# Led_Driver_180_LEDs.net
KiCad netlist of a schematic drawn in EAGLE
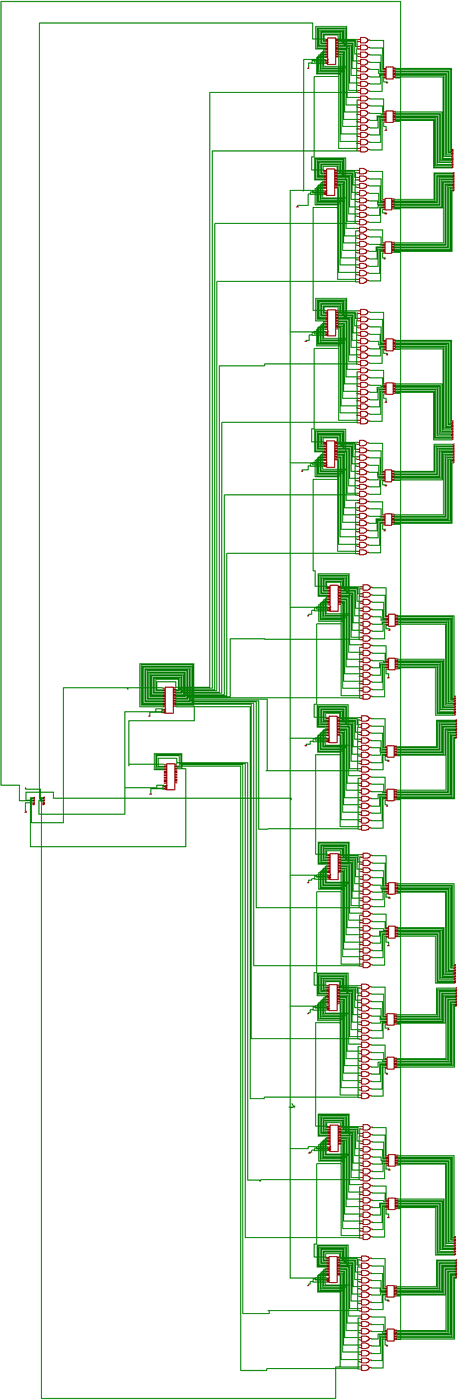
[diagram p0: schematic, sheet 1, overview]
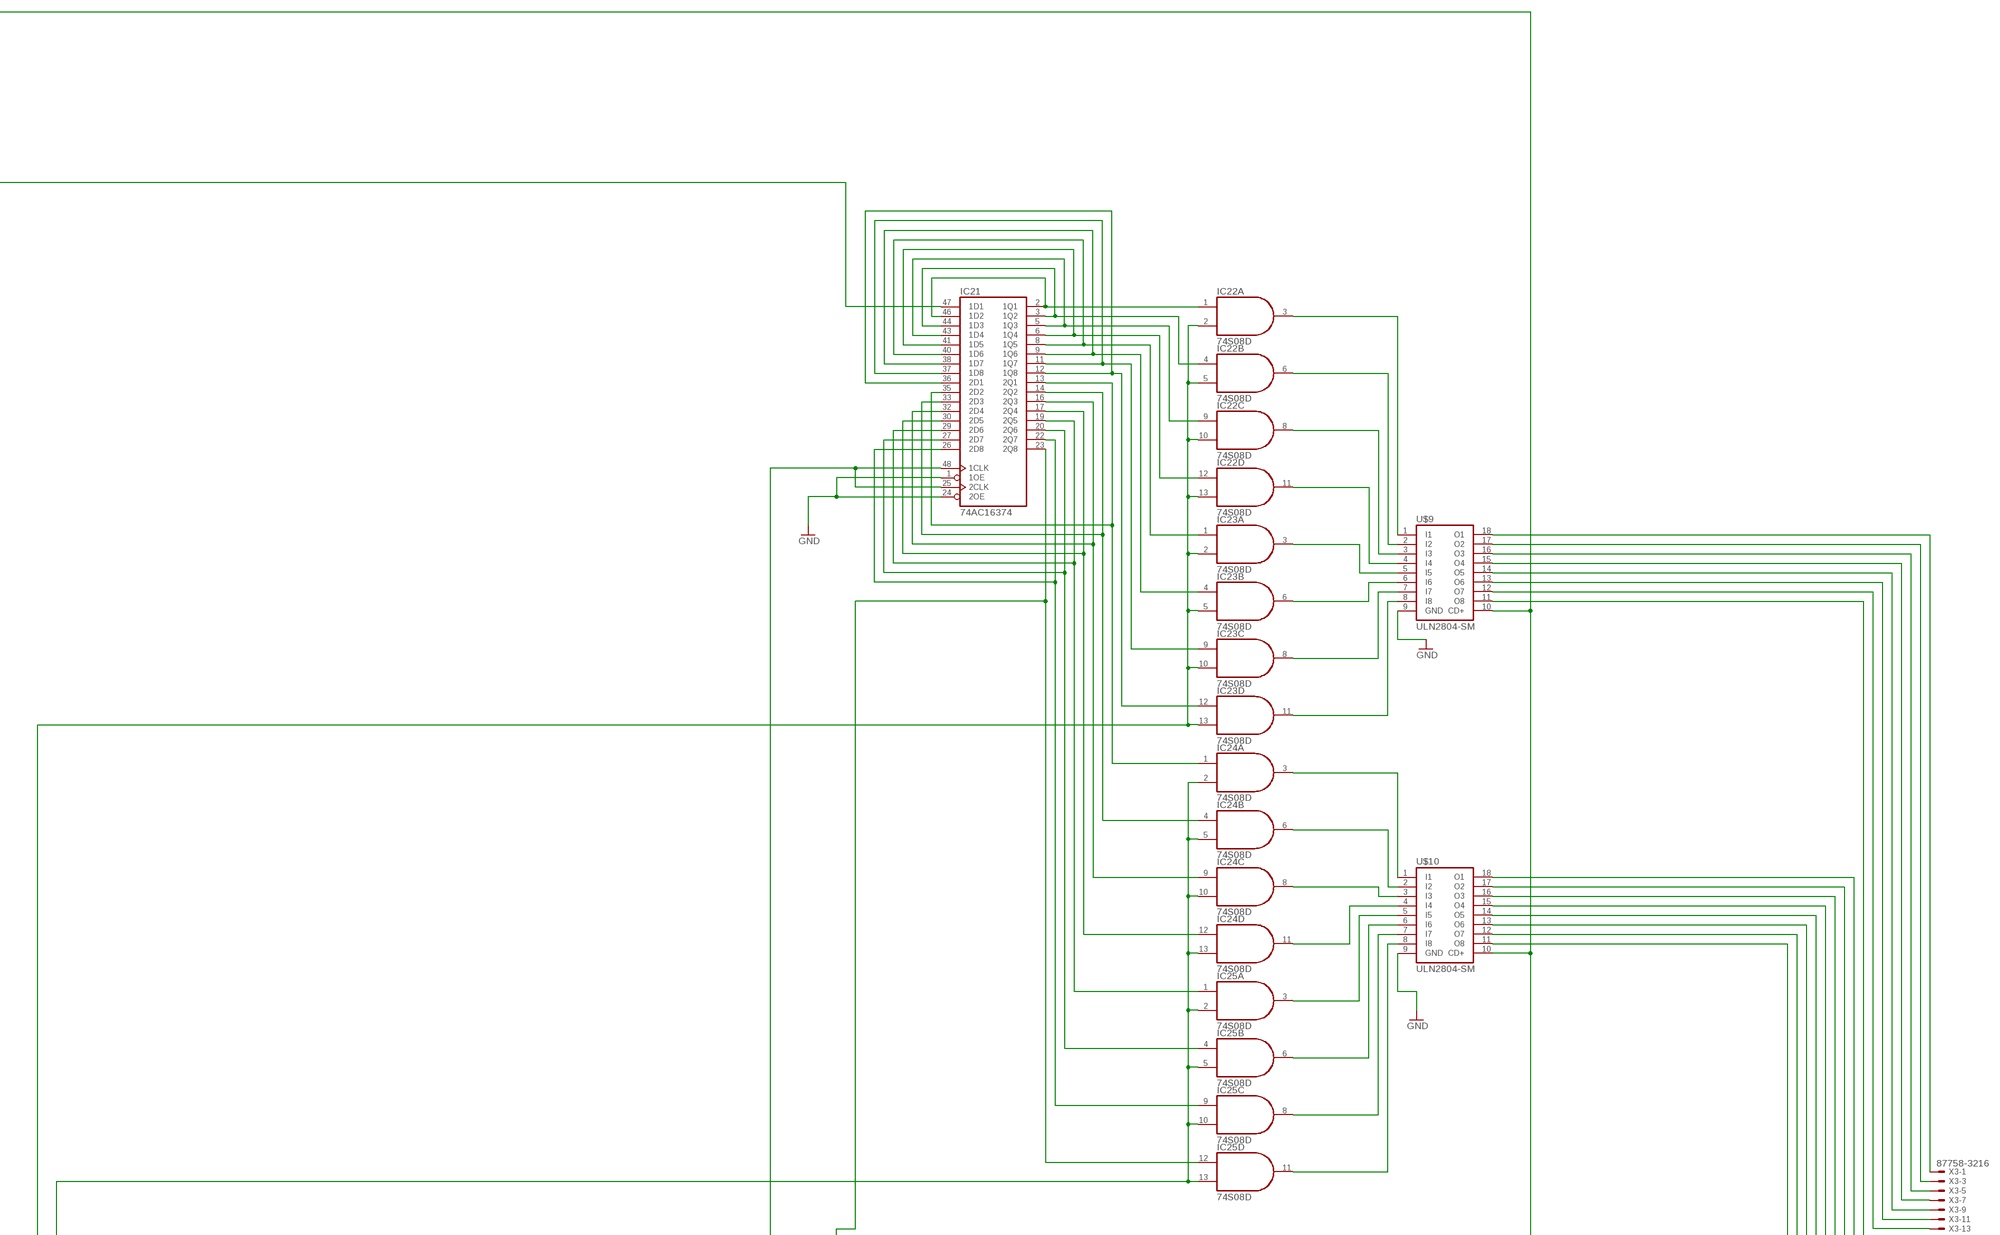
[diagram p1: schematic, sheet 1, part 1 of 9]
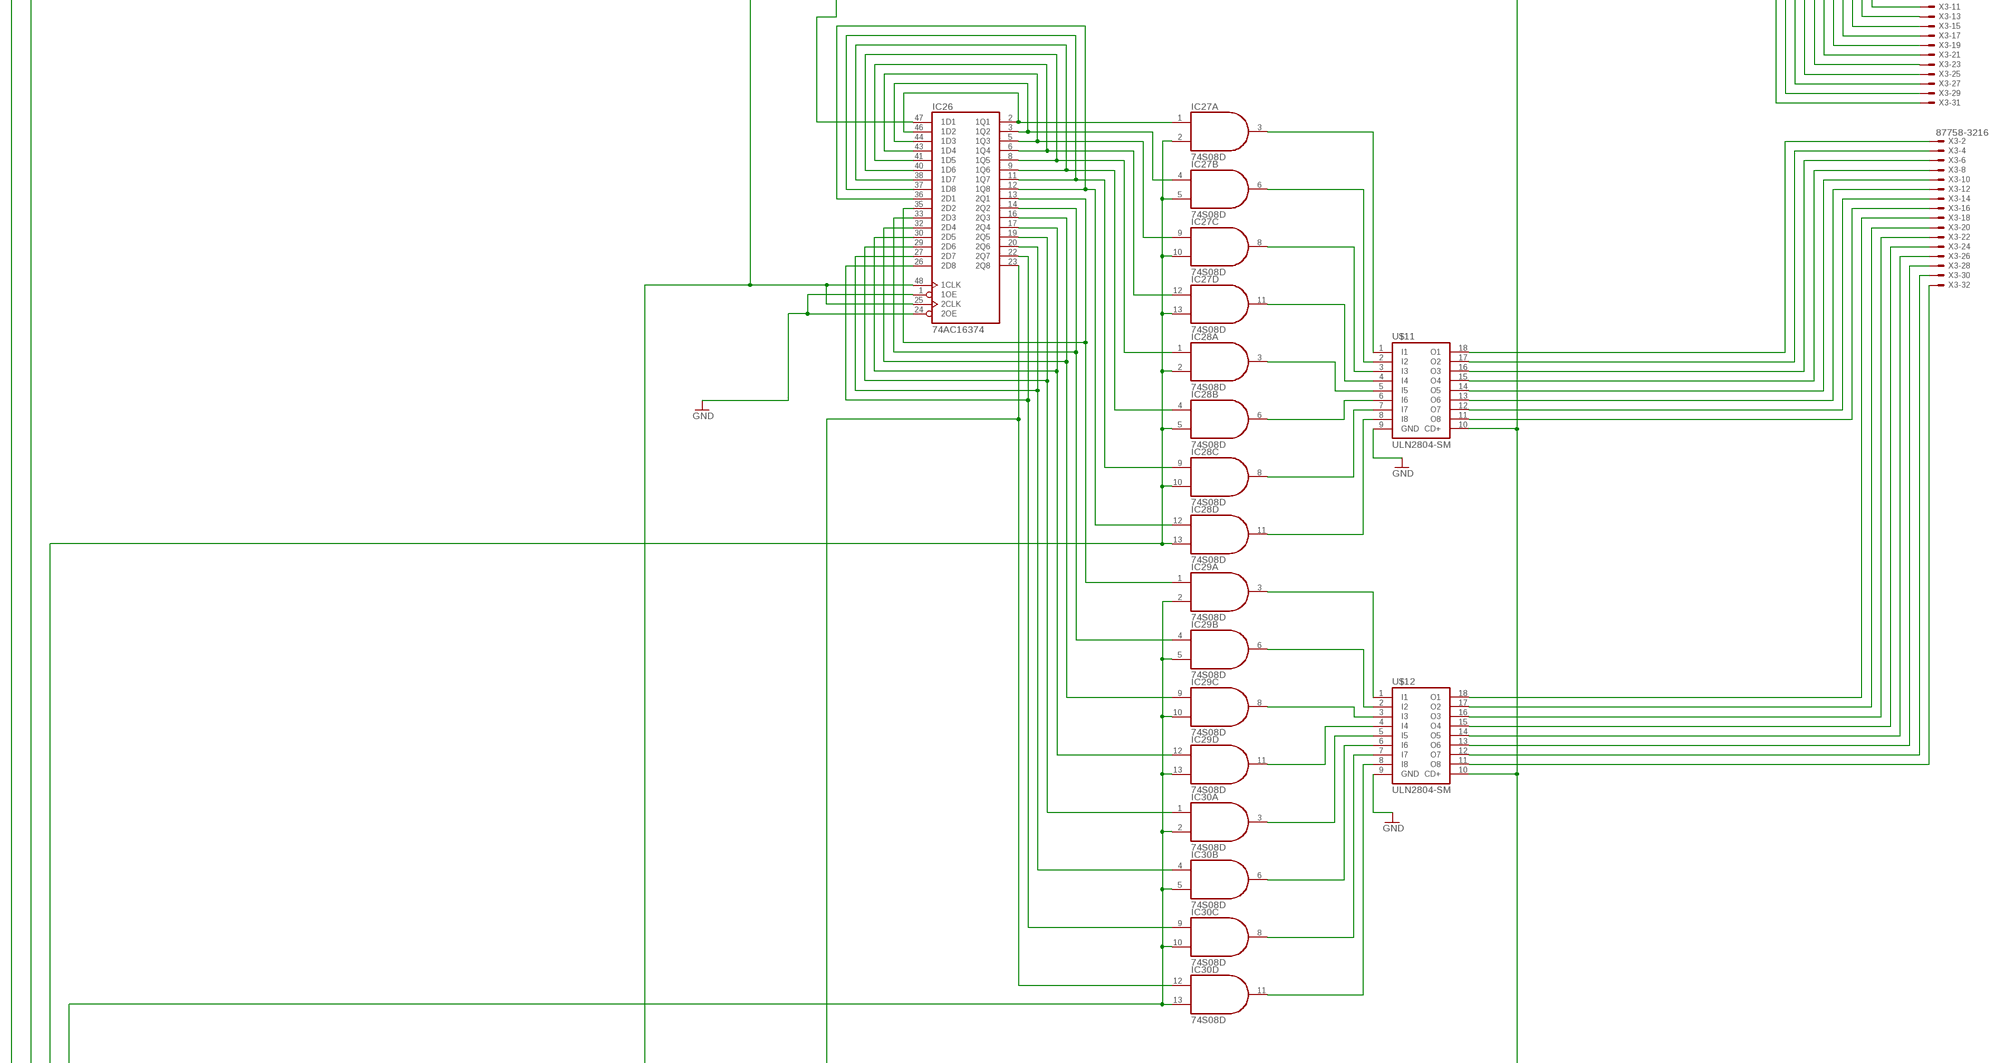
[diagram p2: schematic, sheet 1, part 2 of 9]
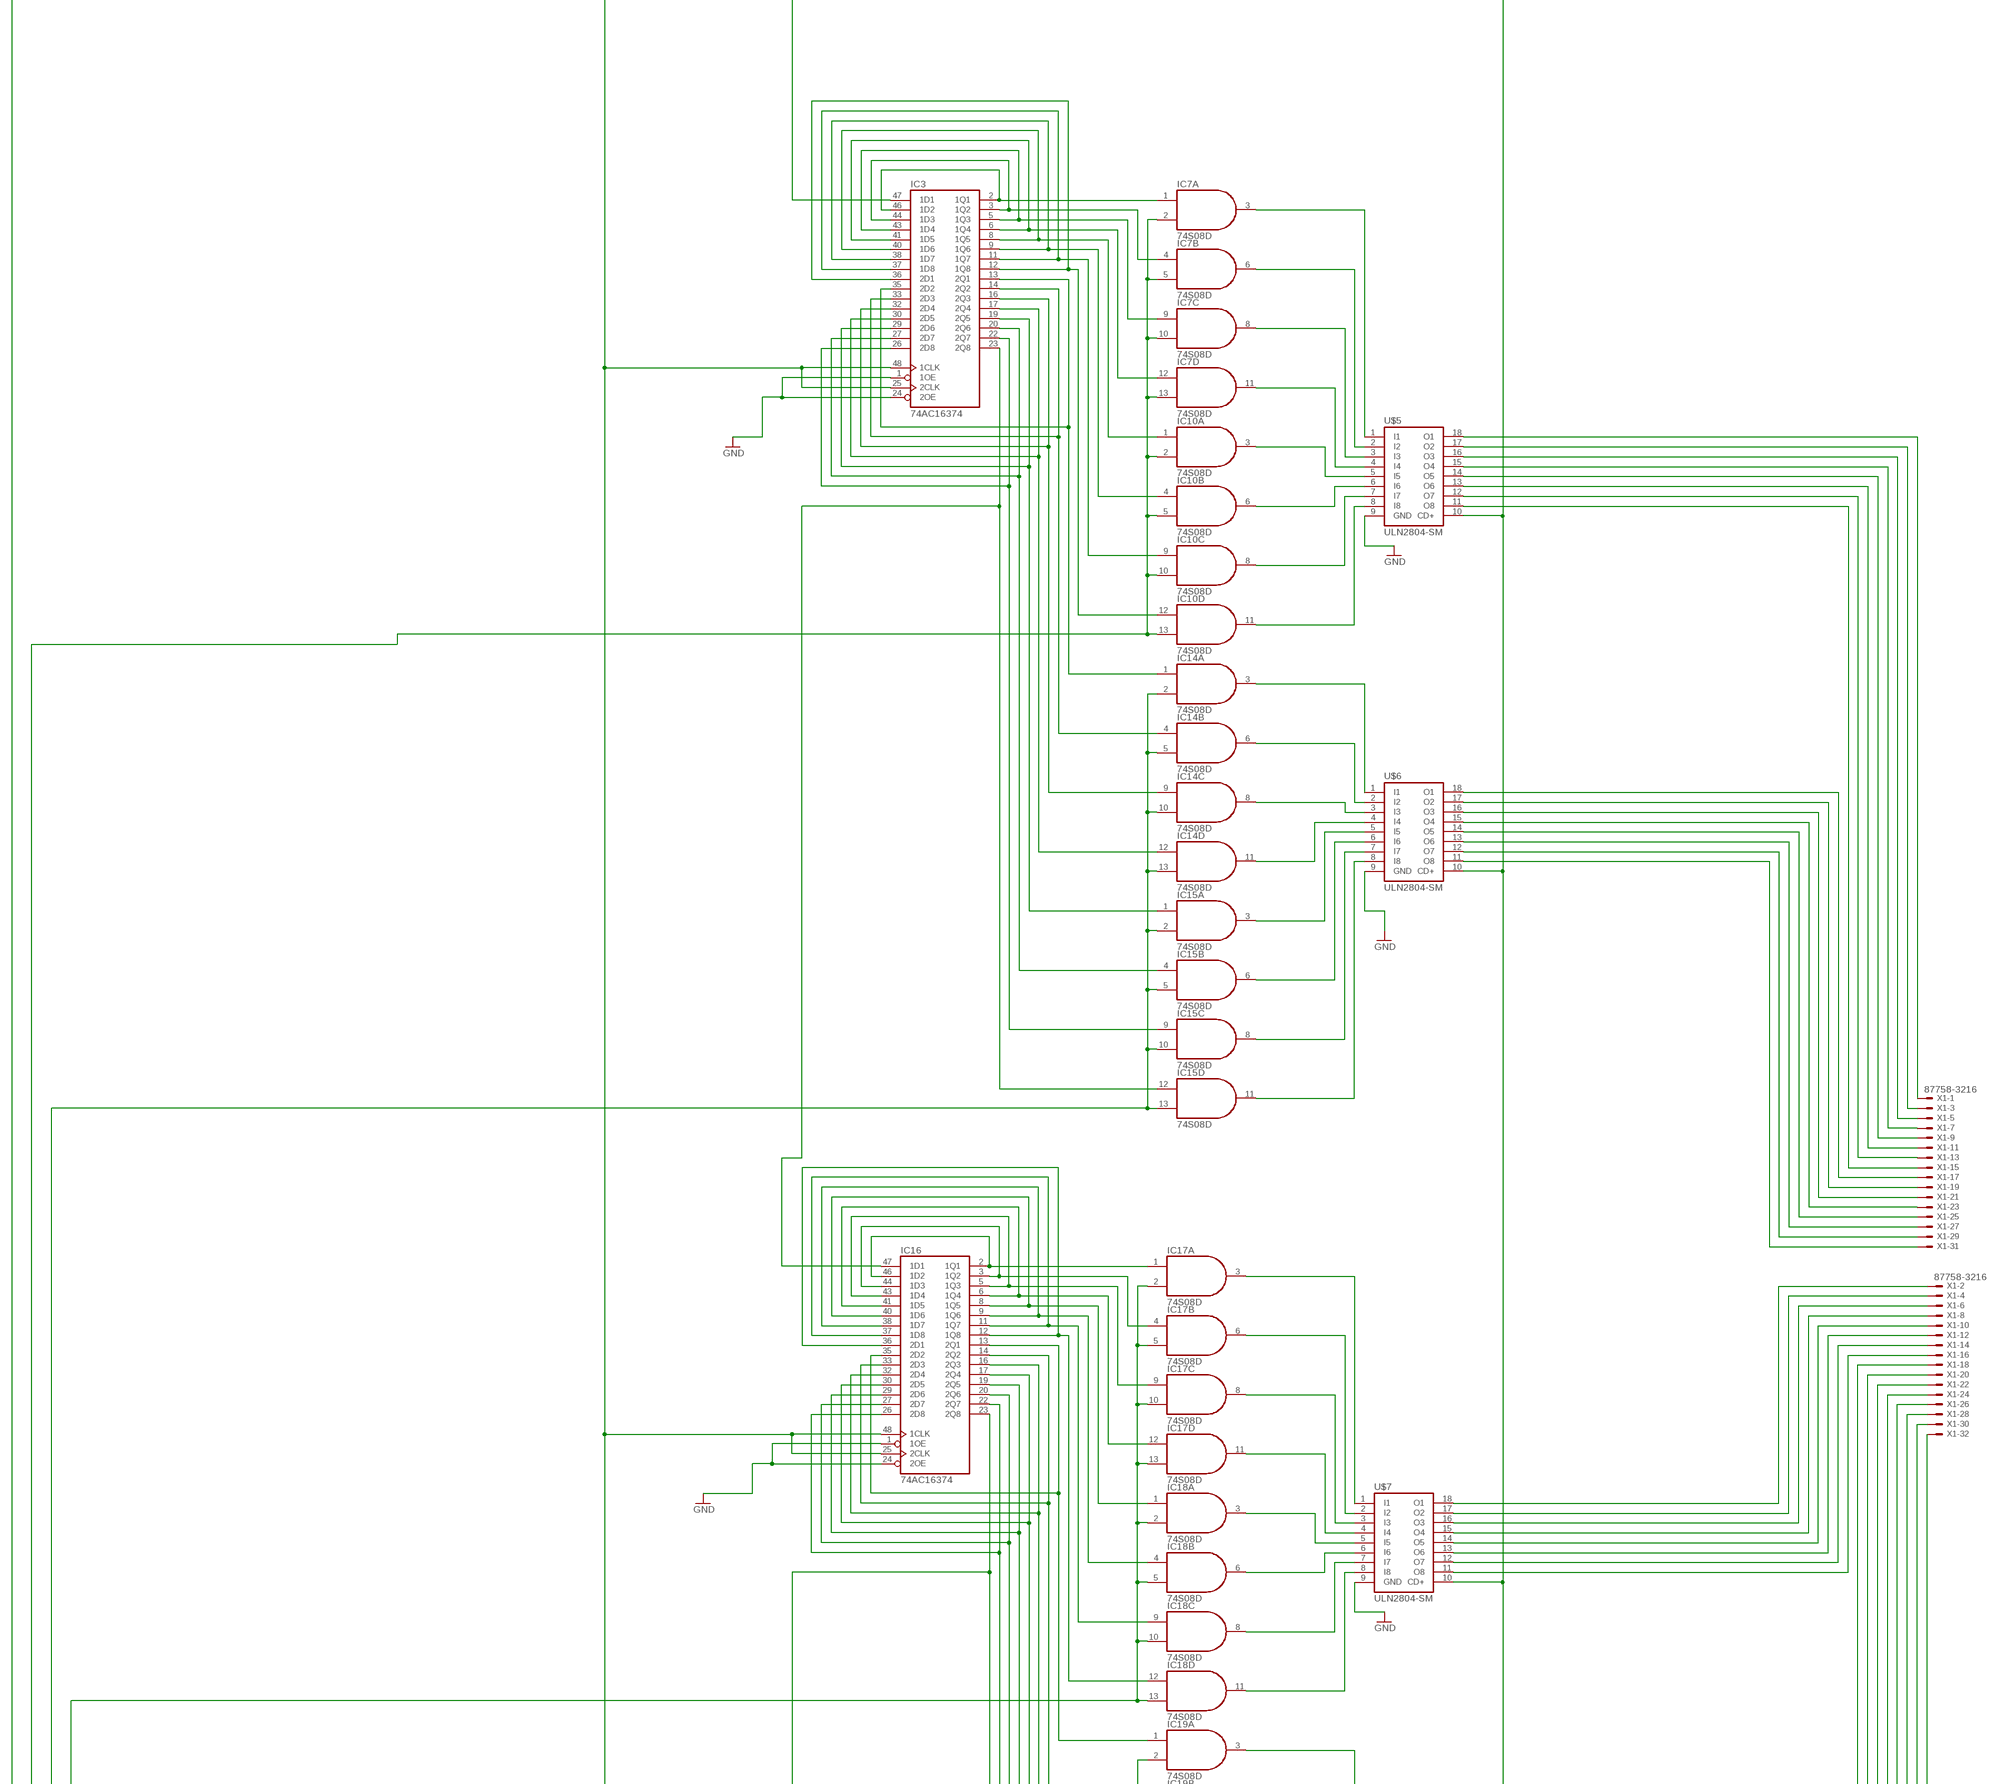
[diagram p3: schematic, sheet 1, part 3 of 9]
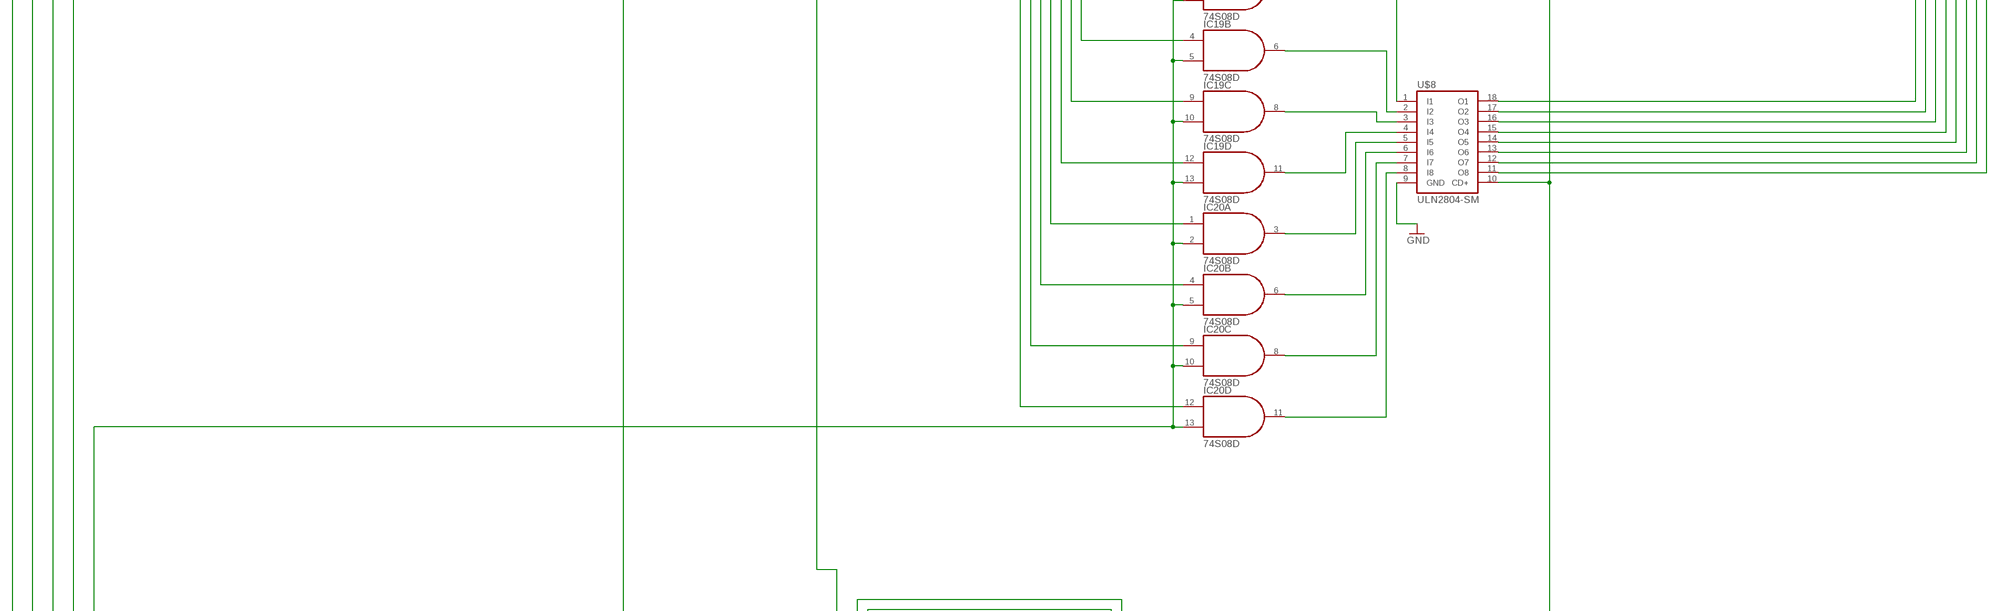
[diagram p4: schematic, sheet 1, part 4 of 9]
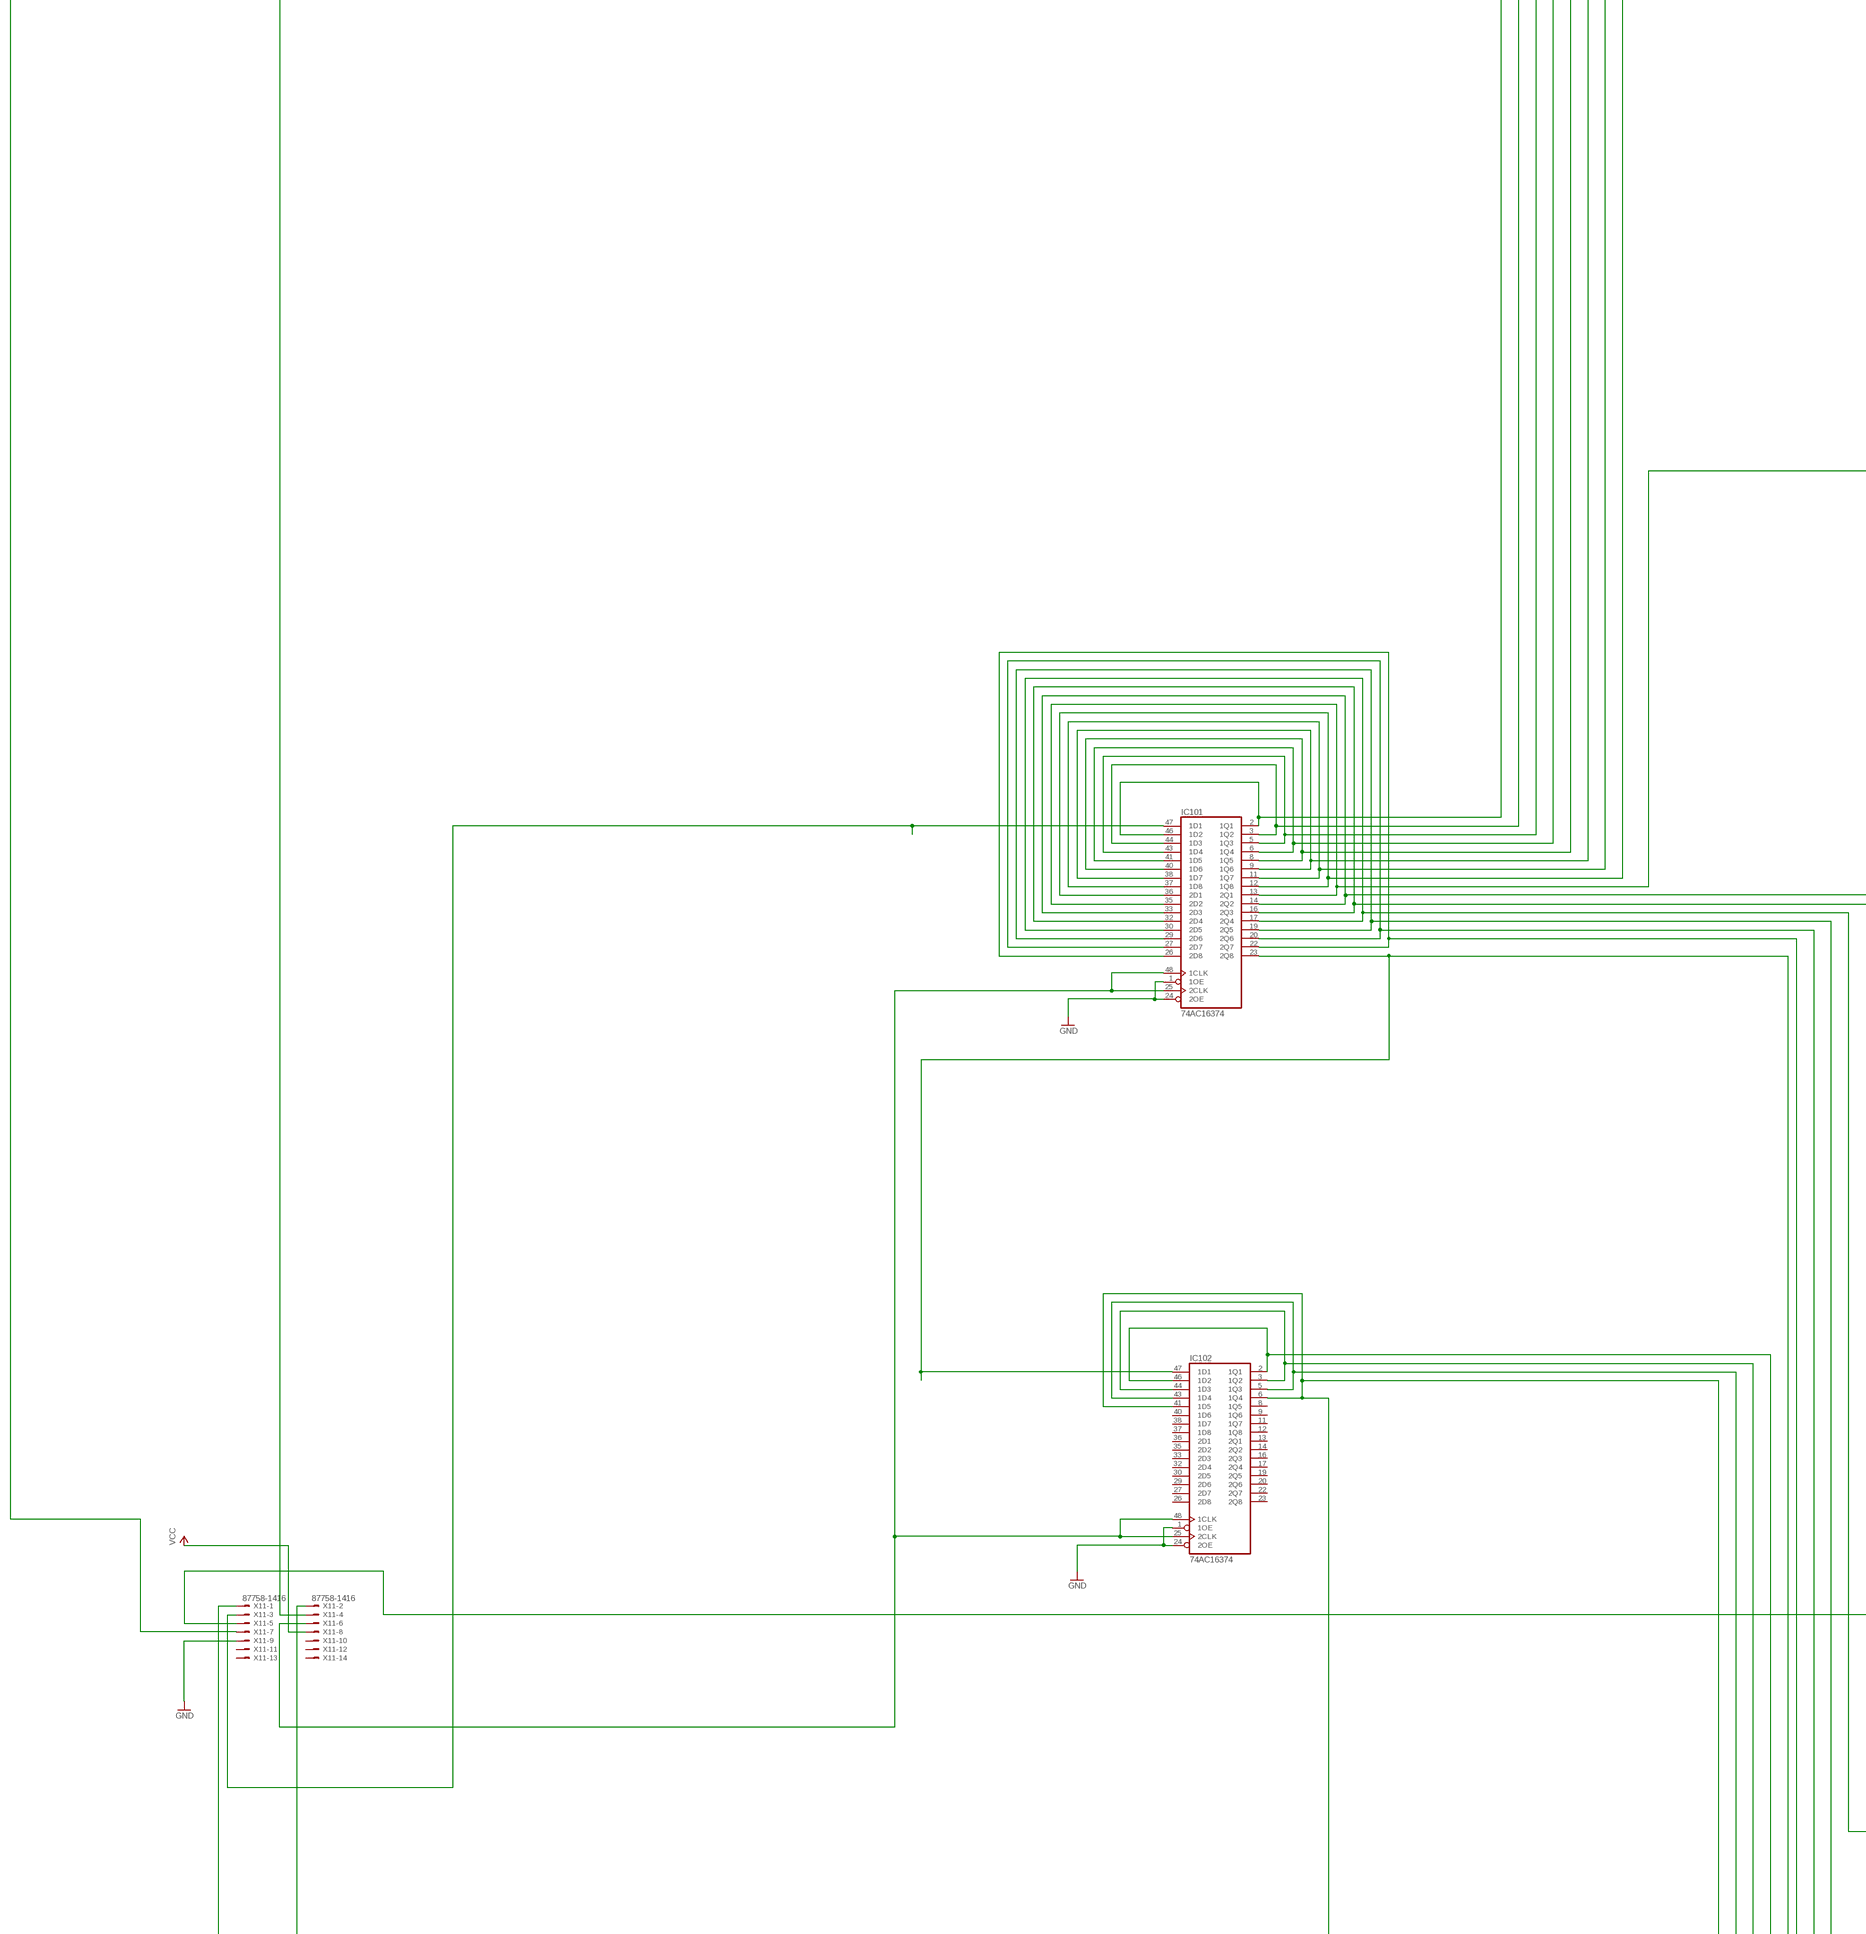
[diagram p5: schematic, sheet 1, part 5 of 9]
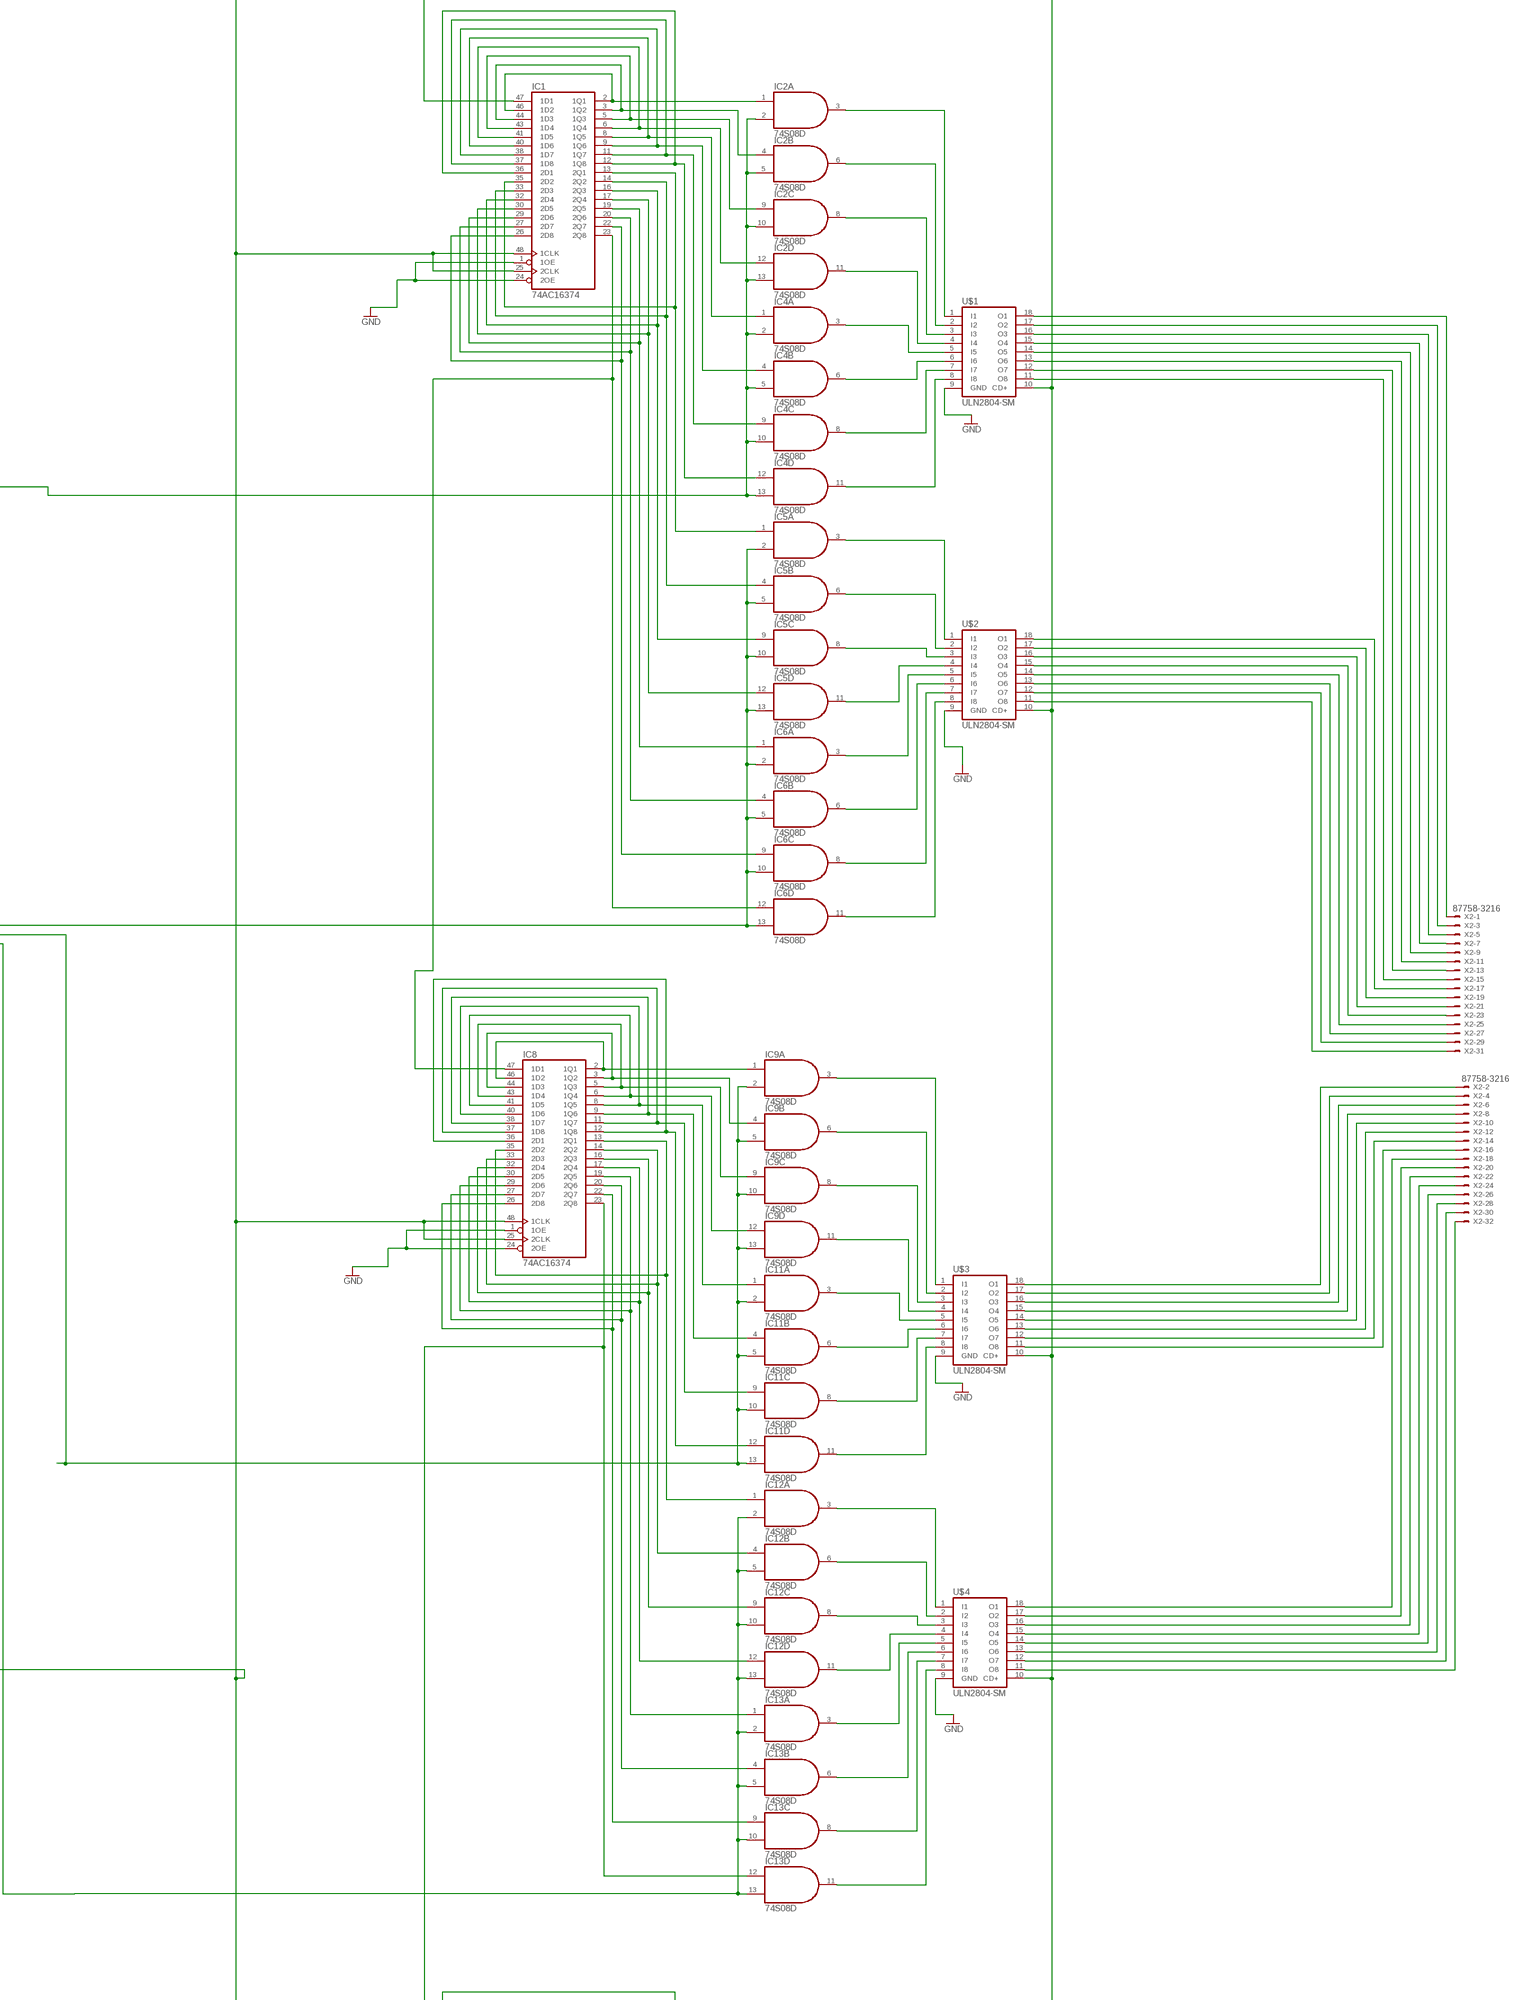
[diagram p6: schematic, sheet 1, part 6 of 9]
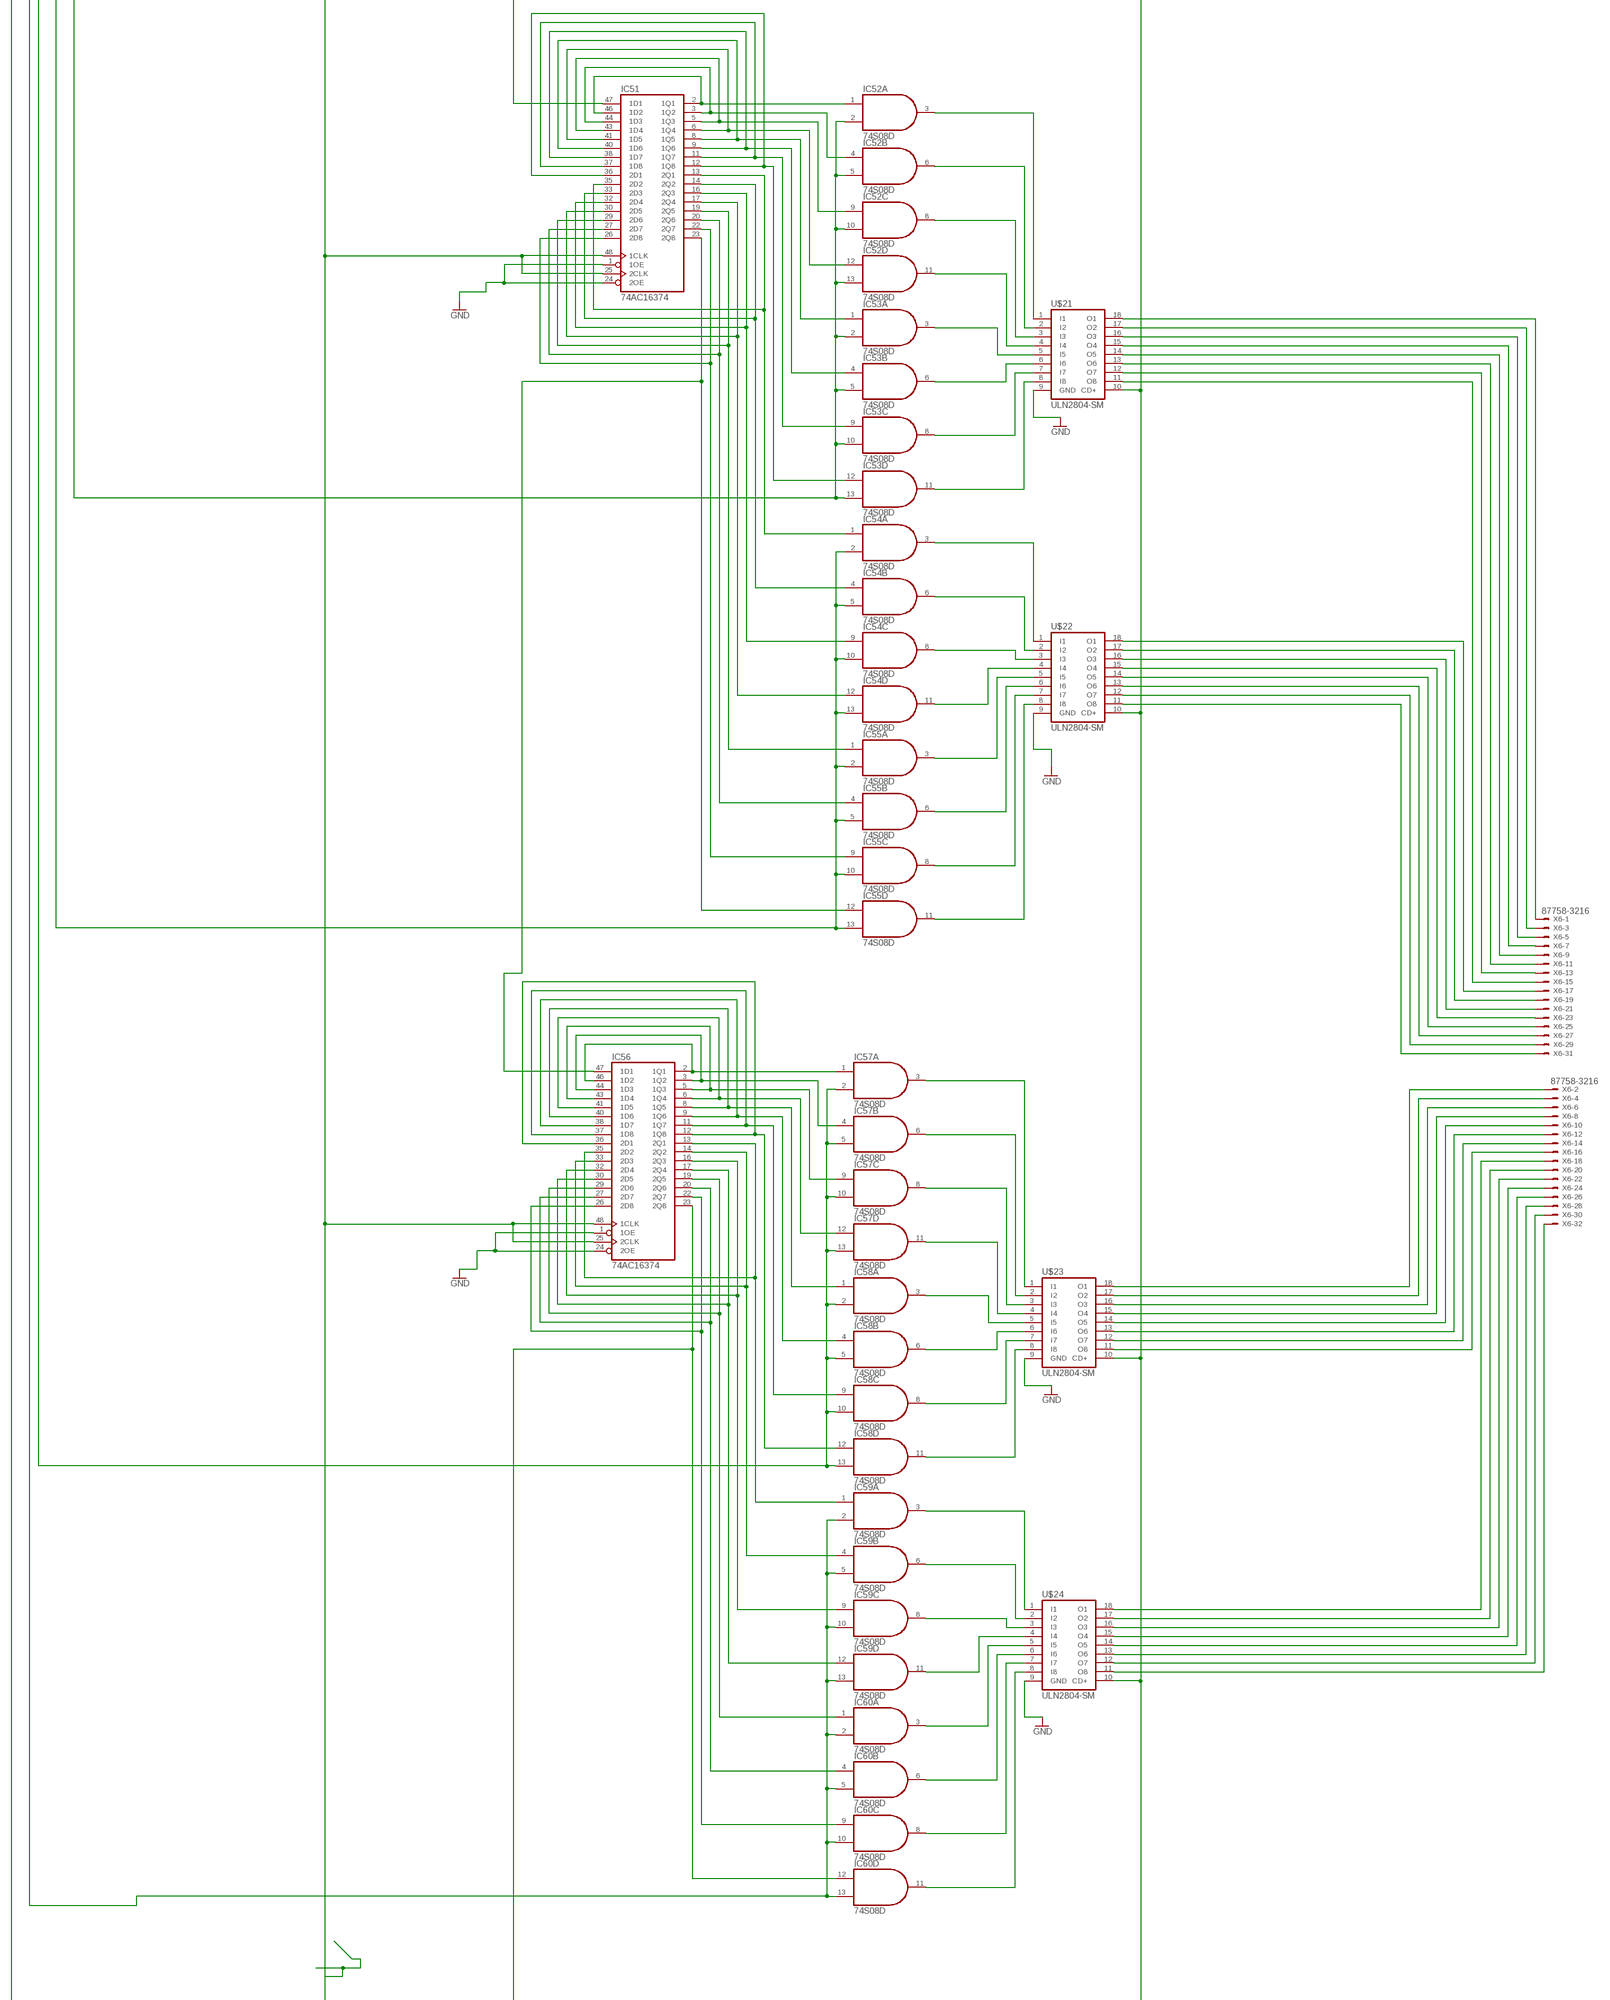
[diagram p7: schematic, sheet 1, part 7 of 9]
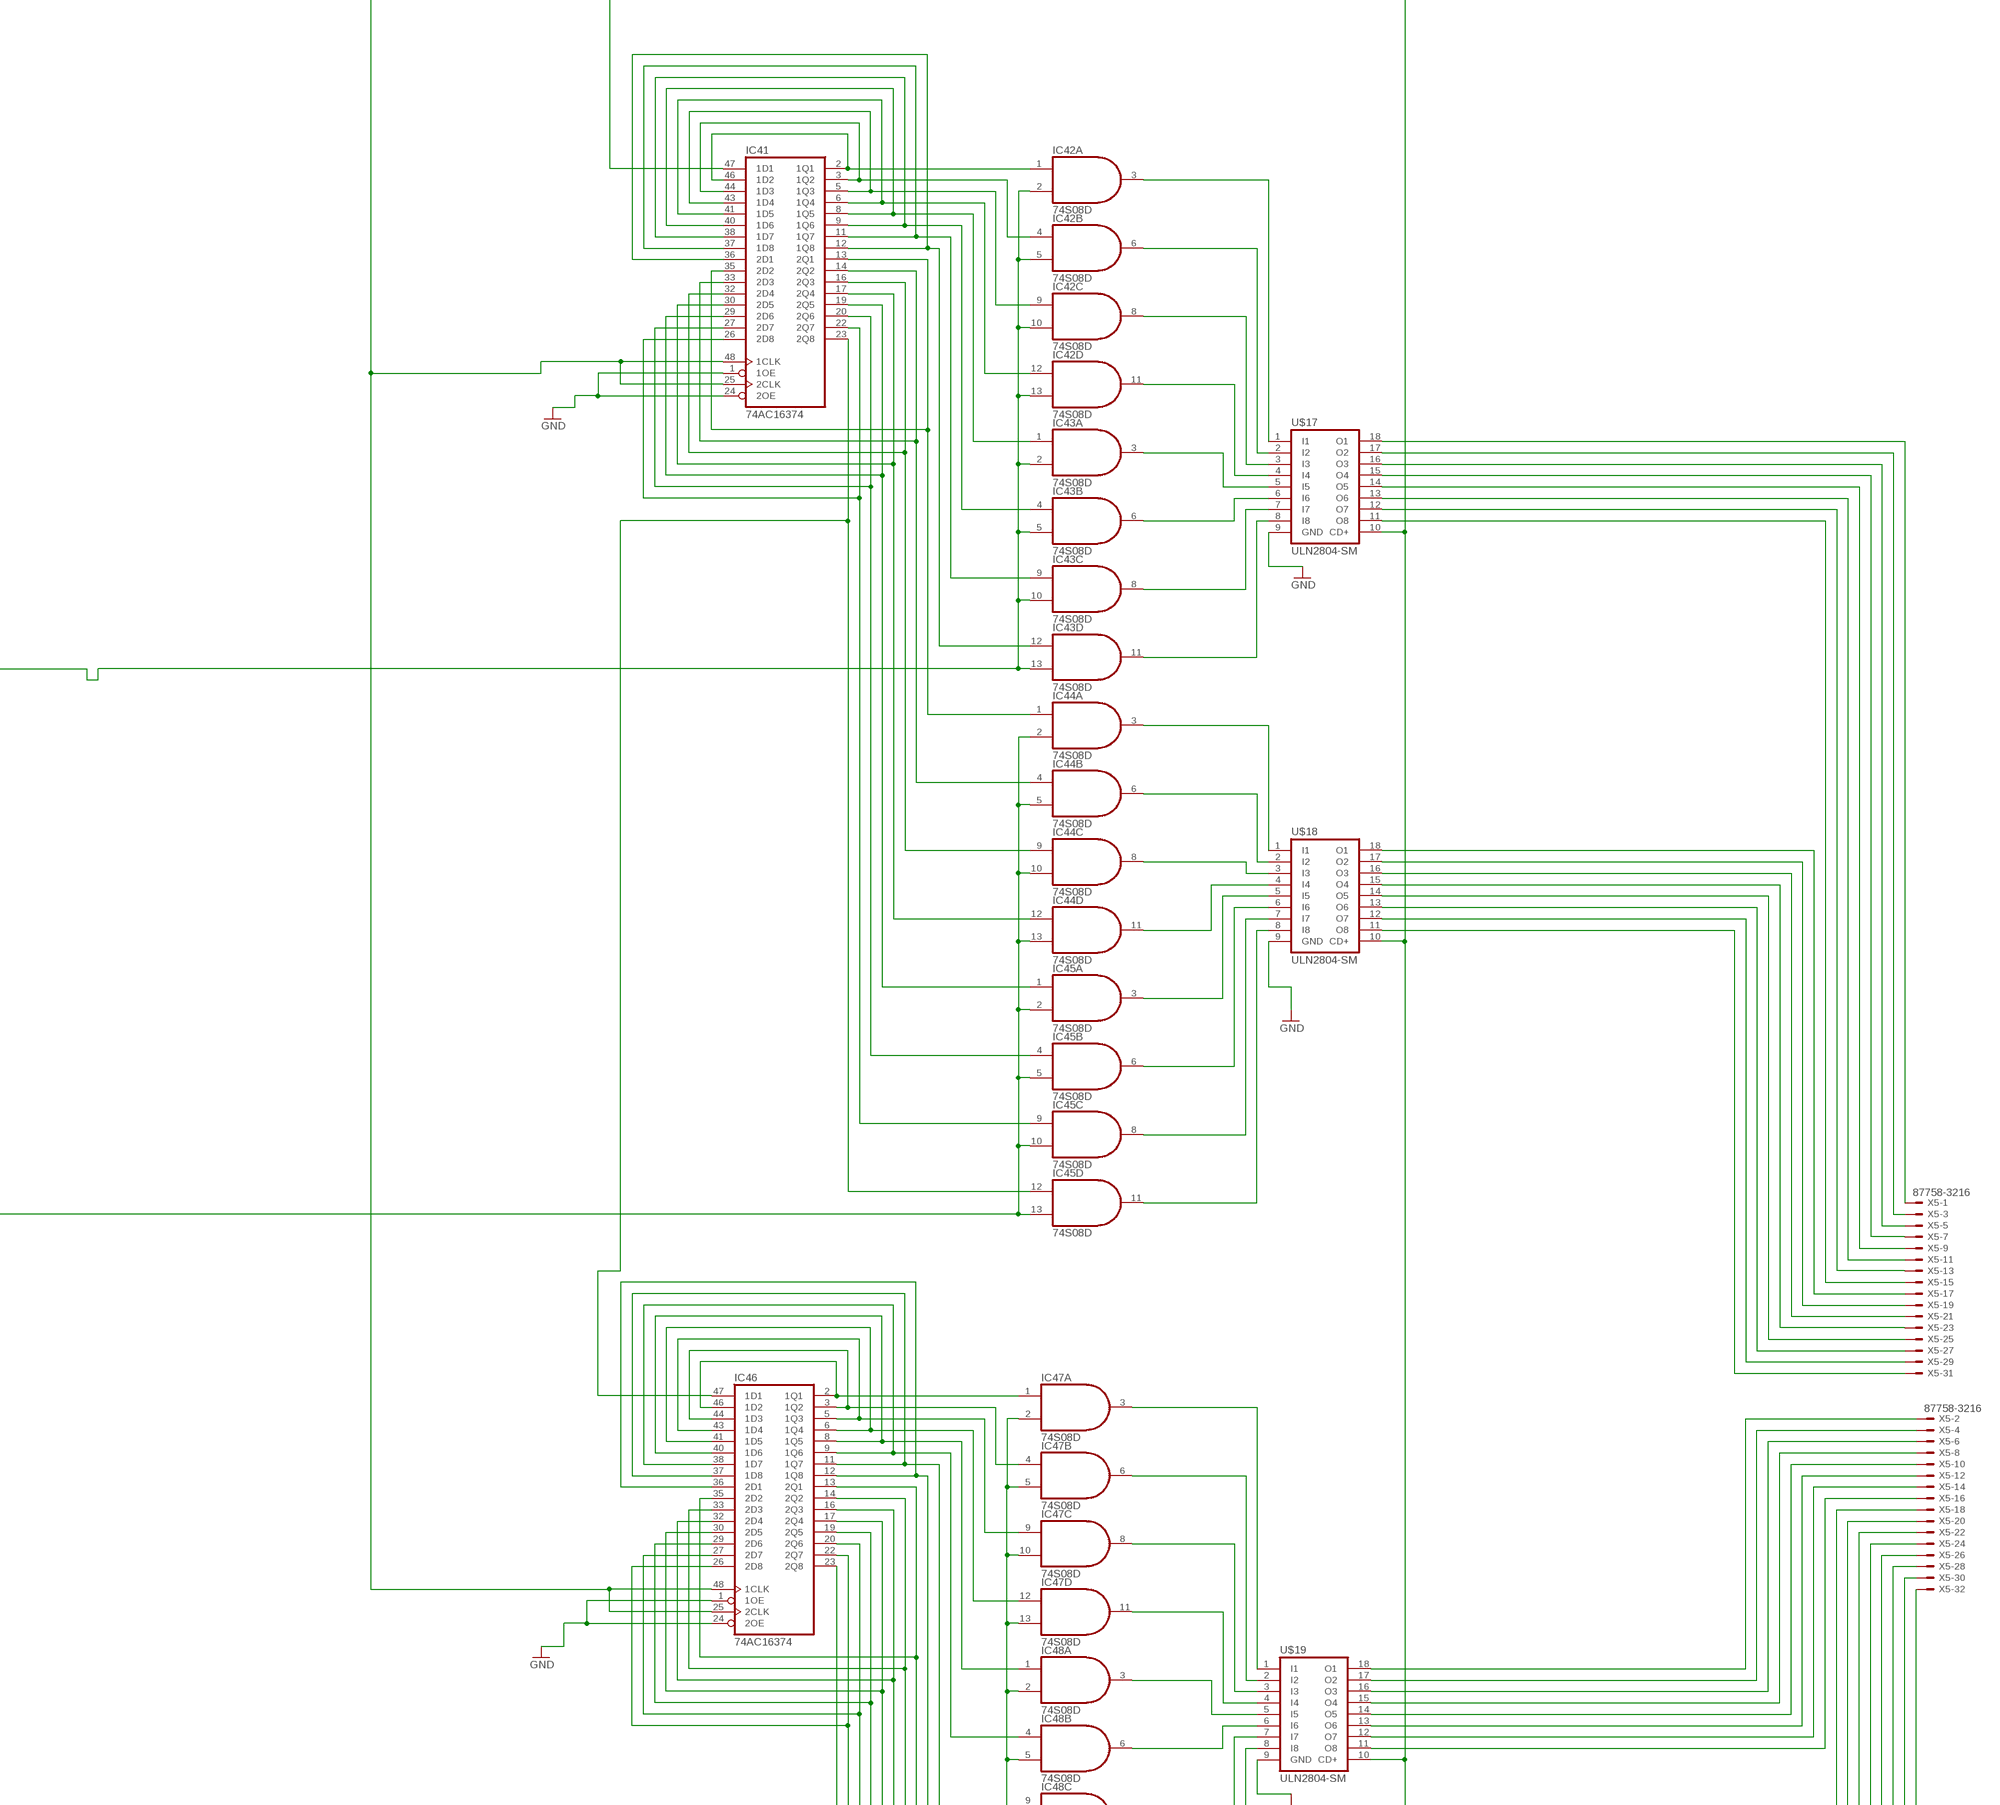
[diagram p8: schematic, sheet 1, part 8 of 9]
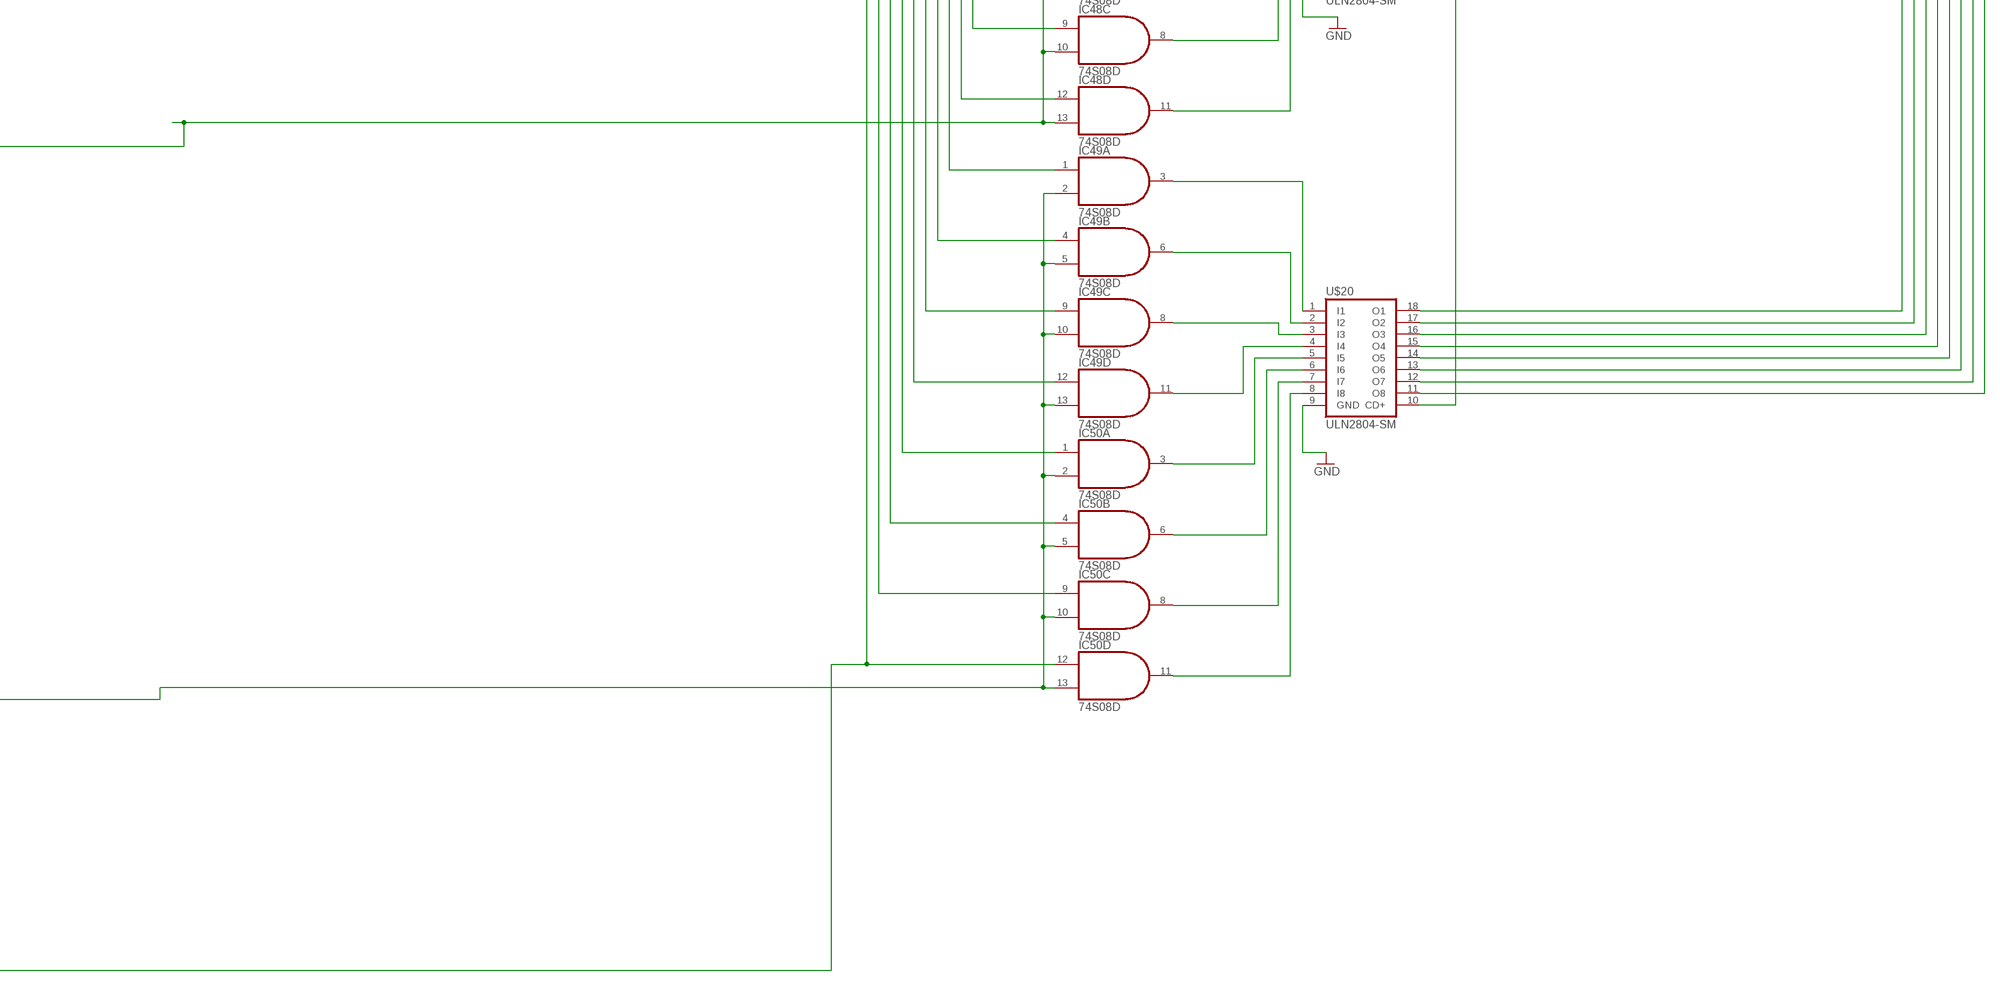
[diagram p9: schematic, sheet 1, part 9 of 9]

(export (version "E")
  (design (tool "Eeschema 10.0.6"))
  (components
    (comp (ref "IC1")
      (value "74AC16374")
      (footprint "eagle-import:SSOP48DL")
      (libsource (lib "eagle-import") (part "74AC16374"))
    )
    (comp (ref "IC2")
      (value "74S08D")
      (footprint "eagle-import:SO14")
      (libsource (lib "eagle-import") (part "7408DS"))
    )
    (comp (ref "IC3")
      (value "74AC16374")
      (footprint "eagle-import:SSOP48DL")
      (libsource (lib "eagle-import") (part "74AC16374"))
    )
    (comp (ref "IC4")
      (value "74S08D")
      (footprint "eagle-import:SO14")
      (libsource (lib "eagle-import") (part "7408DS"))
    )
    (comp (ref "IC5")
      (value "74S08D")
      (footprint "eagle-import:SO14")
      (libsource (lib "eagle-import") (part "7408DS"))
    )
    (comp (ref "IC6")
      (value "74S08D")
      (footprint "eagle-import:SO14")
      (libsource (lib "eagle-import") (part "7408DS"))
    )
    (comp (ref "IC7")
      (value "74S08D")
      (footprint "eagle-import:SO14")
      (libsource (lib "eagle-import") (part "7408DS"))
    )
    (comp (ref "IC8")
      (value "74AC16374")
      (footprint "eagle-import:SSOP48DL")
      (libsource (lib "eagle-import") (part "74AC16374"))
    )
    (comp (ref "IC9")
      (value "74S08D")
      (footprint "eagle-import:SO14")
      (libsource (lib "eagle-import") (part "7408DS"))
    )
    (comp (ref "IC10")
      (value "74S08D")
      (footprint "eagle-import:SO14")
      (libsource (lib "eagle-import") (part "7408DS"))
    )
    (comp (ref "IC11")
      (value "74S08D")
      (footprint "eagle-import:SO14")
      (libsource (lib "eagle-import") (part "7408DS"))
    )
    (comp (ref "IC12")
      (value "74S08D")
      (footprint "eagle-import:SO14")
      (libsource (lib "eagle-import") (part "7408DS"))
    )
    (comp (ref "IC13")
      (value "74S08D")
      (footprint "eagle-import:SO14")
      (libsource (lib "eagle-import") (part "7408DS"))
    )
    (comp (ref "IC14")
      (value "74S08D")
      (footprint "eagle-import:SO14")
      (libsource (lib "eagle-import") (part "7408DS"))
    )
    (comp (ref "IC15")
      (value "74S08D")
      (footprint "eagle-import:SO14")
      (libsource (lib "eagle-import") (part "7408DS"))
    )
    (comp (ref "IC16")
      (value "74AC16374")
      (footprint "eagle-import:SSOP48DL")
      (libsource (lib "eagle-import") (part "74AC16374"))
    )
    (comp (ref "IC17")
      (value "74S08D")
      (footprint "eagle-import:SO14")
      (libsource (lib "eagle-import") (part "7408DS"))
    )
    (comp (ref "IC18")
      (value "74S08D")
      (footprint "eagle-import:SO14")
      (libsource (lib "eagle-import") (part "7408DS"))
    )
    (comp (ref "IC19")
      (value "74S08D")
      (footprint "eagle-import:SO14")
      (libsource (lib "eagle-import") (part "7408DS"))
    )
    (comp (ref "IC20")
      (value "74S08D")
      (footprint "eagle-import:SO14")
      (libsource (lib "eagle-import") (part "7408DS"))
    )
    (comp (ref "IC21")
      (value "74AC16374")
      (footprint "eagle-import:SSOP48DL")
      (libsource (lib "eagle-import") (part "74AC16374"))
    )
    (comp (ref "IC22")
      (value "74S08D")
      (footprint "eagle-import:SO14")
      (libsource (lib "eagle-import") (part "7408DS"))
    )
    (comp (ref "IC23")
      (value "74S08D")
      (footprint "eagle-import:SO14")
      (libsource (lib "eagle-import") (part "7408DS"))
    )
    (comp (ref "IC24")
      (value "74S08D")
      (footprint "eagle-import:SO14")
      (libsource (lib "eagle-import") (part "7408DS"))
    )
    (comp (ref "IC25")
      (value "74S08D")
      (footprint "eagle-import:SO14")
      (libsource (lib "eagle-import") (part "7408DS"))
    )
    (comp (ref "IC26")
      (value "74AC16374")
      (footprint "eagle-import:SSOP48DL")
      (libsource (lib "eagle-import") (part "74AC16374"))
    )
    (comp (ref "IC27")
      (value "74S08D")
      (footprint "eagle-import:SO14")
      (libsource (lib "eagle-import") (part "7408DS"))
    )
    (comp (ref "IC28")
      (value "74S08D")
      (footprint "eagle-import:SO14")
      (libsource (lib "eagle-import") (part "7408DS"))
    )
    (comp (ref "IC29")
      (value "74S08D")
      (footprint "eagle-import:SO14")
      (libsource (lib "eagle-import") (part "7408DS"))
    )
    (comp (ref "IC30")
      (value "74S08D")
      (footprint "eagle-import:SO14")
      (libsource (lib "eagle-import") (part "7408DS"))
    )
    (comp (ref "IC41")
      (value "74AC16374")
      (footprint "eagle-import:SSOP48DL")
      (libsource (lib "eagle-import") (part "74AC16374"))
    )
    (comp (ref "IC42")
      (value "74S08D")
      (footprint "eagle-import:SO14")
      (libsource (lib "eagle-import") (part "7408DS"))
    )
    (comp (ref "IC43")
      (value "74S08D")
      (footprint "eagle-import:SO14")
      (libsource (lib "eagle-import") (part "7408DS"))
    )
    (comp (ref "IC44")
      (value "74S08D")
      (footprint "eagle-import:SO14")
      (libsource (lib "eagle-import") (part "7408DS"))
    )
    (comp (ref "IC45")
      (value "74S08D")
      (footprint "eagle-import:SO14")
      (libsource (lib "eagle-import") (part "7408DS"))
    )
    (comp (ref "IC46")
      (value "74AC16374")
      (footprint "eagle-import:SSOP48DL")
      (libsource (lib "eagle-import") (part "74AC16374"))
    )
    (comp (ref "IC47")
      (value "74S08D")
      (footprint "eagle-import:SO14")
      (libsource (lib "eagle-import") (part "7408DS"))
    )
    (comp (ref "IC48")
      (value "74S08D")
      (footprint "eagle-import:SO14")
      (libsource (lib "eagle-import") (part "7408DS"))
    )
    (comp (ref "IC49")
      (value "74S08D")
      (footprint "eagle-import:SO14")
      (libsource (lib "eagle-import") (part "7408DS"))
    )
    (comp (ref "IC50")
      (value "74S08D")
      (footprint "eagle-import:SO14")
      (libsource (lib "eagle-import") (part "7408DS"))
    )
    (comp (ref "IC51")
      (value "74AC16374")
      (footprint "eagle-import:SSOP48DL")
      (libsource (lib "eagle-import") (part "74AC16374"))
    )
    (comp (ref "IC52")
      (value "74S08D")
      (footprint "eagle-import:SO14")
      (libsource (lib "eagle-import") (part "7408DS"))
    )
    (comp (ref "IC53")
      (value "74S08D")
      (footprint "eagle-import:SO14")
      (libsource (lib "eagle-import") (part "7408DS"))
    )
    (comp (ref "IC54")
      (value "74S08D")
      (footprint "eagle-import:SO14")
      (libsource (lib "eagle-import") (part "7408DS"))
    )
    (comp (ref "IC55")
      (value "74S08D")
      (footprint "eagle-import:SO14")
      (libsource (lib "eagle-import") (part "7408DS"))
    )
    (comp (ref "IC56")
      (value "74AC16374")
      (footprint "eagle-import:SSOP48DL")
      (libsource (lib "eagle-import") (part "74AC16374"))
    )
    (comp (ref "IC57")
      (value "74S08D")
      (footprint "eagle-import:SO14")
      (libsource (lib "eagle-import") (part "7408DS"))
    )
    (comp (ref "IC58")
      (value "74S08D")
      (footprint "eagle-import:SO14")
      (libsource (lib "eagle-import") (part "7408DS"))
    )
    (comp (ref "IC59")
      (value "74S08D")
      (footprint "eagle-import:SO14")
      (libsource (lib "eagle-import") (part "7408DS"))
    )
    (comp (ref "IC60")
      (value "74S08D")
      (footprint "eagle-import:SO14")
      (libsource (lib "eagle-import") (part "7408DS"))
    )
    (comp (ref "IC101")
      (value "74AC16374")
      (footprint "eagle-import:SSOP48DL")
      (libsource (lib "eagle-import") (part "74AC16374"))
    )
    (comp (ref "IC102")
      (value "74AC16374")
      (footprint "eagle-import:SSOP48DL")
      (libsource (lib "eagle-import") (part "74AC16374"))
    )
    (comp (ref "U$1")
      (value "ULN2804-SM")
      (footprint "eagle-import:SOP-18")
      (libsource (lib "eagle-import") (part "ULN2804-SM"))
    )
    (comp (ref "U$2")
      (value "ULN2804-SM")
      (footprint "eagle-import:SOP-18")
      (libsource (lib "eagle-import") (part "ULN2804-SM"))
    )
    (comp (ref "U$3")
      (value "ULN2804-SM")
      (footprint "eagle-import:SOP-18")
      (libsource (lib "eagle-import") (part "ULN2804-SM"))
    )
    (comp (ref "U$4")
      (value "ULN2804-SM")
      (footprint "eagle-import:SOP-18")
      (libsource (lib "eagle-import") (part "ULN2804-SM"))
    )
    (comp (ref "U$5")
      (value "ULN2804-SM")
      (footprint "eagle-import:SOP-18")
      (libsource (lib "eagle-import") (part "ULN2804-SM"))
    )
    (comp (ref "U$6")
      (value "ULN2804-SM")
      (footprint "eagle-import:SOP-18")
      (libsource (lib "eagle-import") (part "ULN2804-SM"))
    )
    (comp (ref "U$7")
      (value "ULN2804-SM")
      (footprint "eagle-import:SOP-18")
      (libsource (lib "eagle-import") (part "ULN2804-SM"))
    )
    (comp (ref "U$8")
      (value "ULN2804-SM")
      (footprint "eagle-import:SOP-18")
      (libsource (lib "eagle-import") (part "ULN2804-SM"))
    )
    (comp (ref "U$9")
      (value "ULN2804-SM")
      (footprint "eagle-import:SOP-18")
      (libsource (lib "eagle-import") (part "ULN2804-SM"))
    )
    (comp (ref "U$10")
      (value "ULN2804-SM")
      (footprint "eagle-import:SOP-18")
      (libsource (lib "eagle-import") (part "ULN2804-SM"))
    )
    (comp (ref "U$11")
      (value "ULN2804-SM")
      (footprint "eagle-import:SOP-18")
      (libsource (lib "eagle-import") (part "ULN2804-SM"))
    )
    (comp (ref "U$12")
      (value "ULN2804-SM")
      (footprint "eagle-import:SOP-18")
      (libsource (lib "eagle-import") (part "ULN2804-SM"))
    )
    (comp (ref "U$17")
      (value "ULN2804-SM")
      (footprint "eagle-import:SOP-18")
      (libsource (lib "eagle-import") (part "ULN2804-SM"))
    )
    (comp (ref "U$18")
      (value "ULN2804-SM")
      (footprint "eagle-import:SOP-18")
      (libsource (lib "eagle-import") (part "ULN2804-SM"))
    )
    (comp (ref "U$19")
      (value "ULN2804-SM")
      (footprint "eagle-import:SOP-18")
      (libsource (lib "eagle-import") (part "ULN2804-SM"))
    )
    (comp (ref "U$20")
      (value "ULN2804-SM")
      (footprint "eagle-import:SOP-18")
      (libsource (lib "eagle-import") (part "ULN2804-SM"))
    )
    (comp (ref "U$21")
      (value "ULN2804-SM")
      (footprint "eagle-import:SOP-18")
      (libsource (lib "eagle-import") (part "ULN2804-SM"))
    )
    (comp (ref "U$22")
      (value "ULN2804-SM")
      (footprint "eagle-import:SOP-18")
      (libsource (lib "eagle-import") (part "ULN2804-SM"))
    )
    (comp (ref "U$23")
      (value "ULN2804-SM")
      (footprint "eagle-import:SOP-18")
      (libsource (lib "eagle-import") (part "ULN2804-SM"))
    )
    (comp (ref "U$24")
      (value "ULN2804-SM")
      (footprint "eagle-import:SOP-18")
      (libsource (lib "eagle-import") (part "ULN2804-SM"))
    )
    (comp (ref "X1")
      (value "87758-3216")
      (footprint "eagle-import:87758-3216")
      (libsource (lib "eagle-import") (part "87758-3216"))
    )
    (comp (ref "X2")
      (value "87758-3216")
      (footprint "eagle-import:87758-3216")
      (libsource (lib "eagle-import") (part "87758-3216"))
    )
    (comp (ref "X3")
      (value "87758-3216")
      (footprint "eagle-import:87758-3216")
      (libsource (lib "eagle-import") (part "87758-3216"))
    )
    (comp (ref "X5")
      (value "87758-3216")
      (footprint "eagle-import:87758-3216")
      (libsource (lib "eagle-import") (part "87758-3216"))
    )
    (comp (ref "X6")
      (value "87758-3216")
      (footprint "eagle-import:87758-3216")
      (libsource (lib "eagle-import") (part "87758-3216"))
    )
    (comp (ref "X11")
      (value "87758-1416")
      (footprint "eagle-import:87758-1416")
      (fields (field (name "MF") "MOLEX"))
      (libsource (lib "eagle-import") (part "87758-1416"))
    )
  )
  (nets
    (net (code "1") (name "GND") (class "Default")
      (node (ref "IC1") (pin "1") (pinfunction "1OE_1") (pintype "input"))
      (node (ref "IC1") (pin "24") (pinfunction "2OE_24") (pintype "input"))
      (node (ref "IC101") (pin "1") (pinfunction "1OE_1") (pintype "input"))
      (node (ref "IC101") (pin "24") (pinfunction "2OE_24") (pintype "input"))
      (node (ref "IC102") (pin "1") (pinfunction "1OE_1") (pintype "input"))
      (node (ref "IC102") (pin "24") (pinfunction "2OE_24") (pintype "input"))
      (node (ref "IC16") (pin "1") (pinfunction "1OE_1") (pintype "input"))
      (node (ref "IC16") (pin "24") (pinfunction "2OE_24") (pintype "input"))
      (node (ref "IC21") (pin "1") (pinfunction "1OE_1") (pintype "input"))
      (node (ref "IC21") (pin "24") (pinfunction "2OE_24") (pintype "input"))
      (node (ref "IC26") (pin "1") (pinfunction "1OE_1") (pintype "input"))
      (node (ref "IC26") (pin "24") (pinfunction "2OE_24") (pintype "input"))
      (node (ref "IC3") (pin "1") (pinfunction "1OE_1") (pintype "input"))
      (node (ref "IC3") (pin "24") (pinfunction "2OE_24") (pintype "input"))
      (node (ref "IC41") (pin "1") (pinfunction "1OE_1") (pintype "input"))
      (node (ref "IC41") (pin "24") (pinfunction "2OE_24") (pintype "input"))
      (node (ref "IC46") (pin "1") (pinfunction "1OE_1") (pintype "input"))
      (node (ref "IC46") (pin "24") (pinfunction "2OE_24") (pintype "input"))
      (node (ref "IC51") (pin "1") (pinfunction "1OE_1") (pintype "input"))
      (node (ref "IC51") (pin "24") (pinfunction "2OE_24") (pintype "input"))
      (node (ref "IC56") (pin "1") (pinfunction "1OE_1") (pintype "input"))
      (node (ref "IC56") (pin "24") (pinfunction "2OE_24") (pintype "input"))
      (node (ref "IC8") (pin "1") (pinfunction "1OE_1") (pintype "input"))
      (node (ref "IC8") (pin "24") (pinfunction "2OE_24") (pintype "input"))
      (node (ref "U$1") (pin "9") (pinfunction "GND_9") (pintype "power_in"))
      (node (ref "U$10") (pin "9") (pinfunction "GND_9") (pintype "power_in"))
      (node (ref "U$11") (pin "9") (pinfunction "GND_9") (pintype "power_in"))
      (node (ref "U$12") (pin "9") (pinfunction "GND_9") (pintype "power_in"))
      (node (ref "U$17") (pin "9") (pinfunction "GND_9") (pintype "power_in"))
      (node (ref "U$18") (pin "9") (pinfunction "GND_9") (pintype "power_in"))
      (node (ref "U$19") (pin "9") (pinfunction "GND_9") (pintype "power_in"))
      (node (ref "U$2") (pin "9") (pinfunction "GND_9") (pintype "power_in"))
      (node (ref "U$20") (pin "9") (pinfunction "GND_9") (pintype "power_in"))
      (node (ref "U$21") (pin "9") (pinfunction "GND_9") (pintype "power_in"))
      (node (ref "U$22") (pin "9") (pinfunction "GND_9") (pintype "power_in"))
      (node (ref "U$23") (pin "9") (pinfunction "GND_9") (pintype "power_in"))
      (node (ref "U$24") (pin "9") (pinfunction "GND_9") (pintype "power_in"))
      (node (ref "U$3") (pin "9") (pinfunction "GND_9") (pintype "power_in"))
      (node (ref "U$4") (pin "9") (pinfunction "GND_9") (pintype "power_in"))
      (node (ref "U$5") (pin "9") (pinfunction "GND_9") (pintype "power_in"))
      (node (ref "U$6") (pin "9") (pinfunction "GND_9") (pintype "power_in"))
      (node (ref "U$7") (pin "9") (pinfunction "GND_9") (pintype "power_in"))
      (node (ref "U$8") (pin "9") (pinfunction "GND_9") (pintype "power_in"))
      (node (ref "U$9") (pin "9") (pinfunction "GND_9") (pintype "power_in"))
      (node (ref "X11") (pin "9") (pinfunction "S_9") (pintype "passive"))
    )
    (net (code "2") (name "Net-(IC1A-1D2)") (class "Default")
      (node (ref "IC1") (pin "2") (pinfunction "1Q1_2") (pintype "tri_state"))
      (node (ref "IC1") (pin "46") (pinfunction "1D2_46") (pintype "input"))
      (node (ref "IC2") (pin "1") (pinfunction "I0_1") (pintype "input"))
    )
    (net (code "3") (name "Net-(IC1A-1D3)") (class "Default")
      (node (ref "IC1") (pin "3") (pinfunction "1Q2_3") (pintype "tri_state"))
      (node (ref "IC1") (pin "44") (pinfunction "1D3_44") (pintype "input"))
      (node (ref "IC2") (pin "4") (pinfunction "I0_4") (pintype "input"))
    )
    (net (code "4") (name "Net-(IC1A-1D4)") (class "Default")
      (node (ref "IC1") (pin "43") (pinfunction "1D4_43") (pintype "input"))
      (node (ref "IC1") (pin "5") (pinfunction "1Q3_5") (pintype "tri_state"))
      (node (ref "IC2") (pin "9") (pinfunction "I0_9") (pintype "input"))
    )
    (net (code "5") (name "Net-(IC1A-1D5)") (class "Default")
      (node (ref "IC1") (pin "41") (pinfunction "1D5_41") (pintype "input"))
      (node (ref "IC1") (pin "6") (pinfunction "1Q4_6") (pintype "tri_state"))
      (node (ref "IC2") (pin "12") (pinfunction "I0_12") (pintype "input"))
    )
    (net (code "6") (name "Net-(IC1A-1D6)") (class "Default")
      (node (ref "IC1") (pin "40") (pinfunction "1D6_40") (pintype "input"))
      (node (ref "IC1") (pin "8") (pinfunction "1Q5_8") (pintype "tri_state"))
      (node (ref "IC4") (pin "1") (pinfunction "I0_1") (pintype "input"))
    )
    (net (code "7") (name "Net-(IC1A-1D7)") (class "Default")
      (node (ref "IC1") (pin "38") (pinfunction "1D7_38") (pintype "input"))
      (node (ref "IC1") (pin "9") (pinfunction "1Q6_9") (pintype "tri_state"))
      (node (ref "IC4") (pin "4") (pinfunction "I0_4") (pintype "input"))
    )
    (net (code "8") (name "Net-(IC1A-1D8)") (class "Default")
      (node (ref "IC1") (pin "11") (pinfunction "1Q7_11") (pintype "tri_state"))
      (node (ref "IC1") (pin "37") (pinfunction "1D8_37") (pintype "input"))
      (node (ref "IC4") (pin "9") (pinfunction "I0_9") (pintype "input"))
    )
    (net (code "9") (name "Net-(IC1A-1Q8)") (class "Default")
      (node (ref "IC1") (pin "12") (pinfunction "1Q8_12") (pintype "tri_state"))
      (node (ref "IC1") (pin "36") (pinfunction "2D1_36") (pintype "input"))
      (node (ref "IC4") (pin "12") (pinfunction "I0_12") (pintype "input"))
    )
    (net (code "10") (name "Net-(IC1A-2D2)") (class "Default")
      (node (ref "IC1") (pin "13") (pinfunction "2Q1_13") (pintype "tri_state"))
      (node (ref "IC1") (pin "35") (pinfunction "2D2_35") (pintype "input"))
      (node (ref "IC5") (pin "1") (pinfunction "I0_1") (pintype "input"))
    )
    (net (code "11") (name "Net-(IC1A-2D3)") (class "Default")
      (node (ref "IC1") (pin "14") (pinfunction "2Q2_14") (pintype "tri_state"))
      (node (ref "IC1") (pin "33") (pinfunction "2D3_33") (pintype "input"))
      (node (ref "IC5") (pin "4") (pinfunction "I0_4") (pintype "input"))
    )
    (net (code "12") (name "Net-(IC1A-2D4)") (class "Default")
      (node (ref "IC1") (pin "16") (pinfunction "2Q3_16") (pintype "tri_state"))
      (node (ref "IC1") (pin "32") (pinfunction "2D4_32") (pintype "input"))
      (node (ref "IC5") (pin "9") (pinfunction "I0_9") (pintype "input"))
    )
    (net (code "13") (name "Net-(IC1A-2D5)") (class "Default")
      (node (ref "IC1") (pin "17") (pinfunction "2Q4_17") (pintype "tri_state"))
      (node (ref "IC1") (pin "30") (pinfunction "2D5_30") (pintype "input"))
      (node (ref "IC5") (pin "12") (pinfunction "I0_12") (pintype "input"))
    )
    (net (code "14") (name "Net-(IC1A-2D6)") (class "Default")
      (node (ref "IC1") (pin "19") (pinfunction "2Q5_19") (pintype "tri_state"))
      (node (ref "IC1") (pin "29") (pinfunction "2D6_29") (pintype "input"))
      (node (ref "IC6") (pin "1") (pinfunction "I0_1") (pintype "input"))
    )
    (net (code "15") (name "Net-(IC1A-2D7)") (class "Default")
      (node (ref "IC1") (pin "20") (pinfunction "2Q6_20") (pintype "tri_state"))
      (node (ref "IC1") (pin "27") (pinfunction "2D7_27") (pintype "input"))
      (node (ref "IC6") (pin "4") (pinfunction "I0_4") (pintype "input"))
    )
    (net (code "16") (name "Net-(IC1A-2D8)") (class "Default")
      (node (ref "IC1") (pin "22") (pinfunction "2Q7_22") (pintype "tri_state"))
      (node (ref "IC1") (pin "26") (pinfunction "2D8_26") (pintype "input"))
      (node (ref "IC6") (pin "9") (pinfunction "I0_9") (pintype "input"))
    )
    (net (code "17") (name "Net-(IC1A-2Q8)") (class "Default")
      (node (ref "IC1") (pin "23") (pinfunction "2Q8_23") (pintype "tri_state"))
      (node (ref "IC6") (pin "12") (pinfunction "I0_12") (pintype "input"))
      (node (ref "IC8") (pin "47") (pinfunction "1D1_47") (pintype "input"))
    )
    (net (code "18") (name "Net-(IC2A-O)") (class "Default")
      (node (ref "IC2") (pin "3") (pinfunction "O_3") (pintype "output"))
      (node (ref "U$1") (pin "1") (pinfunction "I1_1") (pintype "input"))
    )
    (net (code "19") (name "Net-(IC2B-O)") (class "Default")
      (node (ref "IC2") (pin "6") (pinfunction "O_6") (pintype "output"))
      (node (ref "U$1") (pin "2") (pinfunction "I2_2") (pintype "input"))
    )
    (net (code "20") (name "Net-(IC2C-O)") (class "Default")
      (node (ref "IC2") (pin "8") (pinfunction "O_8") (pintype "output"))
      (node (ref "U$1") (pin "3") (pinfunction "I3_3") (pintype "input"))
    )
    (net (code "21") (name "Net-(IC2D-O)") (class "Default")
      (node (ref "IC2") (pin "11") (pinfunction "O_11") (pintype "output"))
      (node (ref "U$1") (pin "4") (pinfunction "I4_4") (pintype "input"))
    )
    (net (code "22") (name "Net-(IC3A-1D2)") (class "Default")
      (node (ref "IC3") (pin "2") (pinfunction "1Q1_2") (pintype "tri_state"))
      (node (ref "IC3") (pin "46") (pinfunction "1D2_46") (pintype "input"))
      (node (ref "IC7") (pin "1") (pinfunction "I0_1") (pintype "input"))
    )
    (net (code "23") (name "Net-(IC3A-1D3)") (class "Default")
      (node (ref "IC3") (pin "3") (pinfunction "1Q2_3") (pintype "tri_state"))
      (node (ref "IC3") (pin "44") (pinfunction "1D3_44") (pintype "input"))
      (node (ref "IC7") (pin "4") (pinfunction "I0_4") (pintype "input"))
    )
    (net (code "24") (name "Net-(IC3A-1D4)") (class "Default")
      (node (ref "IC3") (pin "43") (pinfunction "1D4_43") (pintype "input"))
      (node (ref "IC3") (pin "5") (pinfunction "1Q3_5") (pintype "tri_state"))
      (node (ref "IC7") (pin "9") (pinfunction "I0_9") (pintype "input"))
    )
    (net (code "25") (name "Net-(IC3A-1D5)") (class "Default")
      (node (ref "IC3") (pin "41") (pinfunction "1D5_41") (pintype "input"))
      (node (ref "IC3") (pin "6") (pinfunction "1Q4_6") (pintype "tri_state"))
      (node (ref "IC7") (pin "12") (pinfunction "I0_12") (pintype "input"))
    )
    (net (code "26") (name "Net-(IC4A-O)") (class "Default")
      (node (ref "IC4") (pin "3") (pinfunction "O_3") (pintype "output"))
      (node (ref "U$1") (pin "5") (pinfunction "I5_5") (pintype "input"))
    )
    (net (code "27") (name "Net-(IC4B-O)") (class "Default")
      (node (ref "IC4") (pin "6") (pinfunction "O_6") (pintype "output"))
      (node (ref "U$1") (pin "6") (pinfunction "I6_6") (pintype "input"))
    )
    (net (code "28") (name "Net-(IC4C-O)") (class "Default")
      (node (ref "IC4") (pin "8") (pinfunction "O_8") (pintype "output"))
      (node (ref "U$1") (pin "7") (pinfunction "I7_7") (pintype "input"))
    )
    (net (code "29") (name "Net-(IC4D-O)") (class "Default")
      (node (ref "IC4") (pin "11") (pinfunction "O_11") (pintype "output"))
      (node (ref "U$1") (pin "8") (pinfunction "I8_8") (pintype "input"))
    )
    (net (code "30") (name "Net-(IC5A-O)") (class "Default")
      (node (ref "IC5") (pin "3") (pinfunction "O_3") (pintype "output"))
      (node (ref "U$2") (pin "1") (pinfunction "I1_1") (pintype "input"))
    )
    (net (code "31") (name "Net-(IC5B-O)") (class "Default")
      (node (ref "IC5") (pin "6") (pinfunction "O_6") (pintype "output"))
      (node (ref "U$2") (pin "2") (pinfunction "I2_2") (pintype "input"))
    )
    (net (code "32") (name "Net-(IC5C-O)") (class "Default")
      (node (ref "IC5") (pin "8") (pinfunction "O_8") (pintype "output"))
      (node (ref "U$2") (pin "3") (pinfunction "I3_3") (pintype "input"))
    )
    (net (code "33") (name "Net-(IC5D-O)") (class "Default")
      (node (ref "IC5") (pin "11") (pinfunction "O_11") (pintype "output"))
      (node (ref "U$2") (pin "4") (pinfunction "I4_4") (pintype "input"))
    )
    (net (code "34") (name "Net-(IC6A-O)") (class "Default")
      (node (ref "IC6") (pin "3") (pinfunction "O_3") (pintype "output"))
      (node (ref "U$2") (pin "5") (pinfunction "I5_5") (pintype "input"))
    )
    (net (code "35") (name "Net-(IC6B-O)") (class "Default")
      (node (ref "IC6") (pin "6") (pinfunction "O_6") (pintype "output"))
      (node (ref "U$2") (pin "6") (pinfunction "I6_6") (pintype "input"))
    )
    (net (code "36") (name "Net-(IC6C-O)") (class "Default")
      (node (ref "IC6") (pin "8") (pinfunction "O_8") (pintype "output"))
      (node (ref "U$2") (pin "7") (pinfunction "I7_7") (pintype "input"))
    )
    (net (code "37") (name "Net-(IC6D-O)") (class "Default")
      (node (ref "IC6") (pin "11") (pinfunction "O_11") (pintype "output"))
      (node (ref "U$2") (pin "8") (pinfunction "I8_8") (pintype "input"))
    )
    (net (code "38") (name "Net-(IC7A-O)") (class "Default")
      (node (ref "IC7") (pin "3") (pinfunction "O_3") (pintype "output"))
      (node (ref "U$5") (pin "1") (pinfunction "I1_1") (pintype "input"))
    )
    (net (code "39") (name "Net-(IC7B-O)") (class "Default")
      (node (ref "IC7") (pin "6") (pinfunction "O_6") (pintype "output"))
      (node (ref "U$5") (pin "2") (pinfunction "I2_2") (pintype "input"))
    )
    (net (code "40") (name "Net-(IC7C-O)") (class "Default")
      (node (ref "IC7") (pin "8") (pinfunction "O_8") (pintype "output"))
      (node (ref "U$5") (pin "3") (pinfunction "I3_3") (pintype "input"))
    )
    (net (code "41") (name "Net-(IC7D-O)") (class "Default")
      (node (ref "IC7") (pin "11") (pinfunction "O_11") (pintype "output"))
      (node (ref "U$5") (pin "4") (pinfunction "I4_4") (pintype "input"))
    )
    (net (code "42") (name "Net-(IC8A-1D2)") (class "Default")
      (node (ref "IC8") (pin "2") (pinfunction "1Q1_2") (pintype "tri_state"))
      (node (ref "IC8") (pin "46") (pinfunction "1D2_46") (pintype "input"))
      (node (ref "IC9") (pin "1") (pinfunction "I0_1") (pintype "input"))
    )
    (net (code "43") (name "Net-(IC8A-1D3)") (class "Default")
      (node (ref "IC8") (pin "3") (pinfunction "1Q2_3") (pintype "tri_state"))
      (node (ref "IC8") (pin "44") (pinfunction "1D3_44") (pintype "input"))
      (node (ref "IC9") (pin "4") (pinfunction "I0_4") (pintype "input"))
    )
    (net (code "44") (name "Net-(IC8A-1D4)") (class "Default")
      (node (ref "IC8") (pin "43") (pinfunction "1D4_43") (pintype "input"))
      (node (ref "IC8") (pin "5") (pinfunction "1Q3_5") (pintype "tri_state"))
      (node (ref "IC9") (pin "9") (pinfunction "I0_9") (pintype "input"))
    )
    (net (code "45") (name "Net-(IC8A-1D5)") (class "Default")
      (node (ref "IC8") (pin "41") (pinfunction "1D5_41") (pintype "input"))
      (node (ref "IC8") (pin "6") (pinfunction "1Q4_6") (pintype "tri_state"))
      (node (ref "IC9") (pin "12") (pinfunction "I0_12") (pintype "input"))
    )
    (net (code "46") (name "Net-(IC9A-O)") (class "Default")
      (node (ref "IC9") (pin "3") (pinfunction "O_3") (pintype "output"))
      (node (ref "U$3") (pin "1") (pinfunction "I1_1") (pintype "input"))
    )
    (net (code "47") (name "Net-(IC9B-O)") (class "Default")
      (node (ref "IC9") (pin "6") (pinfunction "O_6") (pintype "output"))
      (node (ref "U$3") (pin "2") (pinfunction "I2_2") (pintype "input"))
    )
    (net (code "48") (name "Net-(IC9C-O)") (class "Default")
      (node (ref "IC9") (pin "8") (pinfunction "O_8") (pintype "output"))
      (node (ref "U$3") (pin "3") (pinfunction "I3_3") (pintype "input"))
    )
    (net (code "49") (name "Net-(IC9D-O)") (class "Default")
      (node (ref "IC9") (pin "11") (pinfunction "O_11") (pintype "output"))
      (node (ref "U$3") (pin "4") (pinfunction "I4_4") (pintype "input"))
    )
    (net (code "50") (name "Net-(IC10A-I0)") (class "Default")
      (node (ref "IC10") (pin "1") (pinfunction "I0_1") (pintype "input"))
      (node (ref "IC3") (pin "40") (pinfunction "1D6_40") (pintype "input"))
      (node (ref "IC3") (pin "8") (pinfunction "1Q5_8") (pintype "tri_state"))
    )
    (net (code "51") (name "Net-(IC10A-O)") (class "Default")
      (node (ref "IC10") (pin "3") (pinfunction "O_3") (pintype "output"))
      (node (ref "U$5") (pin "5") (pinfunction "I5_5") (pintype "input"))
    )
    (net (code "52") (name "Net-(IC10B-I0)") (class "Default")
      (node (ref "IC10") (pin "4") (pinfunction "I0_4") (pintype "input"))
      (node (ref "IC3") (pin "38") (pinfunction "1D7_38") (pintype "input"))
      (node (ref "IC3") (pin "9") (pinfunction "1Q6_9") (pintype "tri_state"))
    )
    (net (code "53") (name "Net-(IC10B-O)") (class "Default")
      (node (ref "IC10") (pin "6") (pinfunction "O_6") (pintype "output"))
      (node (ref "U$5") (pin "6") (pinfunction "I6_6") (pintype "input"))
    )
    (net (code "54") (name "Net-(IC10C-I0)") (class "Default")
      (node (ref "IC10") (pin "9") (pinfunction "I0_9") (pintype "input"))
      (node (ref "IC3") (pin "11") (pinfunction "1Q7_11") (pintype "tri_state"))
      (node (ref "IC3") (pin "37") (pinfunction "1D8_37") (pintype "input"))
    )
    (net (code "55") (name "Net-(IC10C-O)") (class "Default")
      (node (ref "IC10") (pin "8") (pinfunction "O_8") (pintype "output"))
      (node (ref "U$5") (pin "7") (pinfunction "I7_7") (pintype "input"))
    )
    (net (code "56") (name "Net-(IC10D-I0)") (class "Default")
      (node (ref "IC10") (pin "12") (pinfunction "I0_12") (pintype "input"))
      (node (ref "IC3") (pin "12") (pinfunction "1Q8_12") (pintype "tri_state"))
      (node (ref "IC3") (pin "36") (pinfunction "2D1_36") (pintype "input"))
    )
    (net (code "57") (name "Net-(IC10D-O)") (class "Default")
      (node (ref "IC10") (pin "11") (pinfunction "O_11") (pintype "output"))
      (node (ref "U$5") (pin "8") (pinfunction "I8_8") (pintype "input"))
    )
    (net (code "58") (name "Net-(IC11A-I0)") (class "Default")
      (node (ref "IC11") (pin "1") (pinfunction "I0_1") (pintype "input"))
      (node (ref "IC8") (pin "40") (pinfunction "1D6_40") (pintype "input"))
      (node (ref "IC8") (pin "8") (pinfunction "1Q5_8") (pintype "tri_state"))
    )
    (net (code "59") (name "Net-(IC11A-O)") (class "Default")
      (node (ref "IC11") (pin "3") (pinfunction "O_3") (pintype "output"))
      (node (ref "U$3") (pin "5") (pinfunction "I5_5") (pintype "input"))
    )
    (net (code "60") (name "Net-(IC11B-I0)") (class "Default")
      (node (ref "IC11") (pin "4") (pinfunction "I0_4") (pintype "input"))
      (node (ref "IC8") (pin "38") (pinfunction "1D7_38") (pintype "input"))
      (node (ref "IC8") (pin "9") (pinfunction "1Q6_9") (pintype "tri_state"))
    )
    (net (code "61") (name "Net-(IC11B-O)") (class "Default")
      (node (ref "IC11") (pin "6") (pinfunction "O_6") (pintype "output"))
      (node (ref "U$3") (pin "6") (pinfunction "I6_6") (pintype "input"))
    )
    (net (code "62") (name "Net-(IC11C-I0)") (class "Default")
      (node (ref "IC11") (pin "9") (pinfunction "I0_9") (pintype "input"))
      (node (ref "IC8") (pin "11") (pinfunction "1Q7_11") (pintype "tri_state"))
      (node (ref "IC8") (pin "37") (pinfunction "1D8_37") (pintype "input"))
    )
    (net (code "63") (name "Net-(IC11C-O)") (class "Default")
      (node (ref "IC11") (pin "8") (pinfunction "O_8") (pintype "output"))
      (node (ref "U$3") (pin "7") (pinfunction "I7_7") (pintype "input"))
    )
    (net (code "64") (name "Net-(IC11D-I0)") (class "Default")
      (node (ref "IC11") (pin "12") (pinfunction "I0_12") (pintype "input"))
      (node (ref "IC8") (pin "12") (pinfunction "1Q8_12") (pintype "tri_state"))
      (node (ref "IC8") (pin "36") (pinfunction "2D1_36") (pintype "input"))
    )
    (net (code "65") (name "Net-(IC11D-O)") (class "Default")
      (node (ref "IC11") (pin "11") (pinfunction "O_11") (pintype "output"))
      (node (ref "U$3") (pin "8") (pinfunction "I8_8") (pintype "input"))
    )
    (net (code "66") (name "Net-(IC12A-I0)") (class "Default")
      (node (ref "IC12") (pin "1") (pinfunction "I0_1") (pintype "input"))
      (node (ref "IC8") (pin "13") (pinfunction "2Q1_13") (pintype "tri_state"))
      (node (ref "IC8") (pin "35") (pinfunction "2D2_35") (pintype "input"))
    )
    (net (code "67") (name "Net-(IC12A-O)") (class "Default")
      (node (ref "IC12") (pin "3") (pinfunction "O_3") (pintype "output"))
      (node (ref "U$4") (pin "1") (pinfunction "I1_1") (pintype "input"))
    )
    (net (code "68") (name "Net-(IC12B-I0)") (class "Default")
      (node (ref "IC12") (pin "4") (pinfunction "I0_4") (pintype "input"))
      (node (ref "IC8") (pin "14") (pinfunction "2Q2_14") (pintype "tri_state"))
      (node (ref "IC8") (pin "33") (pinfunction "2D3_33") (pintype "input"))
    )
    (net (code "69") (name "Net-(IC12B-O)") (class "Default")
      (node (ref "IC12") (pin "6") (pinfunction "O_6") (pintype "output"))
      (node (ref "U$4") (pin "2") (pinfunction "I2_2") (pintype "input"))
    )
    (net (code "70") (name "Net-(IC12C-I0)") (class "Default")
      (node (ref "IC12") (pin "9") (pinfunction "I0_9") (pintype "input"))
      (node (ref "IC8") (pin "16") (pinfunction "2Q3_16") (pintype "tri_state"))
      (node (ref "IC8") (pin "32") (pinfunction "2D4_32") (pintype "input"))
    )
    (net (code "71") (name "Net-(IC12C-O)") (class "Default")
      (node (ref "IC12") (pin "8") (pinfunction "O_8") (pintype "output"))
      (node (ref "U$4") (pin "3") (pinfunction "I3_3") (pintype "input"))
    )
    (net (code "72") (name "Net-(IC12D-I0)") (class "Default")
      (node (ref "IC12") (pin "12") (pinfunction "I0_12") (pintype "input"))
      (node (ref "IC8") (pin "17") (pinfunction "2Q4_17") (pintype "tri_state"))
      (node (ref "IC8") (pin "30") (pinfunction "2D5_30") (pintype "input"))
    )
    (net (code "73") (name "Net-(IC12D-O)") (class "Default")
      (node (ref "IC12") (pin "11") (pinfunction "O_11") (pintype "output"))
      (node (ref "U$4") (pin "4") (pinfunction "I4_4") (pintype "input"))
    )
    (net (code "74") (name "Net-(IC13A-I0)") (class "Default")
      (node (ref "IC13") (pin "1") (pinfunction "I0_1") (pintype "input"))
      (node (ref "IC8") (pin "19") (pinfunction "2Q5_19") (pintype "tri_state"))
      (node (ref "IC8") (pin "29") (pinfunction "2D6_29") (pintype "input"))
    )
    (net (code "75") (name "Net-(IC13A-O)") (class "Default")
      (node (ref "IC13") (pin "3") (pinfunction "O_3") (pintype "output"))
      (node (ref "U$4") (pin "5") (pinfunction "I5_5") (pintype "input"))
    )
    (net (code "76") (name "Net-(IC13B-I0)") (class "Default")
      (node (ref "IC13") (pin "4") (pinfunction "I0_4") (pintype "input"))
      (node (ref "IC8") (pin "20") (pinfunction "2Q6_20") (pintype "tri_state"))
      (node (ref "IC8") (pin "27") (pinfunction "2D7_27") (pintype "input"))
    )
    (net (code "77") (name "Net-(IC13B-O)") (class "Default")
      (node (ref "IC13") (pin "6") (pinfunction "O_6") (pintype "output"))
      (node (ref "U$4") (pin "6") (pinfunction "I6_6") (pintype "input"))
    )
    (net (code "78") (name "Net-(IC13C-I0)") (class "Default")
      (node (ref "IC13") (pin "9") (pinfunction "I0_9") (pintype "input"))
      (node (ref "IC8") (pin "22") (pinfunction "2Q7_22") (pintype "tri_state"))
      (node (ref "IC8") (pin "26") (pinfunction "2D8_26") (pintype "input"))
    )
    (net (code "79") (name "Net-(IC13C-O)") (class "Default")
      (node (ref "IC13") (pin "8") (pinfunction "O_8") (pintype "output"))
      (node (ref "U$4") (pin "7") (pinfunction "I7_7") (pintype "input"))
    )
    (net (code "80") (name "Net-(IC13D-I0)") (class "Default")
      (node (ref "IC13") (pin "12") (pinfunction "I0_12") (pintype "input"))
      (node (ref "IC51") (pin "47") (pinfunction "1D1_47") (pintype "input"))
      (node (ref "IC8") (pin "23") (pinfunction "2Q8_23") (pintype "tri_state"))
    )
    (net (code "81") (name "Net-(IC13D-O)") (class "Default")
      (node (ref "IC13") (pin "11") (pinfunction "O_11") (pintype "output"))
      (node (ref "U$4") (pin "8") (pinfunction "I8_8") (pintype "input"))
    )
    (net (code "82") (name "Net-(IC14A-I0)") (class "Default")
      (node (ref "IC14") (pin "1") (pinfunction "I0_1") (pintype "input"))
      (node (ref "IC3") (pin "13") (pinfunction "2Q1_13") (pintype "tri_state"))
      (node (ref "IC3") (pin "35") (pinfunction "2D2_35") (pintype "input"))
    )
    (net (code "83") (name "Net-(IC14A-O)") (class "Default")
      (node (ref "IC14") (pin "3") (pinfunction "O_3") (pintype "output"))
      (node (ref "U$6") (pin "1") (pinfunction "I1_1") (pintype "input"))
    )
    (net (code "84") (name "Net-(IC14B-I0)") (class "Default")
      (node (ref "IC14") (pin "4") (pinfunction "I0_4") (pintype "input"))
      (node (ref "IC3") (pin "14") (pinfunction "2Q2_14") (pintype "tri_state"))
      (node (ref "IC3") (pin "33") (pinfunction "2D3_33") (pintype "input"))
    )
    (net (code "85") (name "Net-(IC14B-O)") (class "Default")
      (node (ref "IC14") (pin "6") (pinfunction "O_6") (pintype "output"))
      (node (ref "U$6") (pin "2") (pinfunction "I2_2") (pintype "input"))
    )
    (net (code "86") (name "Net-(IC14C-I0)") (class "Default")
      (node (ref "IC14") (pin "9") (pinfunction "I0_9") (pintype "input"))
      (node (ref "IC3") (pin "16") (pinfunction "2Q3_16") (pintype "tri_state"))
      (node (ref "IC3") (pin "32") (pinfunction "2D4_32") (pintype "input"))
    )
    (net (code "87") (name "Net-(IC14C-O)") (class "Default")
      (node (ref "IC14") (pin "8") (pinfunction "O_8") (pintype "output"))
      (node (ref "U$6") (pin "3") (pinfunction "I3_3") (pintype "input"))
    )
    (net (code "88") (name "Net-(IC14D-I0)") (class "Default")
      (node (ref "IC14") (pin "12") (pinfunction "I0_12") (pintype "input"))
      (node (ref "IC3") (pin "17") (pinfunction "2Q4_17") (pintype "tri_state"))
      (node (ref "IC3") (pin "30") (pinfunction "2D5_30") (pintype "input"))
    )
    (net (code "89") (name "Net-(IC14D-O)") (class "Default")
      (node (ref "IC14") (pin "11") (pinfunction "O_11") (pintype "output"))
      (node (ref "U$6") (pin "4") (pinfunction "I4_4") (pintype "input"))
    )
    (net (code "90") (name "Net-(IC15A-I0)") (class "Default")
      (node (ref "IC15") (pin "1") (pinfunction "I0_1") (pintype "input"))
      (node (ref "IC3") (pin "19") (pinfunction "2Q5_19") (pintype "tri_state"))
      (node (ref "IC3") (pin "29") (pinfunction "2D6_29") (pintype "input"))
    )
    (net (code "91") (name "Net-(IC15A-O)") (class "Default")
      (node (ref "IC15") (pin "3") (pinfunction "O_3") (pintype "output"))
      (node (ref "U$6") (pin "5") (pinfunction "I5_5") (pintype "input"))
    )
    (net (code "92") (name "Net-(IC15B-I0)") (class "Default")
      (node (ref "IC15") (pin "4") (pinfunction "I0_4") (pintype "input"))
      (node (ref "IC3") (pin "20") (pinfunction "2Q6_20") (pintype "tri_state"))
      (node (ref "IC3") (pin "27") (pinfunction "2D7_27") (pintype "input"))
    )
    (net (code "93") (name "Net-(IC15B-O)") (class "Default")
      (node (ref "IC15") (pin "6") (pinfunction "O_6") (pintype "output"))
      (node (ref "U$6") (pin "6") (pinfunction "I6_6") (pintype "input"))
    )
    (net (code "94") (name "Net-(IC15C-I0)") (class "Default")
      (node (ref "IC15") (pin "9") (pinfunction "I0_9") (pintype "input"))
      (node (ref "IC3") (pin "22") (pinfunction "2Q7_22") (pintype "tri_state"))
      (node (ref "IC3") (pin "26") (pinfunction "2D8_26") (pintype "input"))
    )
    (net (code "95") (name "Net-(IC15C-O)") (class "Default")
      (node (ref "IC15") (pin "8") (pinfunction "O_8") (pintype "output"))
      (node (ref "U$6") (pin "7") (pinfunction "I7_7") (pintype "input"))
    )
    (net (code "96") (name "Net-(IC15D-I0)") (class "Default")
      (node (ref "IC15") (pin "12") (pinfunction "I0_12") (pintype "input"))
      (node (ref "IC16") (pin "47") (pinfunction "1D1_47") (pintype "input"))
      (node (ref "IC3") (pin "23") (pinfunction "2Q8_23") (pintype "tri_state"))
    )
    (net (code "97") (name "Net-(IC15D-O)") (class "Default")
      (node (ref "IC15") (pin "11") (pinfunction "O_11") (pintype "output"))
      (node (ref "U$6") (pin "8") (pinfunction "I8_8") (pintype "input"))
    )
    (net (code "98") (name "Net-(IC16A-1CLK)") (class "Default")
      (node (ref "IC1") (pin "25") (pinfunction "2CLK_25") (pintype "input"))
      (node (ref "IC1") (pin "48") (pinfunction "1CLK_48") (pintype "input"))
      (node (ref "IC16") (pin "25") (pinfunction "2CLK_25") (pintype "input"))
      (node (ref "IC16") (pin "48") (pinfunction "1CLK_48") (pintype "input"))
      (node (ref "IC21") (pin "25") (pinfunction "2CLK_25") (pintype "input"))
      (node (ref "IC21") (pin "48") (pinfunction "1CLK_48") (pintype "input"))
      (node (ref "IC26") (pin "25") (pinfunction "2CLK_25") (pintype "input"))
      (node (ref "IC26") (pin "48") (pinfunction "1CLK_48") (pintype "input"))
      (node (ref "IC3") (pin "25") (pinfunction "2CLK_25") (pintype "input"))
      (node (ref "IC3") (pin "48") (pinfunction "1CLK_48") (pintype "input"))
      (node (ref "IC41") (pin "25") (pinfunction "2CLK_25") (pintype "input"))
      (node (ref "IC41") (pin "48") (pinfunction "1CLK_48") (pintype "input"))
      (node (ref "IC46") (pin "25") (pinfunction "2CLK_25") (pintype "input"))
      (node (ref "IC46") (pin "48") (pinfunction "1CLK_48") (pintype "input"))
      (node (ref "IC51") (pin "25") (pinfunction "2CLK_25") (pintype "input"))
      (node (ref "IC51") (pin "48") (pinfunction "1CLK_48") (pintype "input"))
      (node (ref "IC56") (pin "25") (pinfunction "2CLK_25") (pintype "input"))
      (node (ref "IC56") (pin "48") (pinfunction "1CLK_48") (pintype "input"))
      (node (ref "IC8") (pin "25") (pinfunction "2CLK_25") (pintype "input"))
      (node (ref "IC8") (pin "48") (pinfunction "1CLK_48") (pintype "input"))
      (node (ref "X11") (pin "5") (pinfunction "S_5") (pintype "passive"))
    )
    (net (code "99") (name "Net-(IC16A-1D2)") (class "Default")
      (node (ref "IC16") (pin "2") (pinfunction "1Q1_2") (pintype "tri_state"))
      (node (ref "IC16") (pin "46") (pinfunction "1D2_46") (pintype "input"))
      (node (ref "IC17") (pin "1") (pinfunction "I0_1") (pintype "input"))
    )
    (net (code "100") (name "Net-(IC16A-1D3)") (class "Default")
      (node (ref "IC16") (pin "3") (pinfunction "1Q2_3") (pintype "tri_state"))
      (node (ref "IC16") (pin "44") (pinfunction "1D3_44") (pintype "input"))
      (node (ref "IC17") (pin "4") (pinfunction "I0_4") (pintype "input"))
    )
    (net (code "101") (name "Net-(IC16A-1D4)") (class "Default")
      (node (ref "IC16") (pin "43") (pinfunction "1D4_43") (pintype "input"))
      (node (ref "IC16") (pin "5") (pinfunction "1Q3_5") (pintype "tri_state"))
      (node (ref "IC17") (pin "9") (pinfunction "I0_9") (pintype "input"))
    )
    (net (code "102") (name "Net-(IC16A-1D5)") (class "Default")
      (node (ref "IC16") (pin "41") (pinfunction "1D5_41") (pintype "input"))
      (node (ref "IC16") (pin "6") (pinfunction "1Q4_6") (pintype "tri_state"))
      (node (ref "IC17") (pin "12") (pinfunction "I0_12") (pintype "input"))
    )
    (net (code "103") (name "Net-(IC16A-1D6)") (class "Default")
      (node (ref "IC16") (pin "40") (pinfunction "1D6_40") (pintype "input"))
      (node (ref "IC16") (pin "8") (pinfunction "1Q5_8") (pintype "tri_state"))
      (node (ref "IC18") (pin "1") (pinfunction "I0_1") (pintype "input"))
    )
    (net (code "104") (name "Net-(IC16A-1D7)") (class "Default")
      (node (ref "IC16") (pin "38") (pinfunction "1D7_38") (pintype "input"))
      (node (ref "IC16") (pin "9") (pinfunction "1Q6_9") (pintype "tri_state"))
      (node (ref "IC18") (pin "4") (pinfunction "I0_4") (pintype "input"))
    )
    (net (code "105") (name "Net-(IC16A-1D8)") (class "Default")
      (node (ref "IC16") (pin "11") (pinfunction "1Q7_11") (pintype "tri_state"))
      (node (ref "IC16") (pin "37") (pinfunction "1D8_37") (pintype "input"))
      (node (ref "IC18") (pin "9") (pinfunction "I0_9") (pintype "input"))
    )
    (net (code "106") (name "Net-(IC16A-1Q8)") (class "Default")
      (node (ref "IC16") (pin "12") (pinfunction "1Q8_12") (pintype "tri_state"))
      (node (ref "IC16") (pin "36") (pinfunction "2D1_36") (pintype "input"))
      (node (ref "IC18") (pin "12") (pinfunction "I0_12") (pintype "input"))
    )
    (net (code "107") (name "Net-(IC16A-2D2)") (class "Default")
      (node (ref "IC16") (pin "13") (pinfunction "2Q1_13") (pintype "tri_state"))
      (node (ref "IC16") (pin "35") (pinfunction "2D2_35") (pintype "input"))
      (node (ref "IC19") (pin "1") (pinfunction "I0_1") (pintype "input"))
    )
    (net (code "108") (name "Net-(IC16A-2D3)") (class "Default")
      (node (ref "IC16") (pin "14") (pinfunction "2Q2_14") (pintype "tri_state"))
      (node (ref "IC16") (pin "33") (pinfunction "2D3_33") (pintype "input"))
      (node (ref "IC19") (pin "4") (pinfunction "I0_4") (pintype "input"))
    )
    (net (code "109") (name "Net-(IC16A-2D4)") (class "Default")
      (node (ref "IC16") (pin "16") (pinfunction "2Q3_16") (pintype "tri_state"))
      (node (ref "IC16") (pin "32") (pinfunction "2D4_32") (pintype "input"))
      (node (ref "IC19") (pin "9") (pinfunction "I0_9") (pintype "input"))
    )
    (net (code "110") (name "Net-(IC16A-2D5)") (class "Default")
      (node (ref "IC16") (pin "17") (pinfunction "2Q4_17") (pintype "tri_state"))
      (node (ref "IC16") (pin "30") (pinfunction "2D5_30") (pintype "input"))
      (node (ref "IC19") (pin "12") (pinfunction "I0_12") (pintype "input"))
    )
    (net (code "111") (name "Net-(IC16A-2D6)") (class "Default")
      (node (ref "IC16") (pin "19") (pinfunction "2Q5_19") (pintype "tri_state"))
      (node (ref "IC16") (pin "29") (pinfunction "2D6_29") (pintype "input"))
      (node (ref "IC20") (pin "1") (pinfunction "I0_1") (pintype "input"))
    )
    (net (code "112") (name "Net-(IC16A-2D7)") (class "Default")
      (node (ref "IC16") (pin "20") (pinfunction "2Q6_20") (pintype "tri_state"))
      (node (ref "IC16") (pin "27") (pinfunction "2D7_27") (pintype "input"))
      (node (ref "IC20") (pin "4") (pinfunction "I0_4") (pintype "input"))
    )
    (net (code "113") (name "Net-(IC16A-2D8)") (class "Default")
      (node (ref "IC16") (pin "22") (pinfunction "2Q7_22") (pintype "tri_state"))
      (node (ref "IC16") (pin "26") (pinfunction "2D8_26") (pintype "input"))
      (node (ref "IC20") (pin "9") (pinfunction "I0_9") (pintype "input"))
    )
    (net (code "114") (name "Net-(IC16A-2Q8)") (class "Default")
      (node (ref "IC1") (pin "47") (pinfunction "1D1_47") (pintype "input"))
      (node (ref "IC16") (pin "23") (pinfunction "2Q8_23") (pintype "tri_state"))
      (node (ref "IC20") (pin "12") (pinfunction "I0_12") (pintype "input"))
    )
    (net (code "115") (name "Net-(IC17A-O)") (class "Default")
      (node (ref "IC17") (pin "3") (pinfunction "O_3") (pintype "output"))
      (node (ref "U$7") (pin "1") (pinfunction "I1_1") (pintype "input"))
    )
    (net (code "116") (name "Net-(IC17B-O)") (class "Default")
      (node (ref "IC17") (pin "6") (pinfunction "O_6") (pintype "output"))
      (node (ref "U$7") (pin "2") (pinfunction "I2_2") (pintype "input"))
    )
    (net (code "117") (name "Net-(IC17C-O)") (class "Default")
      (node (ref "IC17") (pin "8") (pinfunction "O_8") (pintype "output"))
      (node (ref "U$7") (pin "3") (pinfunction "I3_3") (pintype "input"))
    )
    (net (code "118") (name "Net-(IC17D-O)") (class "Default")
      (node (ref "IC17") (pin "11") (pinfunction "O_11") (pintype "output"))
      (node (ref "U$7") (pin "4") (pinfunction "I4_4") (pintype "input"))
    )
    (net (code "119") (name "Net-(IC18A-O)") (class "Default")
      (node (ref "IC18") (pin "3") (pinfunction "O_3") (pintype "output"))
      (node (ref "U$7") (pin "5") (pinfunction "I5_5") (pintype "input"))
    )
    (net (code "120") (name "Net-(IC18B-O)") (class "Default")
      (node (ref "IC18") (pin "6") (pinfunction "O_6") (pintype "output"))
      (node (ref "U$7") (pin "6") (pinfunction "I6_6") (pintype "input"))
    )
    (net (code "121") (name "Net-(IC18C-O)") (class "Default")
      (node (ref "IC18") (pin "8") (pinfunction "O_8") (pintype "output"))
      (node (ref "U$7") (pin "7") (pinfunction "I7_7") (pintype "input"))
    )
    (net (code "122") (name "Net-(IC18D-O)") (class "Default")
      (node (ref "IC18") (pin "11") (pinfunction "O_11") (pintype "output"))
      (node (ref "U$7") (pin "8") (pinfunction "I8_8") (pintype "input"))
    )
    (net (code "123") (name "Net-(IC19A-O)") (class "Default")
      (node (ref "IC19") (pin "3") (pinfunction "O_3") (pintype "output"))
      (node (ref "U$8") (pin "1") (pinfunction "I1_1") (pintype "input"))
    )
    (net (code "124") (name "Net-(IC19B-O)") (class "Default")
      (node (ref "IC19") (pin "6") (pinfunction "O_6") (pintype "output"))
      (node (ref "U$8") (pin "2") (pinfunction "I2_2") (pintype "input"))
    )
    (net (code "125") (name "Net-(IC19C-O)") (class "Default")
      (node (ref "IC19") (pin "8") (pinfunction "O_8") (pintype "output"))
      (node (ref "U$8") (pin "3") (pinfunction "I3_3") (pintype "input"))
    )
    (net (code "126") (name "Net-(IC19D-O)") (class "Default")
      (node (ref "IC19") (pin "11") (pinfunction "O_11") (pintype "output"))
      (node (ref "U$8") (pin "4") (pinfunction "I4_4") (pintype "input"))
    )
    (net (code "127") (name "Net-(IC20A-O)") (class "Default")
      (node (ref "IC20") (pin "3") (pinfunction "O_3") (pintype "output"))
      (node (ref "U$8") (pin "5") (pinfunction "I5_5") (pintype "input"))
    )
    (net (code "128") (name "Net-(IC20B-O)") (class "Default")
      (node (ref "IC20") (pin "6") (pinfunction "O_6") (pintype "output"))
      (node (ref "U$8") (pin "6") (pinfunction "I6_6") (pintype "input"))
    )
    (net (code "129") (name "Net-(IC20C-O)") (class "Default")
      (node (ref "IC20") (pin "8") (pinfunction "O_8") (pintype "output"))
      (node (ref "U$8") (pin "7") (pinfunction "I7_7") (pintype "input"))
    )
    (net (code "130") (name "Net-(IC20D-O)") (class "Default")
      (node (ref "IC20") (pin "11") (pinfunction "O_11") (pintype "output"))
      (node (ref "U$8") (pin "8") (pinfunction "I8_8") (pintype "input"))
    )
    (net (code "131") (name "Net-(IC21A-1D1)") (class "Default")
      (node (ref "IC21") (pin "47") (pinfunction "1D1_47") (pintype "input"))
      (node (ref "X11") (pin "4") (pinfunction "S_4") (pintype "passive"))
    )
    (net (code "132") (name "Net-(IC21A-1D2)") (class "Default")
      (node (ref "IC21") (pin "2") (pinfunction "1Q1_2") (pintype "tri_state"))
      (node (ref "IC21") (pin "46") (pinfunction "1D2_46") (pintype "input"))
      (node (ref "IC22") (pin "1") (pinfunction "I0_1") (pintype "input"))
    )
    (net (code "133") (name "Net-(IC21A-1D3)") (class "Default")
      (node (ref "IC21") (pin "3") (pinfunction "1Q2_3") (pintype "tri_state"))
      (node (ref "IC21") (pin "44") (pinfunction "1D3_44") (pintype "input"))
      (node (ref "IC22") (pin "4") (pinfunction "I0_4") (pintype "input"))
    )
    (net (code "134") (name "Net-(IC21A-1D4)") (class "Default")
      (node (ref "IC21") (pin "43") (pinfunction "1D4_43") (pintype "input"))
      (node (ref "IC21") (pin "5") (pinfunction "1Q3_5") (pintype "tri_state"))
      (node (ref "IC22") (pin "9") (pinfunction "I0_9") (pintype "input"))
    )
    (net (code "135") (name "Net-(IC21A-1D5)") (class "Default")
      (node (ref "IC21") (pin "41") (pinfunction "1D5_41") (pintype "input"))
      (node (ref "IC21") (pin "6") (pinfunction "1Q4_6") (pintype "tri_state"))
      (node (ref "IC22") (pin "12") (pinfunction "I0_12") (pintype "input"))
    )
    (net (code "136") (name "Net-(IC21A-1D6)") (class "Default")
      (node (ref "IC21") (pin "40") (pinfunction "1D6_40") (pintype "input"))
      (node (ref "IC21") (pin "8") (pinfunction "1Q5_8") (pintype "tri_state"))
      (node (ref "IC23") (pin "1") (pinfunction "I0_1") (pintype "input"))
    )
    (net (code "137") (name "Net-(IC21A-1D7)") (class "Default")
      (node (ref "IC21") (pin "38") (pinfunction "1D7_38") (pintype "input"))
      (node (ref "IC21") (pin "9") (pinfunction "1Q6_9") (pintype "tri_state"))
      (node (ref "IC23") (pin "4") (pinfunction "I0_4") (pintype "input"))
    )
    (net (code "138") (name "Net-(IC21A-1D8)") (class "Default")
      (node (ref "IC21") (pin "11") (pinfunction "1Q7_11") (pintype "tri_state"))
      (node (ref "IC21") (pin "37") (pinfunction "1D8_37") (pintype "input"))
      (node (ref "IC23") (pin "9") (pinfunction "I0_9") (pintype "input"))
    )
    (net (code "139") (name "Net-(IC21A-1Q8)") (class "Default")
      (node (ref "IC21") (pin "12") (pinfunction "1Q8_12") (pintype "tri_state"))
      (node (ref "IC21") (pin "36") (pinfunction "2D1_36") (pintype "input"))
      (node (ref "IC23") (pin "12") (pinfunction "I0_12") (pintype "input"))
    )
    (net (code "140") (name "Net-(IC21A-2D2)") (class "Default")
      (node (ref "IC21") (pin "13") (pinfunction "2Q1_13") (pintype "tri_state"))
      (node (ref "IC21") (pin "35") (pinfunction "2D2_35") (pintype "input"))
      (node (ref "IC24") (pin "1") (pinfunction "I0_1") (pintype "input"))
    )
    (net (code "141") (name "Net-(IC21A-2D3)") (class "Default")
      (node (ref "IC21") (pin "14") (pinfunction "2Q2_14") (pintype "tri_state"))
      (node (ref "IC21") (pin "33") (pinfunction "2D3_33") (pintype "input"))
      (node (ref "IC24") (pin "4") (pinfunction "I0_4") (pintype "input"))
    )
    (net (code "142") (name "Net-(IC21A-2D4)") (class "Default")
      (node (ref "IC21") (pin "16") (pinfunction "2Q3_16") (pintype "tri_state"))
      (node (ref "IC21") (pin "32") (pinfunction "2D4_32") (pintype "input"))
      (node (ref "IC24") (pin "9") (pinfunction "I0_9") (pintype "input"))
    )
    (net (code "143") (name "Net-(IC21A-2D5)") (class "Default")
      (node (ref "IC21") (pin "17") (pinfunction "2Q4_17") (pintype "tri_state"))
      (node (ref "IC21") (pin "30") (pinfunction "2D5_30") (pintype "input"))
      (node (ref "IC24") (pin "12") (pinfunction "I0_12") (pintype "input"))
    )
    (net (code "144") (name "Net-(IC21A-2D6)") (class "Default")
      (node (ref "IC21") (pin "19") (pinfunction "2Q5_19") (pintype "tri_state"))
      (node (ref "IC21") (pin "29") (pinfunction "2D6_29") (pintype "input"))
      (node (ref "IC25") (pin "1") (pinfunction "I0_1") (pintype "input"))
    )
    (net (code "145") (name "Net-(IC21A-2D7)") (class "Default")
      (node (ref "IC21") (pin "20") (pinfunction "2Q6_20") (pintype "tri_state"))
      (node (ref "IC21") (pin "27") (pinfunction "2D7_27") (pintype "input"))
      (node (ref "IC25") (pin "4") (pinfunction "I0_4") (pintype "input"))
    )
    (net (code "146") (name "Net-(IC21A-2D8)") (class "Default")
      (node (ref "IC21") (pin "22") (pinfunction "2Q7_22") (pintype "tri_state"))
      (node (ref "IC21") (pin "26") (pinfunction "2D8_26") (pintype "input"))
      (node (ref "IC25") (pin "9") (pinfunction "I0_9") (pintype "input"))
    )
    (net (code "147") (name "Net-(IC21A-2Q8)") (class "Default")
      (node (ref "IC21") (pin "23") (pinfunction "2Q8_23") (pintype "tri_state"))
      (node (ref "IC25") (pin "12") (pinfunction "I0_12") (pintype "input"))
      (node (ref "IC26") (pin "47") (pinfunction "1D1_47") (pintype "input"))
    )
    (net (code "148") (name "Net-(IC22A-O)") (class "Default")
      (node (ref "IC22") (pin "3") (pinfunction "O_3") (pintype "output"))
      (node (ref "U$9") (pin "1") (pinfunction "I1_1") (pintype "input"))
    )
    (net (code "149") (name "Net-(IC22B-O)") (class "Default")
      (node (ref "IC22") (pin "6") (pinfunction "O_6") (pintype "output"))
      (node (ref "U$9") (pin "2") (pinfunction "I2_2") (pintype "input"))
    )
    (net (code "150") (name "Net-(IC22C-O)") (class "Default")
      (node (ref "IC22") (pin "8") (pinfunction "O_8") (pintype "output"))
      (node (ref "U$9") (pin "3") (pinfunction "I3_3") (pintype "input"))
    )
    (net (code "151") (name "Net-(IC22D-O)") (class "Default")
      (node (ref "IC22") (pin "11") (pinfunction "O_11") (pintype "output"))
      (node (ref "U$9") (pin "4") (pinfunction "I4_4") (pintype "input"))
    )
    (net (code "152") (name "Net-(IC23A-O)") (class "Default")
      (node (ref "IC23") (pin "3") (pinfunction "O_3") (pintype "output"))
      (node (ref "U$9") (pin "5") (pinfunction "I5_5") (pintype "input"))
    )
    (net (code "153") (name "Net-(IC23B-O)") (class "Default")
      (node (ref "IC23") (pin "6") (pinfunction "O_6") (pintype "output"))
      (node (ref "U$9") (pin "6") (pinfunction "I6_6") (pintype "input"))
    )
    (net (code "154") (name "Net-(IC23C-O)") (class "Default")
      (node (ref "IC23") (pin "8") (pinfunction "O_8") (pintype "output"))
      (node (ref "U$9") (pin "7") (pinfunction "I7_7") (pintype "input"))
    )
    (net (code "155") (name "Net-(IC23D-O)") (class "Default")
      (node (ref "IC23") (pin "11") (pinfunction "O_11") (pintype "output"))
      (node (ref "U$9") (pin "8") (pinfunction "I8_8") (pintype "input"))
    )
    (net (code "156") (name "Net-(IC24A-O)") (class "Default")
      (node (ref "IC24") (pin "3") (pinfunction "O_3") (pintype "output"))
      (node (ref "U$10") (pin "1") (pinfunction "I1_1") (pintype "input"))
    )
    (net (code "157") (name "Net-(IC24B-O)") (class "Default")
      (node (ref "IC24") (pin "6") (pinfunction "O_6") (pintype "output"))
      (node (ref "U$10") (pin "2") (pinfunction "I2_2") (pintype "input"))
    )
    (net (code "158") (name "Net-(IC24C-O)") (class "Default")
      (node (ref "IC24") (pin "8") (pinfunction "O_8") (pintype "output"))
      (node (ref "U$10") (pin "3") (pinfunction "I3_3") (pintype "input"))
    )
    (net (code "159") (name "Net-(IC24D-O)") (class "Default")
      (node (ref "IC24") (pin "11") (pinfunction "O_11") (pintype "output"))
      (node (ref "U$10") (pin "4") (pinfunction "I4_4") (pintype "input"))
    )
    (net (code "160") (name "Net-(IC25A-O)") (class "Default")
      (node (ref "IC25") (pin "3") (pinfunction "O_3") (pintype "output"))
      (node (ref "U$10") (pin "5") (pinfunction "I5_5") (pintype "input"))
    )
    (net (code "161") (name "Net-(IC25B-O)") (class "Default")
      (node (ref "IC25") (pin "6") (pinfunction "O_6") (pintype "output"))
      (node (ref "U$10") (pin "6") (pinfunction "I6_6") (pintype "input"))
    )
    (net (code "162") (name "Net-(IC25C-O)") (class "Default")
      (node (ref "IC25") (pin "8") (pinfunction "O_8") (pintype "output"))
      (node (ref "U$10") (pin "7") (pinfunction "I7_7") (pintype "input"))
    )
    (net (code "163") (name "Net-(IC25D-O)") (class "Default")
      (node (ref "IC25") (pin "11") (pinfunction "O_11") (pintype "output"))
      (node (ref "U$10") (pin "8") (pinfunction "I8_8") (pintype "input"))
    )
    (net (code "164") (name "Net-(IC26A-1D2)") (class "Default")
      (node (ref "IC26") (pin "2") (pinfunction "1Q1_2") (pintype "tri_state"))
      (node (ref "IC26") (pin "46") (pinfunction "1D2_46") (pintype "input"))
      (node (ref "IC27") (pin "1") (pinfunction "I0_1") (pintype "input"))
    )
    (net (code "165") (name "Net-(IC26A-1D3)") (class "Default")
      (node (ref "IC26") (pin "3") (pinfunction "1Q2_3") (pintype "tri_state"))
      (node (ref "IC26") (pin "44") (pinfunction "1D3_44") (pintype "input"))
      (node (ref "IC27") (pin "4") (pinfunction "I0_4") (pintype "input"))
    )
    (net (code "166") (name "Net-(IC26A-1D4)") (class "Default")
      (node (ref "IC26") (pin "43") (pinfunction "1D4_43") (pintype "input"))
      (node (ref "IC26") (pin "5") (pinfunction "1Q3_5") (pintype "tri_state"))
      (node (ref "IC27") (pin "9") (pinfunction "I0_9") (pintype "input"))
    )
    (net (code "167") (name "Net-(IC26A-1D5)") (class "Default")
      (node (ref "IC26") (pin "41") (pinfunction "1D5_41") (pintype "input"))
      (node (ref "IC26") (pin "6") (pinfunction "1Q4_6") (pintype "tri_state"))
      (node (ref "IC27") (pin "12") (pinfunction "I0_12") (pintype "input"))
    )
    (net (code "168") (name "Net-(IC26A-1D6)") (class "Default")
      (node (ref "IC26") (pin "40") (pinfunction "1D6_40") (pintype "input"))
      (node (ref "IC26") (pin "8") (pinfunction "1Q5_8") (pintype "tri_state"))
      (node (ref "IC28") (pin "1") (pinfunction "I0_1") (pintype "input"))
    )
    (net (code "169") (name "Net-(IC26A-1D7)") (class "Default")
      (node (ref "IC26") (pin "38") (pinfunction "1D7_38") (pintype "input"))
      (node (ref "IC26") (pin "9") (pinfunction "1Q6_9") (pintype "tri_state"))
      (node (ref "IC28") (pin "4") (pinfunction "I0_4") (pintype "input"))
    )
    (net (code "170") (name "Net-(IC26A-1D8)") (class "Default")
      (node (ref "IC26") (pin "11") (pinfunction "1Q7_11") (pintype "tri_state"))
      (node (ref "IC26") (pin "37") (pinfunction "1D8_37") (pintype "input"))
      (node (ref "IC28") (pin "9") (pinfunction "I0_9") (pintype "input"))
    )
    (net (code "171") (name "Net-(IC26A-1Q8)") (class "Default")
      (node (ref "IC26") (pin "12") (pinfunction "1Q8_12") (pintype "tri_state"))
      (node (ref "IC26") (pin "36") (pinfunction "2D1_36") (pintype "input"))
      (node (ref "IC28") (pin "12") (pinfunction "I0_12") (pintype "input"))
    )
    (net (code "172") (name "Net-(IC26A-2D2)") (class "Default")
      (node (ref "IC26") (pin "13") (pinfunction "2Q1_13") (pintype "tri_state"))
      (node (ref "IC26") (pin "35") (pinfunction "2D2_35") (pintype "input"))
      (node (ref "IC29") (pin "1") (pinfunction "I0_1") (pintype "input"))
    )
    (net (code "173") (name "Net-(IC26A-2D3)") (class "Default")
      (node (ref "IC26") (pin "14") (pinfunction "2Q2_14") (pintype "tri_state"))
      (node (ref "IC26") (pin "33") (pinfunction "2D3_33") (pintype "input"))
      (node (ref "IC29") (pin "4") (pinfunction "I0_4") (pintype "input"))
    )
    (net (code "174") (name "Net-(IC26A-2D4)") (class "Default")
      (node (ref "IC26") (pin "16") (pinfunction "2Q3_16") (pintype "tri_state"))
      (node (ref "IC26") (pin "32") (pinfunction "2D4_32") (pintype "input"))
      (node (ref "IC29") (pin "9") (pinfunction "I0_9") (pintype "input"))
    )
    (net (code "175") (name "Net-(IC26A-2D5)") (class "Default")
      (node (ref "IC26") (pin "17") (pinfunction "2Q4_17") (pintype "tri_state"))
      (node (ref "IC26") (pin "30") (pinfunction "2D5_30") (pintype "input"))
      (node (ref "IC29") (pin "12") (pinfunction "I0_12") (pintype "input"))
    )
    (net (code "176") (name "Net-(IC26A-2D6)") (class "Default")
      (node (ref "IC26") (pin "19") (pinfunction "2Q5_19") (pintype "tri_state"))
      (node (ref "IC26") (pin "29") (pinfunction "2D6_29") (pintype "input"))
      (node (ref "IC30") (pin "1") (pinfunction "I0_1") (pintype "input"))
    )
    (net (code "177") (name "Net-(IC26A-2D7)") (class "Default")
      (node (ref "IC26") (pin "20") (pinfunction "2Q6_20") (pintype "tri_state"))
      (node (ref "IC26") (pin "27") (pinfunction "2D7_27") (pintype "input"))
      (node (ref "IC30") (pin "4") (pinfunction "I0_4") (pintype "input"))
    )
    (net (code "178") (name "Net-(IC26A-2D8)") (class "Default")
      (node (ref "IC26") (pin "22") (pinfunction "2Q7_22") (pintype "tri_state"))
      (node (ref "IC26") (pin "26") (pinfunction "2D8_26") (pintype "input"))
      (node (ref "IC30") (pin "9") (pinfunction "I0_9") (pintype "input"))
    )
    (net (code "179") (name "Net-(IC26A-2Q8)") (class "Default")
      (node (ref "IC26") (pin "23") (pinfunction "2Q8_23") (pintype "tri_state"))
      (node (ref "IC3") (pin "47") (pinfunction "1D1_47") (pintype "input"))
      (node (ref "IC30") (pin "12") (pinfunction "I0_12") (pintype "input"))
    )
    (net (code "180") (name "Net-(IC27A-O)") (class "Default")
      (node (ref "IC27") (pin "3") (pinfunction "O_3") (pintype "output"))
      (node (ref "U$11") (pin "1") (pinfunction "I1_1") (pintype "input"))
    )
    (net (code "181") (name "Net-(IC27B-O)") (class "Default")
      (node (ref "IC27") (pin "6") (pinfunction "O_6") (pintype "output"))
      (node (ref "U$11") (pin "2") (pinfunction "I2_2") (pintype "input"))
    )
    (net (code "182") (name "Net-(IC27C-O)") (class "Default")
      (node (ref "IC27") (pin "8") (pinfunction "O_8") (pintype "output"))
      (node (ref "U$11") (pin "3") (pinfunction "I3_3") (pintype "input"))
    )
    (net (code "183") (name "Net-(IC27D-O)") (class "Default")
      (node (ref "IC27") (pin "11") (pinfunction "O_11") (pintype "output"))
      (node (ref "U$11") (pin "4") (pinfunction "I4_4") (pintype "input"))
    )
    (net (code "184") (name "Net-(IC28A-O)") (class "Default")
      (node (ref "IC28") (pin "3") (pinfunction "O_3") (pintype "output"))
      (node (ref "U$11") (pin "5") (pinfunction "I5_5") (pintype "input"))
    )
    (net (code "185") (name "Net-(IC28B-O)") (class "Default")
      (node (ref "IC28") (pin "6") (pinfunction "O_6") (pintype "output"))
      (node (ref "U$11") (pin "6") (pinfunction "I6_6") (pintype "input"))
    )
    (net (code "186") (name "Net-(IC28C-O)") (class "Default")
      (node (ref "IC28") (pin "8") (pinfunction "O_8") (pintype "output"))
      (node (ref "U$11") (pin "7") (pinfunction "I7_7") (pintype "input"))
    )
    (net (code "187") (name "Net-(IC28D-O)") (class "Default")
      (node (ref "IC28") (pin "11") (pinfunction "O_11") (pintype "output"))
      (node (ref "U$11") (pin "8") (pinfunction "I8_8") (pintype "input"))
    )
    (net (code "188") (name "Net-(IC29A-O)") (class "Default")
      (node (ref "IC29") (pin "3") (pinfunction "O_3") (pintype "output"))
      (node (ref "U$12") (pin "1") (pinfunction "I1_1") (pintype "input"))
    )
    (net (code "189") (name "Net-(IC29B-O)") (class "Default")
      (node (ref "IC29") (pin "6") (pinfunction "O_6") (pintype "output"))
      (node (ref "U$12") (pin "2") (pinfunction "I2_2") (pintype "input"))
    )
    (net (code "190") (name "Net-(IC29C-O)") (class "Default")
      (node (ref "IC29") (pin "8") (pinfunction "O_8") (pintype "output"))
      (node (ref "U$12") (pin "3") (pinfunction "I3_3") (pintype "input"))
    )
    (net (code "191") (name "Net-(IC29D-O)") (class "Default")
      (node (ref "IC29") (pin "11") (pinfunction "O_11") (pintype "output"))
      (node (ref "U$12") (pin "4") (pinfunction "I4_4") (pintype "input"))
    )
    (net (code "192") (name "Net-(IC30A-O)") (class "Default")
      (node (ref "IC30") (pin "3") (pinfunction "O_3") (pintype "output"))
      (node (ref "U$12") (pin "5") (pinfunction "I5_5") (pintype "input"))
    )
    (net (code "193") (name "Net-(IC30B-O)") (class "Default")
      (node (ref "IC30") (pin "6") (pinfunction "O_6") (pintype "output"))
      (node (ref "U$12") (pin "6") (pinfunction "I6_6") (pintype "input"))
    )
    (net (code "194") (name "Net-(IC30C-O)") (class "Default")
      (node (ref "IC30") (pin "8") (pinfunction "O_8") (pintype "output"))
      (node (ref "U$12") (pin "7") (pinfunction "I7_7") (pintype "input"))
    )
    (net (code "195") (name "Net-(IC30D-O)") (class "Default")
      (node (ref "IC30") (pin "11") (pinfunction "O_11") (pintype "output"))
      (node (ref "U$12") (pin "8") (pinfunction "I8_8") (pintype "input"))
    )
    (net (code "196") (name "Net-(IC41A-1D1)") (class "Default")
      (node (ref "IC41") (pin "47") (pinfunction "1D1_47") (pintype "input"))
      (node (ref "IC56") (pin "23") (pinfunction "2Q8_23") (pintype "tri_state"))
      (node (ref "IC60") (pin "12") (pinfunction "I0_12") (pintype "input"))
    )
    (net (code "197") (name "Net-(IC41A-1D2)") (class "Default")
      (node (ref "IC41") (pin "2") (pinfunction "1Q1_2") (pintype "tri_state"))
      (node (ref "IC41") (pin "46") (pinfunction "1D2_46") (pintype "input"))
      (node (ref "IC42") (pin "1") (pinfunction "I0_1") (pintype "input"))
    )
    (net (code "198") (name "Net-(IC41A-1D3)") (class "Default")
      (node (ref "IC41") (pin "3") (pinfunction "1Q2_3") (pintype "tri_state"))
      (node (ref "IC41") (pin "44") (pinfunction "1D3_44") (pintype "input"))
      (node (ref "IC42") (pin "4") (pinfunction "I0_4") (pintype "input"))
    )
    (net (code "199") (name "Net-(IC41A-1D4)") (class "Default")
      (node (ref "IC41") (pin "43") (pinfunction "1D4_43") (pintype "input"))
      (node (ref "IC41") (pin "5") (pinfunction "1Q3_5") (pintype "tri_state"))
      (node (ref "IC42") (pin "9") (pinfunction "I0_9") (pintype "input"))
    )
    (net (code "200") (name "Net-(IC41A-1D5)") (class "Default")
      (node (ref "IC41") (pin "41") (pinfunction "1D5_41") (pintype "input"))
      (node (ref "IC41") (pin "6") (pinfunction "1Q4_6") (pintype "tri_state"))
      (node (ref "IC42") (pin "12") (pinfunction "I0_12") (pintype "input"))
    )
    (net (code "201") (name "Net-(IC41A-1D6)") (class "Default")
      (node (ref "IC41") (pin "40") (pinfunction "1D6_40") (pintype "input"))
      (node (ref "IC41") (pin "8") (pinfunction "1Q5_8") (pintype "tri_state"))
      (node (ref "IC43") (pin "1") (pinfunction "I0_1") (pintype "input"))
    )
    (net (code "202") (name "Net-(IC41A-1D7)") (class "Default")
      (node (ref "IC41") (pin "38") (pinfunction "1D7_38") (pintype "input"))
      (node (ref "IC41") (pin "9") (pinfunction "1Q6_9") (pintype "tri_state"))
      (node (ref "IC43") (pin "4") (pinfunction "I0_4") (pintype "input"))
    )
    (net (code "203") (name "Net-(IC41A-1D8)") (class "Default")
      (node (ref "IC41") (pin "11") (pinfunction "1Q7_11") (pintype "tri_state"))
      (node (ref "IC41") (pin "37") (pinfunction "1D8_37") (pintype "input"))
      (node (ref "IC43") (pin "9") (pinfunction "I0_9") (pintype "input"))
    )
    (net (code "204") (name "Net-(IC41A-1Q8)") (class "Default")
      (node (ref "IC41") (pin "12") (pinfunction "1Q8_12") (pintype "tri_state"))
      (node (ref "IC41") (pin "36") (pinfunction "2D1_36") (pintype "input"))
      (node (ref "IC43") (pin "12") (pinfunction "I0_12") (pintype "input"))
    )
    (net (code "205") (name "Net-(IC41A-2D2)") (class "Default")
      (node (ref "IC41") (pin "13") (pinfunction "2Q1_13") (pintype "tri_state"))
      (node (ref "IC41") (pin "35") (pinfunction "2D2_35") (pintype "input"))
      (node (ref "IC44") (pin "1") (pinfunction "I0_1") (pintype "input"))
    )
    (net (code "206") (name "Net-(IC41A-2D3)") (class "Default")
      (node (ref "IC41") (pin "14") (pinfunction "2Q2_14") (pintype "tri_state"))
      (node (ref "IC41") (pin "33") (pinfunction "2D3_33") (pintype "input"))
      (node (ref "IC44") (pin "4") (pinfunction "I0_4") (pintype "input"))
    )
    (net (code "207") (name "Net-(IC41A-2D4)") (class "Default")
      (node (ref "IC41") (pin "16") (pinfunction "2Q3_16") (pintype "tri_state"))
      (node (ref "IC41") (pin "32") (pinfunction "2D4_32") (pintype "input"))
      (node (ref "IC44") (pin "9") (pinfunction "I0_9") (pintype "input"))
    )
    (net (code "208") (name "Net-(IC41A-2D5)") (class "Default")
      (node (ref "IC41") (pin "17") (pinfunction "2Q4_17") (pintype "tri_state"))
      (node (ref "IC41") (pin "30") (pinfunction "2D5_30") (pintype "input"))
      (node (ref "IC44") (pin "12") (pinfunction "I0_12") (pintype "input"))
    )
    (net (code "209") (name "Net-(IC41A-2D6)") (class "Default")
      (node (ref "IC41") (pin "19") (pinfunction "2Q5_19") (pintype "tri_state"))
      (node (ref "IC41") (pin "29") (pinfunction "2D6_29") (pintype "input"))
      (node (ref "IC45") (pin "1") (pinfunction "I0_1") (pintype "input"))
    )
    (net (code "210") (name "Net-(IC41A-2D7)") (class "Default")
      (node (ref "IC41") (pin "20") (pinfunction "2Q6_20") (pintype "tri_state"))
      (node (ref "IC41") (pin "27") (pinfunction "2D7_27") (pintype "input"))
      (node (ref "IC45") (pin "4") (pinfunction "I0_4") (pintype "input"))
    )
    (net (code "211") (name "Net-(IC41A-2D8)") (class "Default")
      (node (ref "IC41") (pin "22") (pinfunction "2Q7_22") (pintype "tri_state"))
      (node (ref "IC41") (pin "26") (pinfunction "2D8_26") (pintype "input"))
      (node (ref "IC45") (pin "9") (pinfunction "I0_9") (pintype "input"))
    )
    (net (code "212") (name "Net-(IC41A-2Q8)") (class "Default")
      (node (ref "IC41") (pin "23") (pinfunction "2Q8_23") (pintype "tri_state"))
      (node (ref "IC45") (pin "12") (pinfunction "I0_12") (pintype "input"))
      (node (ref "IC46") (pin "47") (pinfunction "1D1_47") (pintype "input"))
    )
    (net (code "213") (name "Net-(IC42A-O)") (class "Default")
      (node (ref "IC42") (pin "3") (pinfunction "O_3") (pintype "output"))
      (node (ref "U$17") (pin "1") (pinfunction "I1_1") (pintype "input"))
    )
    (net (code "214") (name "Net-(IC42B-O)") (class "Default")
      (node (ref "IC42") (pin "6") (pinfunction "O_6") (pintype "output"))
      (node (ref "U$17") (pin "2") (pinfunction "I2_2") (pintype "input"))
    )
    (net (code "215") (name "Net-(IC42C-O)") (class "Default")
      (node (ref "IC42") (pin "8") (pinfunction "O_8") (pintype "output"))
      (node (ref "U$17") (pin "3") (pinfunction "I3_3") (pintype "input"))
    )
    (net (code "216") (name "Net-(IC42D-O)") (class "Default")
      (node (ref "IC42") (pin "11") (pinfunction "O_11") (pintype "output"))
      (node (ref "U$17") (pin "4") (pinfunction "I4_4") (pintype "input"))
    )
    (net (code "217") (name "Net-(IC43A-O)") (class "Default")
      (node (ref "IC43") (pin "3") (pinfunction "O_3") (pintype "output"))
      (node (ref "U$17") (pin "5") (pinfunction "I5_5") (pintype "input"))
    )
    (net (code "218") (name "Net-(IC43B-O)") (class "Default")
      (node (ref "IC43") (pin "6") (pinfunction "O_6") (pintype "output"))
      (node (ref "U$17") (pin "6") (pinfunction "I6_6") (pintype "input"))
    )
    (net (code "219") (name "Net-(IC43C-O)") (class "Default")
      (node (ref "IC43") (pin "8") (pinfunction "O_8") (pintype "output"))
      (node (ref "U$17") (pin "7") (pinfunction "I7_7") (pintype "input"))
    )
    (net (code "220") (name "Net-(IC43D-O)") (class "Default")
      (node (ref "IC43") (pin "11") (pinfunction "O_11") (pintype "output"))
      (node (ref "U$17") (pin "8") (pinfunction "I8_8") (pintype "input"))
    )
    (net (code "221") (name "Net-(IC44A-O)") (class "Default")
      (node (ref "IC44") (pin "3") (pinfunction "O_3") (pintype "output"))
      (node (ref "U$18") (pin "1") (pinfunction "I1_1") (pintype "input"))
    )
    (net (code "222") (name "Net-(IC44B-O)") (class "Default")
      (node (ref "IC44") (pin "6") (pinfunction "O_6") (pintype "output"))
      (node (ref "U$18") (pin "2") (pinfunction "I2_2") (pintype "input"))
    )
    (net (code "223") (name "Net-(IC44C-O)") (class "Default")
      (node (ref "IC44") (pin "8") (pinfunction "O_8") (pintype "output"))
      (node (ref "U$18") (pin "3") (pinfunction "I3_3") (pintype "input"))
    )
    (net (code "224") (name "Net-(IC44D-O)") (class "Default")
      (node (ref "IC44") (pin "11") (pinfunction "O_11") (pintype "output"))
      (node (ref "U$18") (pin "4") (pinfunction "I4_4") (pintype "input"))
    )
    (net (code "225") (name "Net-(IC45A-O)") (class "Default")
      (node (ref "IC45") (pin "3") (pinfunction "O_3") (pintype "output"))
      (node (ref "U$18") (pin "5") (pinfunction "I5_5") (pintype "input"))
    )
    (net (code "226") (name "Net-(IC45B-O)") (class "Default")
      (node (ref "IC45") (pin "6") (pinfunction "O_6") (pintype "output"))
      (node (ref "U$18") (pin "6") (pinfunction "I6_6") (pintype "input"))
    )
    (net (code "227") (name "Net-(IC45C-O)") (class "Default")
      (node (ref "IC45") (pin "8") (pinfunction "O_8") (pintype "output"))
      (node (ref "U$18") (pin "7") (pinfunction "I7_7") (pintype "input"))
    )
    (net (code "228") (name "Net-(IC45D-O)") (class "Default")
      (node (ref "IC45") (pin "11") (pinfunction "O_11") (pintype "output"))
      (node (ref "U$18") (pin "8") (pinfunction "I8_8") (pintype "input"))
    )
    (net (code "229") (name "Net-(IC46A-1D2)") (class "Default")
      (node (ref "IC46") (pin "2") (pinfunction "1Q1_2") (pintype "tri_state"))
      (node (ref "IC46") (pin "46") (pinfunction "1D2_46") (pintype "input"))
      (node (ref "IC47") (pin "1") (pinfunction "I0_1") (pintype "input"))
    )
    (net (code "230") (name "Net-(IC46A-1D3)") (class "Default")
      (node (ref "IC46") (pin "3") (pinfunction "1Q2_3") (pintype "tri_state"))
      (node (ref "IC46") (pin "44") (pinfunction "1D3_44") (pintype "input"))
      (node (ref "IC47") (pin "4") (pinfunction "I0_4") (pintype "input"))
    )
    (net (code "231") (name "Net-(IC46A-1D4)") (class "Default")
      (node (ref "IC46") (pin "43") (pinfunction "1D4_43") (pintype "input"))
      (node (ref "IC46") (pin "5") (pinfunction "1Q3_5") (pintype "tri_state"))
      (node (ref "IC47") (pin "9") (pinfunction "I0_9") (pintype "input"))
    )
    (net (code "232") (name "Net-(IC46A-1D5)") (class "Default")
      (node (ref "IC46") (pin "41") (pinfunction "1D5_41") (pintype "input"))
      (node (ref "IC46") (pin "6") (pinfunction "1Q4_6") (pintype "tri_state"))
      (node (ref "IC47") (pin "12") (pinfunction "I0_12") (pintype "input"))
    )
    (net (code "233") (name "Net-(IC46A-1D6)") (class "Default")
      (node (ref "IC46") (pin "40") (pinfunction "1D6_40") (pintype "input"))
      (node (ref "IC46") (pin "8") (pinfunction "1Q5_8") (pintype "tri_state"))
      (node (ref "IC48") (pin "1") (pinfunction "I0_1") (pintype "input"))
    )
    (net (code "234") (name "Net-(IC46A-1D7)") (class "Default")
      (node (ref "IC46") (pin "38") (pinfunction "1D7_38") (pintype "input"))
      (node (ref "IC46") (pin "9") (pinfunction "1Q6_9") (pintype "tri_state"))
      (node (ref "IC48") (pin "4") (pinfunction "I0_4") (pintype "input"))
    )
    (net (code "235") (name "Net-(IC46A-1D8)") (class "Default")
      (node (ref "IC46") (pin "11") (pinfunction "1Q7_11") (pintype "tri_state"))
      (node (ref "IC46") (pin "37") (pinfunction "1D8_37") (pintype "input"))
      (node (ref "IC48") (pin "9") (pinfunction "I0_9") (pintype "input"))
    )
    (net (code "236") (name "Net-(IC46A-1Q8)") (class "Default")
      (node (ref "IC46") (pin "12") (pinfunction "1Q8_12") (pintype "tri_state"))
      (node (ref "IC46") (pin "36") (pinfunction "2D1_36") (pintype "input"))
      (node (ref "IC48") (pin "12") (pinfunction "I0_12") (pintype "input"))
    )
    (net (code "237") (name "Net-(IC46A-2D2)") (class "Default")
      (node (ref "IC46") (pin "13") (pinfunction "2Q1_13") (pintype "tri_state"))
      (node (ref "IC46") (pin "35") (pinfunction "2D2_35") (pintype "input"))
      (node (ref "IC49") (pin "1") (pinfunction "I0_1") (pintype "input"))
    )
    (net (code "238") (name "Net-(IC46A-2D3)") (class "Default")
      (node (ref "IC46") (pin "14") (pinfunction "2Q2_14") (pintype "tri_state"))
      (node (ref "IC46") (pin "33") (pinfunction "2D3_33") (pintype "input"))
      (node (ref "IC49") (pin "4") (pinfunction "I0_4") (pintype "input"))
    )
    (net (code "239") (name "Net-(IC46A-2D4)") (class "Default")
      (node (ref "IC46") (pin "16") (pinfunction "2Q3_16") (pintype "tri_state"))
      (node (ref "IC46") (pin "32") (pinfunction "2D4_32") (pintype "input"))
      (node (ref "IC49") (pin "9") (pinfunction "I0_9") (pintype "input"))
    )
    (net (code "240") (name "Net-(IC46A-2D5)") (class "Default")
      (node (ref "IC46") (pin "17") (pinfunction "2Q4_17") (pintype "tri_state"))
      (node (ref "IC46") (pin "30") (pinfunction "2D5_30") (pintype "input"))
      (node (ref "IC49") (pin "12") (pinfunction "I0_12") (pintype "input"))
    )
    (net (code "241") (name "Net-(IC46A-2D6)") (class "Default")
      (node (ref "IC46") (pin "19") (pinfunction "2Q5_19") (pintype "tri_state"))
      (node (ref "IC46") (pin "29") (pinfunction "2D6_29") (pintype "input"))
      (node (ref "IC50") (pin "1") (pinfunction "I0_1") (pintype "input"))
    )
    (net (code "242") (name "Net-(IC46A-2D7)") (class "Default")
      (node (ref "IC46") (pin "20") (pinfunction "2Q6_20") (pintype "tri_state"))
      (node (ref "IC46") (pin "27") (pinfunction "2D7_27") (pintype "input"))
      (node (ref "IC50") (pin "4") (pinfunction "I0_4") (pintype "input"))
    )
    (net (code "243") (name "Net-(IC46A-2D8)") (class "Default")
      (node (ref "IC46") (pin "22") (pinfunction "2Q7_22") (pintype "tri_state"))
      (node (ref "IC46") (pin "26") (pinfunction "2D8_26") (pintype "input"))
      (node (ref "IC50") (pin "9") (pinfunction "I0_9") (pintype "input"))
    )
    (net (code "244") (name "Net-(IC46A-2Q8)") (class "Default")
      (node (ref "IC46") (pin "23") (pinfunction "2Q8_23") (pintype "tri_state"))
      (node (ref "IC50") (pin "12") (pinfunction "I0_12") (pintype "input"))
      (node (ref "X11") (pin "2") (pinfunction "S_2") (pintype "passive"))
    )
    (net (code "245") (name "Net-(IC47A-O)") (class "Default")
      (node (ref "IC47") (pin "3") (pinfunction "O_3") (pintype "output"))
      (node (ref "U$19") (pin "1") (pinfunction "I1_1") (pintype "input"))
    )
    (net (code "246") (name "Net-(IC47B-O)") (class "Default")
      (node (ref "IC47") (pin "6") (pinfunction "O_6") (pintype "output"))
      (node (ref "U$19") (pin "2") (pinfunction "I2_2") (pintype "input"))
    )
    (net (code "247") (name "Net-(IC47C-O)") (class "Default")
      (node (ref "IC47") (pin "8") (pinfunction "O_8") (pintype "output"))
      (node (ref "U$19") (pin "3") (pinfunction "I3_3") (pintype "input"))
    )
    (net (code "248") (name "Net-(IC47D-O)") (class "Default")
      (node (ref "IC47") (pin "11") (pinfunction "O_11") (pintype "output"))
      (node (ref "U$19") (pin "4") (pinfunction "I4_4") (pintype "input"))
    )
    (net (code "249") (name "Net-(IC48A-O)") (class "Default")
      (node (ref "IC48") (pin "3") (pinfunction "O_3") (pintype "output"))
      (node (ref "U$19") (pin "5") (pinfunction "I5_5") (pintype "input"))
    )
    (net (code "250") (name "Net-(IC48B-O)") (class "Default")
      (node (ref "IC48") (pin "6") (pinfunction "O_6") (pintype "output"))
      (node (ref "U$19") (pin "6") (pinfunction "I6_6") (pintype "input"))
    )
    (net (code "251") (name "Net-(IC48C-O)") (class "Default")
      (node (ref "IC48") (pin "8") (pinfunction "O_8") (pintype "output"))
      (node (ref "U$19") (pin "7") (pinfunction "I7_7") (pintype "input"))
    )
    (net (code "252") (name "Net-(IC48D-O)") (class "Default")
      (node (ref "IC48") (pin "11") (pinfunction "O_11") (pintype "output"))
      (node (ref "U$19") (pin "8") (pinfunction "I8_8") (pintype "input"))
    )
    (net (code "253") (name "Net-(IC49A-O)") (class "Default")
      (node (ref "IC49") (pin "3") (pinfunction "O_3") (pintype "output"))
      (node (ref "U$20") (pin "1") (pinfunction "I1_1") (pintype "input"))
    )
    (net (code "254") (name "Net-(IC49B-O)") (class "Default")
      (node (ref "IC49") (pin "6") (pinfunction "O_6") (pintype "output"))
      (node (ref "U$20") (pin "2") (pinfunction "I2_2") (pintype "input"))
    )
    (net (code "255") (name "Net-(IC49C-O)") (class "Default")
      (node (ref "IC49") (pin "8") (pinfunction "O_8") (pintype "output"))
      (node (ref "U$20") (pin "3") (pinfunction "I3_3") (pintype "input"))
    )
    (net (code "256") (name "Net-(IC49D-O)") (class "Default")
      (node (ref "IC49") (pin "11") (pinfunction "O_11") (pintype "output"))
      (node (ref "U$20") (pin "4") (pinfunction "I4_4") (pintype "input"))
    )
    (net (code "257") (name "Net-(IC50A-O)") (class "Default")
      (node (ref "IC50") (pin "3") (pinfunction "O_3") (pintype "output"))
      (node (ref "U$20") (pin "5") (pinfunction "I5_5") (pintype "input"))
    )
    (net (code "258") (name "Net-(IC50B-O)") (class "Default")
      (node (ref "IC50") (pin "6") (pinfunction "O_6") (pintype "output"))
      (node (ref "U$20") (pin "6") (pinfunction "I6_6") (pintype "input"))
    )
    (net (code "259") (name "Net-(IC50C-O)") (class "Default")
      (node (ref "IC50") (pin "8") (pinfunction "O_8") (pintype "output"))
      (node (ref "U$20") (pin "7") (pinfunction "I7_7") (pintype "input"))
    )
    (net (code "260") (name "Net-(IC50D-O)") (class "Default")
      (node (ref "IC50") (pin "11") (pinfunction "O_11") (pintype "output"))
      (node (ref "U$20") (pin "8") (pinfunction "I8_8") (pintype "input"))
    )
    (net (code "261") (name "Net-(IC51A-1D2)") (class "Default")
      (node (ref "IC51") (pin "2") (pinfunction "1Q1_2") (pintype "tri_state"))
      (node (ref "IC51") (pin "46") (pinfunction "1D2_46") (pintype "input"))
      (node (ref "IC52") (pin "1") (pinfunction "I0_1") (pintype "input"))
    )
    (net (code "262") (name "Net-(IC51A-1D3)") (class "Default")
      (node (ref "IC51") (pin "3") (pinfunction "1Q2_3") (pintype "tri_state"))
      (node (ref "IC51") (pin "44") (pinfunction "1D3_44") (pintype "input"))
      (node (ref "IC52") (pin "4") (pinfunction "I0_4") (pintype "input"))
    )
    (net (code "263") (name "Net-(IC51A-1D4)") (class "Default")
      (node (ref "IC51") (pin "43") (pinfunction "1D4_43") (pintype "input"))
      (node (ref "IC51") (pin "5") (pinfunction "1Q3_5") (pintype "tri_state"))
      (node (ref "IC52") (pin "9") (pinfunction "I0_9") (pintype "input"))
    )
    (net (code "264") (name "Net-(IC51A-1D5)") (class "Default")
      (node (ref "IC51") (pin "41") (pinfunction "1D5_41") (pintype "input"))
      (node (ref "IC51") (pin "6") (pinfunction "1Q4_6") (pintype "tri_state"))
      (node (ref "IC52") (pin "12") (pinfunction "I0_12") (pintype "input"))
    )
    (net (code "265") (name "Net-(IC51A-1D6)") (class "Default")
      (node (ref "IC51") (pin "40") (pinfunction "1D6_40") (pintype "input"))
      (node (ref "IC51") (pin "8") (pinfunction "1Q5_8") (pintype "tri_state"))
      (node (ref "IC53") (pin "1") (pinfunction "I0_1") (pintype "input"))
    )
    (net (code "266") (name "Net-(IC51A-1D7)") (class "Default")
      (node (ref "IC51") (pin "38") (pinfunction "1D7_38") (pintype "input"))
      (node (ref "IC51") (pin "9") (pinfunction "1Q6_9") (pintype "tri_state"))
      (node (ref "IC53") (pin "4") (pinfunction "I0_4") (pintype "input"))
    )
    (net (code "267") (name "Net-(IC51A-1D8)") (class "Default")
      (node (ref "IC51") (pin "11") (pinfunction "1Q7_11") (pintype "tri_state"))
      (node (ref "IC51") (pin "37") (pinfunction "1D8_37") (pintype "input"))
      (node (ref "IC53") (pin "9") (pinfunction "I0_9") (pintype "input"))
    )
    (net (code "268") (name "Net-(IC51A-1Q8)") (class "Default")
      (node (ref "IC51") (pin "12") (pinfunction "1Q8_12") (pintype "tri_state"))
      (node (ref "IC51") (pin "36") (pinfunction "2D1_36") (pintype "input"))
      (node (ref "IC53") (pin "12") (pinfunction "I0_12") (pintype "input"))
    )
    (net (code "269") (name "Net-(IC51A-2D2)") (class "Default")
      (node (ref "IC51") (pin "13") (pinfunction "2Q1_13") (pintype "tri_state"))
      (node (ref "IC51") (pin "35") (pinfunction "2D2_35") (pintype "input"))
      (node (ref "IC54") (pin "1") (pinfunction "I0_1") (pintype "input"))
    )
    (net (code "270") (name "Net-(IC51A-2D3)") (class "Default")
      (node (ref "IC51") (pin "14") (pinfunction "2Q2_14") (pintype "tri_state"))
      (node (ref "IC51") (pin "33") (pinfunction "2D3_33") (pintype "input"))
      (node (ref "IC54") (pin "4") (pinfunction "I0_4") (pintype "input"))
    )
    (net (code "271") (name "Net-(IC51A-2D4)") (class "Default")
      (node (ref "IC51") (pin "16") (pinfunction "2Q3_16") (pintype "tri_state"))
      (node (ref "IC51") (pin "32") (pinfunction "2D4_32") (pintype "input"))
      (node (ref "IC54") (pin "9") (pinfunction "I0_9") (pintype "input"))
    )
    (net (code "272") (name "Net-(IC51A-2D5)") (class "Default")
      (node (ref "IC51") (pin "17") (pinfunction "2Q4_17") (pintype "tri_state"))
      (node (ref "IC51") (pin "30") (pinfunction "2D5_30") (pintype "input"))
      (node (ref "IC54") (pin "12") (pinfunction "I0_12") (pintype "input"))
    )
    (net (code "273") (name "Net-(IC51A-2D6)") (class "Default")
      (node (ref "IC51") (pin "19") (pinfunction "2Q5_19") (pintype "tri_state"))
      (node (ref "IC51") (pin "29") (pinfunction "2D6_29") (pintype "input"))
      (node (ref "IC55") (pin "1") (pinfunction "I0_1") (pintype "input"))
    )
    (net (code "274") (name "Net-(IC51A-2D7)") (class "Default")
      (node (ref "IC51") (pin "20") (pinfunction "2Q6_20") (pintype "tri_state"))
      (node (ref "IC51") (pin "27") (pinfunction "2D7_27") (pintype "input"))
      (node (ref "IC55") (pin "4") (pinfunction "I0_4") (pintype "input"))
    )
    (net (code "275") (name "Net-(IC51A-2D8)") (class "Default")
      (node (ref "IC51") (pin "22") (pinfunction "2Q7_22") (pintype "tri_state"))
      (node (ref "IC51") (pin "26") (pinfunction "2D8_26") (pintype "input"))
      (node (ref "IC55") (pin "9") (pinfunction "I0_9") (pintype "input"))
    )
    (net (code "276") (name "Net-(IC51A-2Q8)") (class "Default")
      (node (ref "IC51") (pin "23") (pinfunction "2Q8_23") (pintype "tri_state"))
      (node (ref "IC55") (pin "12") (pinfunction "I0_12") (pintype "input"))
      (node (ref "IC56") (pin "47") (pinfunction "1D1_47") (pintype "input"))
    )
    (net (code "277") (name "Net-(IC52A-O)") (class "Default")
      (node (ref "IC52") (pin "3") (pinfunction "O_3") (pintype "output"))
      (node (ref "U$21") (pin "1") (pinfunction "I1_1") (pintype "input"))
    )
    (net (code "278") (name "Net-(IC52B-O)") (class "Default")
      (node (ref "IC52") (pin "6") (pinfunction "O_6") (pintype "output"))
      (node (ref "U$21") (pin "2") (pinfunction "I2_2") (pintype "input"))
    )
    (net (code "279") (name "Net-(IC52C-O)") (class "Default")
      (node (ref "IC52") (pin "8") (pinfunction "O_8") (pintype "output"))
      (node (ref "U$21") (pin "3") (pinfunction "I3_3") (pintype "input"))
    )
    (net (code "280") (name "Net-(IC52D-O)") (class "Default")
      (node (ref "IC52") (pin "11") (pinfunction "O_11") (pintype "output"))
      (node (ref "U$21") (pin "4") (pinfunction "I4_4") (pintype "input"))
    )
    (net (code "281") (name "Net-(IC53A-O)") (class "Default")
      (node (ref "IC53") (pin "3") (pinfunction "O_3") (pintype "output"))
      (node (ref "U$21") (pin "5") (pinfunction "I5_5") (pintype "input"))
    )
    (net (code "282") (name "Net-(IC53B-O)") (class "Default")
      (node (ref "IC53") (pin "6") (pinfunction "O_6") (pintype "output"))
      (node (ref "U$21") (pin "6") (pinfunction "I6_6") (pintype "input"))
    )
    (net (code "283") (name "Net-(IC53C-O)") (class "Default")
      (node (ref "IC53") (pin "8") (pinfunction "O_8") (pintype "output"))
      (node (ref "U$21") (pin "7") (pinfunction "I7_7") (pintype "input"))
    )
    (net (code "284") (name "Net-(IC53D-O)") (class "Default")
      (node (ref "IC53") (pin "11") (pinfunction "O_11") (pintype "output"))
      (node (ref "U$21") (pin "8") (pinfunction "I8_8") (pintype "input"))
    )
    (net (code "285") (name "Net-(IC54A-O)") (class "Default")
      (node (ref "IC54") (pin "3") (pinfunction "O_3") (pintype "output"))
      (node (ref "U$22") (pin "1") (pinfunction "I1_1") (pintype "input"))
    )
    (net (code "286") (name "Net-(IC54B-O)") (class "Default")
      (node (ref "IC54") (pin "6") (pinfunction "O_6") (pintype "output"))
      (node (ref "U$22") (pin "2") (pinfunction "I2_2") (pintype "input"))
    )
    (net (code "287") (name "Net-(IC54C-O)") (class "Default")
      (node (ref "IC54") (pin "8") (pinfunction "O_8") (pintype "output"))
      (node (ref "U$22") (pin "3") (pinfunction "I3_3") (pintype "input"))
    )
    (net (code "288") (name "Net-(IC54D-O)") (class "Default")
      (node (ref "IC54") (pin "11") (pinfunction "O_11") (pintype "output"))
      (node (ref "U$22") (pin "4") (pinfunction "I4_4") (pintype "input"))
    )
    (net (code "289") (name "Net-(IC55A-O)") (class "Default")
      (node (ref "IC55") (pin "3") (pinfunction "O_3") (pintype "output"))
      (node (ref "U$22") (pin "5") (pinfunction "I5_5") (pintype "input"))
    )
    (net (code "290") (name "Net-(IC55B-O)") (class "Default")
      (node (ref "IC55") (pin "6") (pinfunction "O_6") (pintype "output"))
      (node (ref "U$22") (pin "6") (pinfunction "I6_6") (pintype "input"))
    )
    (net (code "291") (name "Net-(IC55C-O)") (class "Default")
      (node (ref "IC55") (pin "8") (pinfunction "O_8") (pintype "output"))
      (node (ref "U$22") (pin "7") (pinfunction "I7_7") (pintype "input"))
    )
    (net (code "292") (name "Net-(IC55D-O)") (class "Default")
      (node (ref "IC55") (pin "11") (pinfunction "O_11") (pintype "output"))
      (node (ref "U$22") (pin "8") (pinfunction "I8_8") (pintype "input"))
    )
    (net (code "293") (name "Net-(IC56A-1D2)") (class "Default")
      (node (ref "IC56") (pin "2") (pinfunction "1Q1_2") (pintype "tri_state"))
      (node (ref "IC56") (pin "46") (pinfunction "1D2_46") (pintype "input"))
      (node (ref "IC57") (pin "1") (pinfunction "I0_1") (pintype "input"))
    )
    (net (code "294") (name "Net-(IC56A-1D3)") (class "Default")
      (node (ref "IC56") (pin "3") (pinfunction "1Q2_3") (pintype "tri_state"))
      (node (ref "IC56") (pin "44") (pinfunction "1D3_44") (pintype "input"))
      (node (ref "IC57") (pin "4") (pinfunction "I0_4") (pintype "input"))
    )
    (net (code "295") (name "Net-(IC56A-1D4)") (class "Default")
      (node (ref "IC56") (pin "43") (pinfunction "1D4_43") (pintype "input"))
      (node (ref "IC56") (pin "5") (pinfunction "1Q3_5") (pintype "tri_state"))
      (node (ref "IC57") (pin "9") (pinfunction "I0_9") (pintype "input"))
    )
    (net (code "296") (name "Net-(IC56A-1D5)") (class "Default")
      (node (ref "IC56") (pin "41") (pinfunction "1D5_41") (pintype "input"))
      (node (ref "IC56") (pin "6") (pinfunction "1Q4_6") (pintype "tri_state"))
      (node (ref "IC57") (pin "12") (pinfunction "I0_12") (pintype "input"))
    )
    (net (code "297") (name "Net-(IC56A-1D6)") (class "Default")
      (node (ref "IC56") (pin "40") (pinfunction "1D6_40") (pintype "input"))
      (node (ref "IC56") (pin "8") (pinfunction "1Q5_8") (pintype "tri_state"))
      (node (ref "IC58") (pin "1") (pinfunction "I0_1") (pintype "input"))
    )
    (net (code "298") (name "Net-(IC56A-1D7)") (class "Default")
      (node (ref "IC56") (pin "38") (pinfunction "1D7_38") (pintype "input"))
      (node (ref "IC56") (pin "9") (pinfunction "1Q6_9") (pintype "tri_state"))
      (node (ref "IC58") (pin "4") (pinfunction "I0_4") (pintype "input"))
    )
    (net (code "299") (name "Net-(IC56A-1D8)") (class "Default")
      (node (ref "IC56") (pin "11") (pinfunction "1Q7_11") (pintype "tri_state"))
      (node (ref "IC56") (pin "37") (pinfunction "1D8_37") (pintype "input"))
      (node (ref "IC58") (pin "9") (pinfunction "I0_9") (pintype "input"))
    )
    (net (code "300") (name "Net-(IC56A-1Q8)") (class "Default")
      (node (ref "IC56") (pin "12") (pinfunction "1Q8_12") (pintype "tri_state"))
      (node (ref "IC56") (pin "36") (pinfunction "2D1_36") (pintype "input"))
      (node (ref "IC58") (pin "12") (pinfunction "I0_12") (pintype "input"))
    )
    (net (code "301") (name "Net-(IC56A-2D2)") (class "Default")
      (node (ref "IC56") (pin "13") (pinfunction "2Q1_13") (pintype "tri_state"))
      (node (ref "IC56") (pin "35") (pinfunction "2D2_35") (pintype "input"))
      (node (ref "IC59") (pin "1") (pinfunction "I0_1") (pintype "input"))
    )
    (net (code "302") (name "Net-(IC56A-2D3)") (class "Default")
      (node (ref "IC56") (pin "14") (pinfunction "2Q2_14") (pintype "tri_state"))
      (node (ref "IC56") (pin "33") (pinfunction "2D3_33") (pintype "input"))
      (node (ref "IC59") (pin "4") (pinfunction "I0_4") (pintype "input"))
    )
    (net (code "303") (name "Net-(IC56A-2D4)") (class "Default")
      (node (ref "IC56") (pin "16") (pinfunction "2Q3_16") (pintype "tri_state"))
      (node (ref "IC56") (pin "32") (pinfunction "2D4_32") (pintype "input"))
      (node (ref "IC59") (pin "9") (pinfunction "I0_9") (pintype "input"))
    )
    (net (code "304") (name "Net-(IC56A-2D5)") (class "Default")
      (node (ref "IC56") (pin "17") (pinfunction "2Q4_17") (pintype "tri_state"))
      (node (ref "IC56") (pin "30") (pinfunction "2D5_30") (pintype "input"))
      (node (ref "IC59") (pin "12") (pinfunction "I0_12") (pintype "input"))
    )
    (net (code "305") (name "Net-(IC56A-2D6)") (class "Default")
      (node (ref "IC56") (pin "19") (pinfunction "2Q5_19") (pintype "tri_state"))
      (node (ref "IC56") (pin "29") (pinfunction "2D6_29") (pintype "input"))
      (node (ref "IC60") (pin "1") (pinfunction "I0_1") (pintype "input"))
    )
    (net (code "306") (name "Net-(IC56A-2D7)") (class "Default")
      (node (ref "IC56") (pin "20") (pinfunction "2Q6_20") (pintype "tri_state"))
      (node (ref "IC56") (pin "27") (pinfunction "2D7_27") (pintype "input"))
      (node (ref "IC60") (pin "4") (pinfunction "I0_4") (pintype "input"))
    )
    (net (code "307") (name "Net-(IC56A-2D8)") (class "Default")
      (node (ref "IC56") (pin "22") (pinfunction "2Q7_22") (pintype "tri_state"))
      (node (ref "IC56") (pin "26") (pinfunction "2D8_26") (pintype "input"))
      (node (ref "IC60") (pin "9") (pinfunction "I0_9") (pintype "input"))
    )
    (net (code "308") (name "Net-(IC57A-O)") (class "Default")
      (node (ref "IC57") (pin "3") (pinfunction "O_3") (pintype "output"))
      (node (ref "U$23") (pin "1") (pinfunction "I1_1") (pintype "input"))
    )
    (net (code "309") (name "Net-(IC57B-O)") (class "Default")
      (node (ref "IC57") (pin "6") (pinfunction "O_6") (pintype "output"))
      (node (ref "U$23") (pin "2") (pinfunction "I2_2") (pintype "input"))
    )
    (net (code "310") (name "Net-(IC57C-O)") (class "Default")
      (node (ref "IC57") (pin "8") (pinfunction "O_8") (pintype "output"))
      (node (ref "U$23") (pin "3") (pinfunction "I3_3") (pintype "input"))
    )
    (net (code "311") (name "Net-(IC57D-O)") (class "Default")
      (node (ref "IC57") (pin "11") (pinfunction "O_11") (pintype "output"))
      (node (ref "U$23") (pin "4") (pinfunction "I4_4") (pintype "input"))
    )
    (net (code "312") (name "Net-(IC58A-O)") (class "Default")
      (node (ref "IC58") (pin "3") (pinfunction "O_3") (pintype "output"))
      (node (ref "U$23") (pin "5") (pinfunction "I5_5") (pintype "input"))
    )
    (net (code "313") (name "Net-(IC58B-O)") (class "Default")
      (node (ref "IC58") (pin "6") (pinfunction "O_6") (pintype "output"))
      (node (ref "U$23") (pin "6") (pinfunction "I6_6") (pintype "input"))
    )
    (net (code "314") (name "Net-(IC58C-O)") (class "Default")
      (node (ref "IC58") (pin "8") (pinfunction "O_8") (pintype "output"))
      (node (ref "U$23") (pin "7") (pinfunction "I7_7") (pintype "input"))
    )
    (net (code "315") (name "Net-(IC58D-O)") (class "Default")
      (node (ref "IC58") (pin "11") (pinfunction "O_11") (pintype "output"))
      (node (ref "U$23") (pin "8") (pinfunction "I8_8") (pintype "input"))
    )
    (net (code "316") (name "Net-(IC59A-O)") (class "Default")
      (node (ref "IC59") (pin "3") (pinfunction "O_3") (pintype "output"))
      (node (ref "U$24") (pin "1") (pinfunction "I1_1") (pintype "input"))
    )
    (net (code "317") (name "Net-(IC59B-O)") (class "Default")
      (node (ref "IC59") (pin "6") (pinfunction "O_6") (pintype "output"))
      (node (ref "U$24") (pin "2") (pinfunction "I2_2") (pintype "input"))
    )
    (net (code "318") (name "Net-(IC59C-O)") (class "Default")
      (node (ref "IC59") (pin "8") (pinfunction "O_8") (pintype "output"))
      (node (ref "U$24") (pin "3") (pinfunction "I3_3") (pintype "input"))
    )
    (net (code "319") (name "Net-(IC59D-O)") (class "Default")
      (node (ref "IC59") (pin "11") (pinfunction "O_11") (pintype "output"))
      (node (ref "U$24") (pin "4") (pinfunction "I4_4") (pintype "input"))
    )
    (net (code "320") (name "Net-(IC60A-O)") (class "Default")
      (node (ref "IC60") (pin "3") (pinfunction "O_3") (pintype "output"))
      (node (ref "U$24") (pin "5") (pinfunction "I5_5") (pintype "input"))
    )
    (net (code "321") (name "Net-(IC60B-O)") (class "Default")
      (node (ref "IC60") (pin "6") (pinfunction "O_6") (pintype "output"))
      (node (ref "U$24") (pin "6") (pinfunction "I6_6") (pintype "input"))
    )
    (net (code "322") (name "Net-(IC60C-O)") (class "Default")
      (node (ref "IC60") (pin "8") (pinfunction "O_8") (pintype "output"))
      (node (ref "U$24") (pin "7") (pinfunction "I7_7") (pintype "input"))
    )
    (net (code "323") (name "Net-(IC60D-O)") (class "Default")
      (node (ref "IC60") (pin "11") (pinfunction "O_11") (pintype "output"))
      (node (ref "U$24") (pin "8") (pinfunction "I8_8") (pintype "input"))
    )
    (net (code "324") (name "Net-(IC101A-1CLK)") (class "Default")
      (node (ref "IC101") (pin "25") (pinfunction "2CLK_25") (pintype "input"))
      (node (ref "IC101") (pin "48") (pinfunction "1CLK_48") (pintype "input"))
      (node (ref "IC102") (pin "25") (pinfunction "2CLK_25") (pintype "input"))
      (node (ref "IC102") (pin "48") (pinfunction "1CLK_48") (pintype "input"))
      (node (ref "X11") (pin "6") (pinfunction "S_6") (pintype "passive"))
    )
    (net (code "325") (name "Net-(IC101A-1D1)") (class "Default")
      (node (ref "IC101") (pin "47") (pinfunction "1D1_47") (pintype "input"))
      (node (ref "X11") (pin "3") (pinfunction "S_3") (pintype "passive"))
    )
    (net (code "326") (name "Net-(IC101A-1D2)") (class "Default")
      (node (ref "IC101") (pin "2") (pinfunction "1Q1_2") (pintype "tri_state"))
      (node (ref "IC101") (pin "46") (pinfunction "1D2_46") (pintype "input"))
      (node (ref "IC22") (pin "10") (pinfunction "I1_10") (pintype "input"))
      (node (ref "IC22") (pin "13") (pinfunction "I1_13") (pintype "input"))
      (node (ref "IC22") (pin "2") (pinfunction "I1_2") (pintype "input"))
      (node (ref "IC22") (pin "5") (pinfunction "I1_5") (pintype "input"))
      (node (ref "IC23") (pin "10") (pinfunction "I1_10") (pintype "input"))
      (node (ref "IC23") (pin "13") (pinfunction "I1_13") (pintype "input"))
      (node (ref "IC23") (pin "2") (pinfunction "I1_2") (pintype "input"))
      (node (ref "IC23") (pin "5") (pinfunction "I1_5") (pintype "input"))
    )
    (net (code "327") (name "Net-(IC101A-1D3)") (class "Default")
      (node (ref "IC101") (pin "3") (pinfunction "1Q2_3") (pintype "tri_state"))
      (node (ref "IC101") (pin "44") (pinfunction "1D3_44") (pintype "input"))
      (node (ref "IC24") (pin "10") (pinfunction "I1_10") (pintype "input"))
      (node (ref "IC24") (pin "13") (pinfunction "I1_13") (pintype "input"))
      (node (ref "IC24") (pin "2") (pinfunction "I1_2") (pintype "input"))
      (node (ref "IC24") (pin "5") (pinfunction "I1_5") (pintype "input"))
      (node (ref "IC25") (pin "10") (pinfunction "I1_10") (pintype "input"))
      (node (ref "IC25") (pin "13") (pinfunction "I1_13") (pintype "input"))
      (node (ref "IC25") (pin "2") (pinfunction "I1_2") (pintype "input"))
      (node (ref "IC25") (pin "5") (pinfunction "I1_5") (pintype "input"))
    )
    (net (code "328") (name "Net-(IC101A-1D4)") (class "Default")
      (node (ref "IC101") (pin "43") (pinfunction "1D4_43") (pintype "input"))
      (node (ref "IC101") (pin "5") (pinfunction "1Q3_5") (pintype "tri_state"))
      (node (ref "IC27") (pin "10") (pinfunction "I1_10") (pintype "input"))
      (node (ref "IC27") (pin "13") (pinfunction "I1_13") (pintype "input"))
      (node (ref "IC27") (pin "2") (pinfunction "I1_2") (pintype "input"))
      (node (ref "IC27") (pin "5") (pinfunction "I1_5") (pintype "input"))
      (node (ref "IC28") (pin "10") (pinfunction "I1_10") (pintype "input"))
      (node (ref "IC28") (pin "13") (pinfunction "I1_13") (pintype "input"))
      (node (ref "IC28") (pin "2") (pinfunction "I1_2") (pintype "input"))
      (node (ref "IC28") (pin "5") (pinfunction "I1_5") (pintype "input"))
    )
    (net (code "329") (name "Net-(IC101A-1D5)") (class "Default")
      (node (ref "IC101") (pin "41") (pinfunction "1D5_41") (pintype "input"))
      (node (ref "IC101") (pin "6") (pinfunction "1Q4_6") (pintype "tri_state"))
      (node (ref "IC29") (pin "10") (pinfunction "I1_10") (pintype "input"))
      (node (ref "IC29") (pin "13") (pinfunction "I1_13") (pintype "input"))
      (node (ref "IC29") (pin "2") (pinfunction "I1_2") (pintype "input"))
      (node (ref "IC29") (pin "5") (pinfunction "I1_5") (pintype "input"))
      (node (ref "IC30") (pin "10") (pinfunction "I1_10") (pintype "input"))
      (node (ref "IC30") (pin "13") (pinfunction "I1_13") (pintype "input"))
      (node (ref "IC30") (pin "2") (pinfunction "I1_2") (pintype "input"))
      (node (ref "IC30") (pin "5") (pinfunction "I1_5") (pintype "input"))
    )
    (net (code "330") (name "Net-(IC101A-1D6)") (class "Default")
      (node (ref "IC10") (pin "10") (pinfunction "I1_10") (pintype "input"))
      (node (ref "IC10") (pin "13") (pinfunction "I1_13") (pintype "input"))
      (node (ref "IC10") (pin "2") (pinfunction "I1_2") (pintype "input"))
      (node (ref "IC10") (pin "5") (pinfunction "I1_5") (pintype "input"))
      (node (ref "IC101") (pin "40") (pinfunction "1D6_40") (pintype "input"))
      (node (ref "IC101") (pin "8") (pinfunction "1Q5_8") (pintype "tri_state"))
      (node (ref "IC7") (pin "10") (pinfunction "I1_10") (pintype "input"))
      (node (ref "IC7") (pin "13") (pinfunction "I1_13") (pintype "input"))
      (node (ref "IC7") (pin "2") (pinfunction "I1_2") (pintype "input"))
      (node (ref "IC7") (pin "5") (pinfunction "I1_5") (pintype "input"))
    )
    (net (code "331") (name "Net-(IC101A-1D7)") (class "Default")
      (node (ref "IC101") (pin "38") (pinfunction "1D7_38") (pintype "input"))
      (node (ref "IC101") (pin "9") (pinfunction "1Q6_9") (pintype "tri_state"))
      (node (ref "IC14") (pin "10") (pinfunction "I1_10") (pintype "input"))
      (node (ref "IC14") (pin "13") (pinfunction "I1_13") (pintype "input"))
      (node (ref "IC14") (pin "2") (pinfunction "I1_2") (pintype "input"))
      (node (ref "IC14") (pin "5") (pinfunction "I1_5") (pintype "input"))
      (node (ref "IC15") (pin "10") (pinfunction "I1_10") (pintype "input"))
      (node (ref "IC15") (pin "13") (pinfunction "I1_13") (pintype "input"))
      (node (ref "IC15") (pin "2") (pinfunction "I1_2") (pintype "input"))
      (node (ref "IC15") (pin "5") (pinfunction "I1_5") (pintype "input"))
    )
    (net (code "332") (name "Net-(IC101A-1D8)") (class "Default")
      (node (ref "IC101") (pin "11") (pinfunction "1Q7_11") (pintype "tri_state"))
      (node (ref "IC101") (pin "37") (pinfunction "1D8_37") (pintype "input"))
      (node (ref "IC17") (pin "10") (pinfunction "I1_10") (pintype "input"))
      (node (ref "IC17") (pin "13") (pinfunction "I1_13") (pintype "input"))
      (node (ref "IC17") (pin "2") (pinfunction "I1_2") (pintype "input"))
      (node (ref "IC17") (pin "5") (pinfunction "I1_5") (pintype "input"))
      (node (ref "IC18") (pin "10") (pinfunction "I1_10") (pintype "input"))
      (node (ref "IC18") (pin "13") (pinfunction "I1_13") (pintype "input"))
      (node (ref "IC18") (pin "2") (pinfunction "I1_2") (pintype "input"))
      (node (ref "IC18") (pin "5") (pinfunction "I1_5") (pintype "input"))
    )
    (net (code "333") (name "Net-(IC101A-1Q8)") (class "Default")
      (node (ref "IC101") (pin "12") (pinfunction "1Q8_12") (pintype "tri_state"))
      (node (ref "IC101") (pin "36") (pinfunction "2D1_36") (pintype "input"))
      (node (ref "IC19") (pin "10") (pinfunction "I1_10") (pintype "input"))
      (node (ref "IC19") (pin "13") (pinfunction "I1_13") (pintype "input"))
      (node (ref "IC19") (pin "2") (pinfunction "I1_2") (pintype "input"))
      (node (ref "IC19") (pin "5") (pinfunction "I1_5") (pintype "input"))
      (node (ref "IC20") (pin "10") (pinfunction "I1_10") (pintype "input"))
      (node (ref "IC20") (pin "13") (pinfunction "I1_13") (pintype "input"))
      (node (ref "IC20") (pin "2") (pinfunction "I1_2") (pintype "input"))
      (node (ref "IC20") (pin "5") (pinfunction "I1_5") (pintype "input"))
    )
    (net (code "334") (name "Net-(IC101A-2D2)") (class "Default")
      (node (ref "IC101") (pin "13") (pinfunction "2Q1_13") (pintype "tri_state"))
      (node (ref "IC101") (pin "35") (pinfunction "2D2_35") (pintype "input"))
      (node (ref "IC2") (pin "10") (pinfunction "I1_10") (pintype "input"))
      (node (ref "IC2") (pin "13") (pinfunction "I1_13") (pintype "input"))
      (node (ref "IC2") (pin "2") (pinfunction "I1_2") (pintype "input"))
      (node (ref "IC2") (pin "5") (pinfunction "I1_5") (pintype "input"))
      (node (ref "IC4") (pin "10") (pinfunction "I1_10") (pintype "input"))
      (node (ref "IC4") (pin "13") (pinfunction "I1_13") (pintype "input"))
      (node (ref "IC4") (pin "2") (pinfunction "I1_2") (pintype "input"))
      (node (ref "IC4") (pin "5") (pinfunction "I1_5") (pintype "input"))
    )
    (net (code "335") (name "Net-(IC101A-2D3)") (class "Default")
      (node (ref "IC101") (pin "14") (pinfunction "2Q2_14") (pintype "tri_state"))
      (node (ref "IC101") (pin "33") (pinfunction "2D3_33") (pintype "input"))
      (node (ref "IC5") (pin "10") (pinfunction "I1_10") (pintype "input"))
      (node (ref "IC5") (pin "13") (pinfunction "I1_13") (pintype "input"))
      (node (ref "IC5") (pin "2") (pinfunction "I1_2") (pintype "input"))
      (node (ref "IC5") (pin "5") (pinfunction "I1_5") (pintype "input"))
      (node (ref "IC6") (pin "10") (pinfunction "I1_10") (pintype "input"))
      (node (ref "IC6") (pin "13") (pinfunction "I1_13") (pintype "input"))
      (node (ref "IC6") (pin "2") (pinfunction "I1_2") (pintype "input"))
      (node (ref "IC6") (pin "5") (pinfunction "I1_5") (pintype "input"))
    )
    (net (code "336") (name "Net-(IC101A-2D4)") (class "Default")
      (node (ref "IC101") (pin "16") (pinfunction "2Q3_16") (pintype "tri_state"))
      (node (ref "IC101") (pin "32") (pinfunction "2D4_32") (pintype "input"))
      (node (ref "IC11") (pin "10") (pinfunction "I1_10") (pintype "input"))
      (node (ref "IC11") (pin "13") (pinfunction "I1_13") (pintype "input"))
      (node (ref "IC11") (pin "2") (pinfunction "I1_2") (pintype "input"))
      (node (ref "IC11") (pin "5") (pinfunction "I1_5") (pintype "input"))
      (node (ref "IC9") (pin "10") (pinfunction "I1_10") (pintype "input"))
      (node (ref "IC9") (pin "13") (pinfunction "I1_13") (pintype "input"))
      (node (ref "IC9") (pin "2") (pinfunction "I1_2") (pintype "input"))
      (node (ref "IC9") (pin "5") (pinfunction "I1_5") (pintype "input"))
    )
    (net (code "337") (name "Net-(IC101A-2D5)") (class "Default")
      (node (ref "IC101") (pin "17") (pinfunction "2Q4_17") (pintype "tri_state"))
      (node (ref "IC101") (pin "30") (pinfunction "2D5_30") (pintype "input"))
      (node (ref "IC12") (pin "10") (pinfunction "I1_10") (pintype "input"))
      (node (ref "IC12") (pin "13") (pinfunction "I1_13") (pintype "input"))
      (node (ref "IC12") (pin "2") (pinfunction "I1_2") (pintype "input"))
      (node (ref "IC12") (pin "5") (pinfunction "I1_5") (pintype "input"))
      (node (ref "IC13") (pin "10") (pinfunction "I1_10") (pintype "input"))
      (node (ref "IC13") (pin "13") (pinfunction "I1_13") (pintype "input"))
      (node (ref "IC13") (pin "2") (pinfunction "I1_2") (pintype "input"))
      (node (ref "IC13") (pin "5") (pinfunction "I1_5") (pintype "input"))
    )
    (net (code "338") (name "Net-(IC101A-2D6)") (class "Default")
      (node (ref "IC101") (pin "19") (pinfunction "2Q5_19") (pintype "tri_state"))
      (node (ref "IC101") (pin "29") (pinfunction "2D6_29") (pintype "input"))
      (node (ref "IC52") (pin "10") (pinfunction "I1_10") (pintype "input"))
      (node (ref "IC52") (pin "13") (pinfunction "I1_13") (pintype "input"))
      (node (ref "IC52") (pin "2") (pinfunction "I1_2") (pintype "input"))
      (node (ref "IC52") (pin "5") (pinfunction "I1_5") (pintype "input"))
      (node (ref "IC53") (pin "10") (pinfunction "I1_10") (pintype "input"))
      (node (ref "IC53") (pin "13") (pinfunction "I1_13") (pintype "input"))
      (node (ref "IC53") (pin "2") (pinfunction "I1_2") (pintype "input"))
      (node (ref "IC53") (pin "5") (pinfunction "I1_5") (pintype "input"))
    )
    (net (code "339") (name "Net-(IC101A-2D7)") (class "Default")
      (node (ref "IC101") (pin "20") (pinfunction "2Q6_20") (pintype "tri_state"))
      (node (ref "IC101") (pin "27") (pinfunction "2D7_27") (pintype "input"))
      (node (ref "IC54") (pin "10") (pinfunction "I1_10") (pintype "input"))
      (node (ref "IC54") (pin "13") (pinfunction "I1_13") (pintype "input"))
      (node (ref "IC54") (pin "2") (pinfunction "I1_2") (pintype "input"))
      (node (ref "IC54") (pin "5") (pinfunction "I1_5") (pintype "input"))
      (node (ref "IC55") (pin "10") (pinfunction "I1_10") (pintype "input"))
      (node (ref "IC55") (pin "13") (pinfunction "I1_13") (pintype "input"))
      (node (ref "IC55") (pin "2") (pinfunction "I1_2") (pintype "input"))
      (node (ref "IC55") (pin "5") (pinfunction "I1_5") (pintype "input"))
    )
    (net (code "340") (name "Net-(IC101A-2D8)") (class "Default")
      (node (ref "IC101") (pin "22") (pinfunction "2Q7_22") (pintype "tri_state"))
      (node (ref "IC101") (pin "26") (pinfunction "2D8_26") (pintype "input"))
      (node (ref "IC57") (pin "10") (pinfunction "I1_10") (pintype "input"))
      (node (ref "IC57") (pin "13") (pinfunction "I1_13") (pintype "input"))
      (node (ref "IC57") (pin "2") (pinfunction "I1_2") (pintype "input"))
      (node (ref "IC57") (pin "5") (pinfunction "I1_5") (pintype "input"))
      (node (ref "IC58") (pin "10") (pinfunction "I1_10") (pintype "input"))
      (node (ref "IC58") (pin "13") (pinfunction "I1_13") (pintype "input"))
      (node (ref "IC58") (pin "2") (pinfunction "I1_2") (pintype "input"))
      (node (ref "IC58") (pin "5") (pinfunction "I1_5") (pintype "input"))
    )
    (net (code "341") (name "Net-(IC101A-2Q8)") (class "Default")
      (node (ref "IC101") (pin "23") (pinfunction "2Q8_23") (pintype "tri_state"))
      (node (ref "IC102") (pin "47") (pinfunction "1D1_47") (pintype "input"))
      (node (ref "IC59") (pin "10") (pinfunction "I1_10") (pintype "input"))
      (node (ref "IC59") (pin "13") (pinfunction "I1_13") (pintype "input"))
      (node (ref "IC59") (pin "2") (pinfunction "I1_2") (pintype "input"))
      (node (ref "IC59") (pin "5") (pinfunction "I1_5") (pintype "input"))
      (node (ref "IC60") (pin "10") (pinfunction "I1_10") (pintype "input"))
      (node (ref "IC60") (pin "13") (pinfunction "I1_13") (pintype "input"))
      (node (ref "IC60") (pin "2") (pinfunction "I1_2") (pintype "input"))
      (node (ref "IC60") (pin "5") (pinfunction "I1_5") (pintype "input"))
    )
    (net (code "342") (name "Net-(IC102A-1D2)") (class "Default")
      (node (ref "IC102") (pin "2") (pinfunction "1Q1_2") (pintype "tri_state"))
      (node (ref "IC102") (pin "46") (pinfunction "1D2_46") (pintype "input"))
      (node (ref "IC42") (pin "10") (pinfunction "I1_10") (pintype "input"))
      (node (ref "IC42") (pin "13") (pinfunction "I1_13") (pintype "input"))
      (node (ref "IC42") (pin "2") (pinfunction "I1_2") (pintype "input"))
      (node (ref "IC42") (pin "5") (pinfunction "I1_5") (pintype "input"))
      (node (ref "IC43") (pin "10") (pinfunction "I1_10") (pintype "input"))
      (node (ref "IC43") (pin "13") (pinfunction "I1_13") (pintype "input"))
      (node (ref "IC43") (pin "2") (pinfunction "I1_2") (pintype "input"))
      (node (ref "IC43") (pin "5") (pinfunction "I1_5") (pintype "input"))
    )
    (net (code "343") (name "Net-(IC102A-1D3)") (class "Default")
      (node (ref "IC102") (pin "3") (pinfunction "1Q2_3") (pintype "tri_state"))
      (node (ref "IC102") (pin "44") (pinfunction "1D3_44") (pintype "input"))
      (node (ref "IC44") (pin "10") (pinfunction "I1_10") (pintype "input"))
      (node (ref "IC44") (pin "13") (pinfunction "I1_13") (pintype "input"))
      (node (ref "IC44") (pin "2") (pinfunction "I1_2") (pintype "input"))
      (node (ref "IC44") (pin "5") (pinfunction "I1_5") (pintype "input"))
      (node (ref "IC45") (pin "10") (pinfunction "I1_10") (pintype "input"))
      (node (ref "IC45") (pin "13") (pinfunction "I1_13") (pintype "input"))
      (node (ref "IC45") (pin "2") (pinfunction "I1_2") (pintype "input"))
      (node (ref "IC45") (pin "5") (pinfunction "I1_5") (pintype "input"))
    )
    (net (code "344") (name "Net-(IC102A-1D4)") (class "Default")
      (node (ref "IC102") (pin "43") (pinfunction "1D4_43") (pintype "input"))
      (node (ref "IC102") (pin "5") (pinfunction "1Q3_5") (pintype "tri_state"))
      (node (ref "IC47") (pin "10") (pinfunction "I1_10") (pintype "input"))
      (node (ref "IC47") (pin "13") (pinfunction "I1_13") (pintype "input"))
      (node (ref "IC47") (pin "2") (pinfunction "I1_2") (pintype "input"))
      (node (ref "IC47") (pin "5") (pinfunction "I1_5") (pintype "input"))
      (node (ref "IC48") (pin "10") (pinfunction "I1_10") (pintype "input"))
      (node (ref "IC48") (pin "13") (pinfunction "I1_13") (pintype "input"))
      (node (ref "IC48") (pin "2") (pinfunction "I1_2") (pintype "input"))
      (node (ref "IC48") (pin "5") (pinfunction "I1_5") (pintype "input"))
    )
    (net (code "345") (name "Net-(IC102A-1D5)") (class "Default")
      (node (ref "IC102") (pin "41") (pinfunction "1D5_41") (pintype "input"))
      (node (ref "IC102") (pin "6") (pinfunction "1Q4_6") (pintype "tri_state"))
      (node (ref "IC49") (pin "10") (pinfunction "I1_10") (pintype "input"))
      (node (ref "IC49") (pin "13") (pinfunction "I1_13") (pintype "input"))
      (node (ref "IC49") (pin "2") (pinfunction "I1_2") (pintype "input"))
      (node (ref "IC49") (pin "5") (pinfunction "I1_5") (pintype "input"))
      (node (ref "IC50") (pin "10") (pinfunction "I1_10") (pintype "input"))
      (node (ref "IC50") (pin "13") (pinfunction "I1_13") (pintype "input"))
      (node (ref "IC50") (pin "2") (pinfunction "I1_2") (pintype "input"))
      (node (ref "IC50") (pin "5") (pinfunction "I1_5") (pintype "input"))
      (node (ref "X11") (pin "1") (pinfunction "S_1") (pintype "passive"))
    )
    (net (code "346") (name "Net-(U$1-CD+)") (class "Default")
      (node (ref "U$1") (pin "10") (pinfunction "CD+_10") (pintype "passive"))
      (node (ref "U$10") (pin "10") (pinfunction "CD+_10") (pintype "passive"))
      (node (ref "U$11") (pin "10") (pinfunction "CD+_10") (pintype "passive"))
      (node (ref "U$12") (pin "10") (pinfunction "CD+_10") (pintype "passive"))
      (node (ref "U$17") (pin "10") (pinfunction "CD+_10") (pintype "passive"))
      (node (ref "U$18") (pin "10") (pinfunction "CD+_10") (pintype "passive"))
      (node (ref "U$19") (pin "10") (pinfunction "CD+_10") (pintype "passive"))
      (node (ref "U$2") (pin "10") (pinfunction "CD+_10") (pintype "passive"))
      (node (ref "U$20") (pin "10") (pinfunction "CD+_10") (pintype "passive"))
      (node (ref "U$21") (pin "10") (pinfunction "CD+_10") (pintype "passive"))
      (node (ref "U$22") (pin "10") (pinfunction "CD+_10") (pintype "passive"))
      (node (ref "U$23") (pin "10") (pinfunction "CD+_10") (pintype "passive"))
      (node (ref "U$24") (pin "10") (pinfunction "CD+_10") (pintype "passive"))
      (node (ref "U$3") (pin "10") (pinfunction "CD+_10") (pintype "passive"))
      (node (ref "U$4") (pin "10") (pinfunction "CD+_10") (pintype "passive"))
      (node (ref "U$5") (pin "10") (pinfunction "CD+_10") (pintype "passive"))
      (node (ref "U$6") (pin "10") (pinfunction "CD+_10") (pintype "passive"))
      (node (ref "U$7") (pin "10") (pinfunction "CD+_10") (pintype "passive"))
      (node (ref "U$8") (pin "10") (pinfunction "CD+_10") (pintype "passive"))
      (node (ref "U$9") (pin "10") (pinfunction "CD+_10") (pintype "passive"))
      (node (ref "X11") (pin "7") (pinfunction "S_7") (pintype "passive"))
    )
    (net (code "347") (name "Net-(U$1-O1)") (class "Default")
      (node (ref "U$1") (pin "18") (pinfunction "O1_18") (pintype "open_collector"))
      (node (ref "X2") (pin "1") (pinfunction "S_1") (pintype "passive"))
    )
    (net (code "348") (name "Net-(U$1-O2)") (class "Default")
      (node (ref "U$1") (pin "17") (pinfunction "O2_17") (pintype "open_collector"))
      (node (ref "X2") (pin "3") (pinfunction "S_3") (pintype "passive"))
    )
    (net (code "349") (name "Net-(U$1-O3)") (class "Default")
      (node (ref "U$1") (pin "16") (pinfunction "O3_16") (pintype "open_collector"))
      (node (ref "X2") (pin "5") (pinfunction "S_5") (pintype "passive"))
    )
    (net (code "350") (name "Net-(U$1-O4)") (class "Default")
      (node (ref "U$1") (pin "15") (pinfunction "O4_15") (pintype "open_collector"))
      (node (ref "X2") (pin "7") (pinfunction "S_7") (pintype "passive"))
    )
    (net (code "351") (name "Net-(U$1-O5)") (class "Default")
      (node (ref "U$1") (pin "14") (pinfunction "O5_14") (pintype "open_collector"))
      (node (ref "X2") (pin "9") (pinfunction "S_9") (pintype "passive"))
    )
    (net (code "352") (name "Net-(U$1-O6)") (class "Default")
      (node (ref "U$1") (pin "13") (pinfunction "O6_13") (pintype "open_collector"))
      (node (ref "X2") (pin "11") (pinfunction "S_11") (pintype "passive"))
    )
    (net (code "353") (name "Net-(U$1-O7)") (class "Default")
      (node (ref "U$1") (pin "12") (pinfunction "O7_12") (pintype "open_collector"))
      (node (ref "X2") (pin "13") (pinfunction "S_13") (pintype "passive"))
    )
    (net (code "354") (name "Net-(U$1-O8)") (class "Default")
      (node (ref "U$1") (pin "11") (pinfunction "O8_11") (pintype "open_collector"))
      (node (ref "X2") (pin "15") (pinfunction "S_15") (pintype "passive"))
    )
    (net (code "355") (name "Net-(U$2-O1)") (class "Default")
      (node (ref "U$2") (pin "18") (pinfunction "O1_18") (pintype "open_collector"))
      (node (ref "X2") (pin "17") (pinfunction "S_17") (pintype "passive"))
    )
    (net (code "356") (name "Net-(U$2-O2)") (class "Default")
      (node (ref "U$2") (pin "17") (pinfunction "O2_17") (pintype "open_collector"))
      (node (ref "X2") (pin "19") (pinfunction "S_19") (pintype "passive"))
    )
    (net (code "357") (name "Net-(U$2-O3)") (class "Default")
      (node (ref "U$2") (pin "16") (pinfunction "O3_16") (pintype "open_collector"))
      (node (ref "X2") (pin "21") (pinfunction "S_21") (pintype "passive"))
    )
    (net (code "358") (name "Net-(U$2-O4)") (class "Default")
      (node (ref "U$2") (pin "15") (pinfunction "O4_15") (pintype "open_collector"))
      (node (ref "X2") (pin "23") (pinfunction "S_23") (pintype "passive"))
    )
    (net (code "359") (name "Net-(U$2-O5)") (class "Default")
      (node (ref "U$2") (pin "14") (pinfunction "O5_14") (pintype "open_collector"))
      (node (ref "X2") (pin "25") (pinfunction "S_25") (pintype "passive"))
    )
    (net (code "360") (name "Net-(U$2-O6)") (class "Default")
      (node (ref "U$2") (pin "13") (pinfunction "O6_13") (pintype "open_collector"))
      (node (ref "X2") (pin "27") (pinfunction "S_27") (pintype "passive"))
    )
    (net (code "361") (name "Net-(U$2-O7)") (class "Default")
      (node (ref "U$2") (pin "12") (pinfunction "O7_12") (pintype "open_collector"))
      (node (ref "X2") (pin "29") (pinfunction "S_29") (pintype "passive"))
    )
    (net (code "362") (name "Net-(U$2-O8)") (class "Default")
      (node (ref "U$2") (pin "11") (pinfunction "O8_11") (pintype "open_collector"))
      (node (ref "X2") (pin "31") (pinfunction "S_31") (pintype "passive"))
    )
    (net (code "363") (name "Net-(U$3-O1)") (class "Default")
      (node (ref "U$3") (pin "18") (pinfunction "O1_18") (pintype "open_collector"))
      (node (ref "X2") (pin "2") (pinfunction "S_2") (pintype "passive"))
    )
    (net (code "364") (name "Net-(U$3-O2)") (class "Default")
      (node (ref "U$3") (pin "17") (pinfunction "O2_17") (pintype "open_collector"))
      (node (ref "X2") (pin "4") (pinfunction "S_4") (pintype "passive"))
    )
    (net (code "365") (name "Net-(U$3-O3)") (class "Default")
      (node (ref "U$3") (pin "16") (pinfunction "O3_16") (pintype "open_collector"))
      (node (ref "X2") (pin "6") (pinfunction "S_6") (pintype "passive"))
    )
    (net (code "366") (name "Net-(U$3-O4)") (class "Default")
      (node (ref "U$3") (pin "15") (pinfunction "O4_15") (pintype "open_collector"))
      (node (ref "X2") (pin "8") (pinfunction "S_8") (pintype "passive"))
    )
    (net (code "367") (name "Net-(U$3-O5)") (class "Default")
      (node (ref "U$3") (pin "14") (pinfunction "O5_14") (pintype "open_collector"))
      (node (ref "X2") (pin "10") (pinfunction "S_10") (pintype "passive"))
    )
    (net (code "368") (name "Net-(U$3-O6)") (class "Default")
      (node (ref "U$3") (pin "13") (pinfunction "O6_13") (pintype "open_collector"))
      (node (ref "X2") (pin "12") (pinfunction "S_12") (pintype "passive"))
    )
    (net (code "369") (name "Net-(U$3-O7)") (class "Default")
      (node (ref "U$3") (pin "12") (pinfunction "O7_12") (pintype "open_collector"))
      (node (ref "X2") (pin "14") (pinfunction "S_14") (pintype "passive"))
    )
    (net (code "370") (name "Net-(U$3-O8)") (class "Default")
      (node (ref "U$3") (pin "11") (pinfunction "O8_11") (pintype "open_collector"))
      (node (ref "X2") (pin "16") (pinfunction "S_16") (pintype "passive"))
    )
    (net (code "371") (name "Net-(U$4-O1)") (class "Default")
      (node (ref "U$4") (pin "18") (pinfunction "O1_18") (pintype "open_collector"))
      (node (ref "X2") (pin "18") (pinfunction "S_18") (pintype "passive"))
    )
    (net (code "372") (name "Net-(U$4-O2)") (class "Default")
      (node (ref "U$4") (pin "17") (pinfunction "O2_17") (pintype "open_collector"))
      (node (ref "X2") (pin "20") (pinfunction "S_20") (pintype "passive"))
    )
    (net (code "373") (name "Net-(U$4-O3)") (class "Default")
      (node (ref "U$4") (pin "16") (pinfunction "O3_16") (pintype "open_collector"))
      (node (ref "X2") (pin "22") (pinfunction "S_22") (pintype "passive"))
    )
    (net (code "374") (name "Net-(U$4-O4)") (class "Default")
      (node (ref "U$4") (pin "15") (pinfunction "O4_15") (pintype "open_collector"))
      (node (ref "X2") (pin "24") (pinfunction "S_24") (pintype "passive"))
    )
    (net (code "375") (name "Net-(U$4-O5)") (class "Default")
      (node (ref "U$4") (pin "14") (pinfunction "O5_14") (pintype "open_collector"))
      (node (ref "X2") (pin "26") (pinfunction "S_26") (pintype "passive"))
    )
    (net (code "376") (name "Net-(U$4-O6)") (class "Default")
      (node (ref "U$4") (pin "13") (pinfunction "O6_13") (pintype "open_collector"))
      (node (ref "X2") (pin "28") (pinfunction "S_28") (pintype "passive"))
    )
    (net (code "377") (name "Net-(U$4-O7)") (class "Default")
      (node (ref "U$4") (pin "12") (pinfunction "O7_12") (pintype "open_collector"))
      (node (ref "X2") (pin "30") (pinfunction "S_30") (pintype "passive"))
    )
    (net (code "378") (name "Net-(U$4-O8)") (class "Default")
      (node (ref "U$4") (pin "11") (pinfunction "O8_11") (pintype "open_collector"))
      (node (ref "X2") (pin "32") (pinfunction "S_32") (pintype "passive"))
    )
    (net (code "379") (name "Net-(U$5-O1)") (class "Default")
      (node (ref "U$5") (pin "18") (pinfunction "O1_18") (pintype "open_collector"))
      (node (ref "X1") (pin "1") (pinfunction "S_1") (pintype "passive"))
    )
    (net (code "380") (name "Net-(U$5-O2)") (class "Default")
      (node (ref "U$5") (pin "17") (pinfunction "O2_17") (pintype "open_collector"))
      (node (ref "X1") (pin "3") (pinfunction "S_3") (pintype "passive"))
    )
    (net (code "381") (name "Net-(U$5-O3)") (class "Default")
      (node (ref "U$5") (pin "16") (pinfunction "O3_16") (pintype "open_collector"))
      (node (ref "X1") (pin "5") (pinfunction "S_5") (pintype "passive"))
    )
    (net (code "382") (name "Net-(U$5-O4)") (class "Default")
      (node (ref "U$5") (pin "15") (pinfunction "O4_15") (pintype "open_collector"))
      (node (ref "X1") (pin "7") (pinfunction "S_7") (pintype "passive"))
    )
    (net (code "383") (name "Net-(U$5-O5)") (class "Default")
      (node (ref "U$5") (pin "14") (pinfunction "O5_14") (pintype "open_collector"))
      (node (ref "X1") (pin "9") (pinfunction "S_9") (pintype "passive"))
    )
    (net (code "384") (name "Net-(U$5-O6)") (class "Default")
      (node (ref "U$5") (pin "13") (pinfunction "O6_13") (pintype "open_collector"))
      (node (ref "X1") (pin "11") (pinfunction "S_11") (pintype "passive"))
    )
    (net (code "385") (name "Net-(U$5-O7)") (class "Default")
      (node (ref "U$5") (pin "12") (pinfunction "O7_12") (pintype "open_collector"))
      (node (ref "X1") (pin "13") (pinfunction "S_13") (pintype "passive"))
    )
    (net (code "386") (name "Net-(U$5-O8)") (class "Default")
      (node (ref "U$5") (pin "11") (pinfunction "O8_11") (pintype "open_collector"))
      (node (ref "X1") (pin "15") (pinfunction "S_15") (pintype "passive"))
    )
    (net (code "387") (name "Net-(U$6-O1)") (class "Default")
      (node (ref "U$6") (pin "18") (pinfunction "O1_18") (pintype "open_collector"))
      (node (ref "X1") (pin "17") (pinfunction "S_17") (pintype "passive"))
    )
    (net (code "388") (name "Net-(U$6-O2)") (class "Default")
      (node (ref "U$6") (pin "17") (pinfunction "O2_17") (pintype "open_collector"))
      (node (ref "X1") (pin "19") (pinfunction "S_19") (pintype "passive"))
    )
    (net (code "389") (name "Net-(U$6-O3)") (class "Default")
      (node (ref "U$6") (pin "16") (pinfunction "O3_16") (pintype "open_collector"))
      (node (ref "X1") (pin "21") (pinfunction "S_21") (pintype "passive"))
    )
    (net (code "390") (name "Net-(U$6-O4)") (class "Default")
      (node (ref "U$6") (pin "15") (pinfunction "O4_15") (pintype "open_collector"))
      (node (ref "X1") (pin "23") (pinfunction "S_23") (pintype "passive"))
    )
    (net (code "391") (name "Net-(U$6-O5)") (class "Default")
      (node (ref "U$6") (pin "14") (pinfunction "O5_14") (pintype "open_collector"))
      (node (ref "X1") (pin "25") (pinfunction "S_25") (pintype "passive"))
    )
    (net (code "392") (name "Net-(U$6-O6)") (class "Default")
      (node (ref "U$6") (pin "13") (pinfunction "O6_13") (pintype "open_collector"))
      (node (ref "X1") (pin "27") (pinfunction "S_27") (pintype "passive"))
    )
    (net (code "393") (name "Net-(U$6-O7)") (class "Default")
      (node (ref "U$6") (pin "12") (pinfunction "O7_12") (pintype "open_collector"))
      (node (ref "X1") (pin "29") (pinfunction "S_29") (pintype "passive"))
    )
    (net (code "394") (name "Net-(U$6-O8)") (class "Default")
      (node (ref "U$6") (pin "11") (pinfunction "O8_11") (pintype "open_collector"))
      (node (ref "X1") (pin "31") (pinfunction "S_31") (pintype "passive"))
    )
    (net (code "395") (name "Net-(U$7-O1)") (class "Default")
      (node (ref "U$7") (pin "18") (pinfunction "O1_18") (pintype "open_collector"))
      (node (ref "X1") (pin "2") (pinfunction "S_2") (pintype "passive"))
    )
    (net (code "396") (name "Net-(U$7-O2)") (class "Default")
      (node (ref "U$7") (pin "17") (pinfunction "O2_17") (pintype "open_collector"))
      (node (ref "X1") (pin "4") (pinfunction "S_4") (pintype "passive"))
    )
    (net (code "397") (name "Net-(U$7-O3)") (class "Default")
      (node (ref "U$7") (pin "16") (pinfunction "O3_16") (pintype "open_collector"))
      (node (ref "X1") (pin "6") (pinfunction "S_6") (pintype "passive"))
    )
    (net (code "398") (name "Net-(U$7-O4)") (class "Default")
      (node (ref "U$7") (pin "15") (pinfunction "O4_15") (pintype "open_collector"))
      (node (ref "X1") (pin "8") (pinfunction "S_8") (pintype "passive"))
    )
    (net (code "399") (name "Net-(U$7-O5)") (class "Default")
      (node (ref "U$7") (pin "14") (pinfunction "O5_14") (pintype "open_collector"))
      (node (ref "X1") (pin "10") (pinfunction "S_10") (pintype "passive"))
    )
    (net (code "400") (name "Net-(U$7-O6)") (class "Default")
      (node (ref "U$7") (pin "13") (pinfunction "O6_13") (pintype "open_collector"))
      (node (ref "X1") (pin "12") (pinfunction "S_12") (pintype "passive"))
    )
    (net (code "401") (name "Net-(U$7-O7)") (class "Default")
      (node (ref "U$7") (pin "12") (pinfunction "O7_12") (pintype "open_collector"))
      (node (ref "X1") (pin "14") (pinfunction "S_14") (pintype "passive"))
    )
    (net (code "402") (name "Net-(U$7-O8)") (class "Default")
      (node (ref "U$7") (pin "11") (pinfunction "O8_11") (pintype "open_collector"))
      (node (ref "X1") (pin "16") (pinfunction "S_16") (pintype "passive"))
    )
    (net (code "403") (name "Net-(U$8-O1)") (class "Default")
      (node (ref "U$8") (pin "18") (pinfunction "O1_18") (pintype "open_collector"))
      (node (ref "X1") (pin "18") (pinfunction "S_18") (pintype "passive"))
    )
    (net (code "404") (name "Net-(U$8-O2)") (class "Default")
      (node (ref "U$8") (pin "17") (pinfunction "O2_17") (pintype "open_collector"))
      (node (ref "X1") (pin "20") (pinfunction "S_20") (pintype "passive"))
    )
    (net (code "405") (name "Net-(U$8-O3)") (class "Default")
      (node (ref "U$8") (pin "16") (pinfunction "O3_16") (pintype "open_collector"))
      (node (ref "X1") (pin "22") (pinfunction "S_22") (pintype "passive"))
    )
    (net (code "406") (name "Net-(U$8-O4)") (class "Default")
      (node (ref "U$8") (pin "15") (pinfunction "O4_15") (pintype "open_collector"))
      (node (ref "X1") (pin "24") (pinfunction "S_24") (pintype "passive"))
    )
    (net (code "407") (name "Net-(U$8-O5)") (class "Default")
      (node (ref "U$8") (pin "14") (pinfunction "O5_14") (pintype "open_collector"))
      (node (ref "X1") (pin "26") (pinfunction "S_26") (pintype "passive"))
    )
    (net (code "408") (name "Net-(U$8-O6)") (class "Default")
      (node (ref "U$8") (pin "13") (pinfunction "O6_13") (pintype "open_collector"))
      (node (ref "X1") (pin "28") (pinfunction "S_28") (pintype "passive"))
    )
    (net (code "409") (name "Net-(U$8-O7)") (class "Default")
      (node (ref "U$8") (pin "12") (pinfunction "O7_12") (pintype "open_collector"))
      (node (ref "X1") (pin "30") (pinfunction "S_30") (pintype "passive"))
    )
    (net (code "410") (name "Net-(U$8-O8)") (class "Default")
      (node (ref "U$8") (pin "11") (pinfunction "O8_11") (pintype "open_collector"))
      (node (ref "X1") (pin "32") (pinfunction "S_32") (pintype "passive"))
    )
    (net (code "411") (name "Net-(U$9-O1)") (class "Default")
      (node (ref "U$9") (pin "18") (pinfunction "O1_18") (pintype "open_collector"))
      (node (ref "X3") (pin "1") (pinfunction "S_1") (pintype "passive"))
    )
    (net (code "412") (name "Net-(U$9-O2)") (class "Default")
      (node (ref "U$9") (pin "17") (pinfunction "O2_17") (pintype "open_collector"))
      (node (ref "X3") (pin "3") (pinfunction "S_3") (pintype "passive"))
    )
    (net (code "413") (name "Net-(U$9-O3)") (class "Default")
      (node (ref "U$9") (pin "16") (pinfunction "O3_16") (pintype "open_collector"))
      (node (ref "X3") (pin "5") (pinfunction "S_5") (pintype "passive"))
    )
    (net (code "414") (name "Net-(U$9-O4)") (class "Default")
      (node (ref "U$9") (pin "15") (pinfunction "O4_15") (pintype "open_collector"))
      (node (ref "X3") (pin "7") (pinfunction "S_7") (pintype "passive"))
    )
    (net (code "415") (name "Net-(U$9-O5)") (class "Default")
      (node (ref "U$9") (pin "14") (pinfunction "O5_14") (pintype "open_collector"))
      (node (ref "X3") (pin "9") (pinfunction "S_9") (pintype "passive"))
    )
    (net (code "416") (name "Net-(U$9-O6)") (class "Default")
      (node (ref "U$9") (pin "13") (pinfunction "O6_13") (pintype "open_collector"))
      (node (ref "X3") (pin "11") (pinfunction "S_11") (pintype "passive"))
    )
    (net (code "417") (name "Net-(U$9-O7)") (class "Default")
      (node (ref "U$9") (pin "12") (pinfunction "O7_12") (pintype "open_collector"))
      (node (ref "X3") (pin "13") (pinfunction "S_13") (pintype "passive"))
    )
    (net (code "418") (name "Net-(U$9-O8)") (class "Default")
      (node (ref "U$9") (pin "11") (pinfunction "O8_11") (pintype "open_collector"))
      (node (ref "X3") (pin "15") (pinfunction "S_15") (pintype "passive"))
    )
    (net (code "419") (name "Net-(U$10-O1)") (class "Default")
      (node (ref "U$10") (pin "18") (pinfunction "O1_18") (pintype "open_collector"))
      (node (ref "X3") (pin "17") (pinfunction "S_17") (pintype "passive"))
    )
    (net (code "420") (name "Net-(U$10-O2)") (class "Default")
      (node (ref "U$10") (pin "17") (pinfunction "O2_17") (pintype "open_collector"))
      (node (ref "X3") (pin "19") (pinfunction "S_19") (pintype "passive"))
    )
    (net (code "421") (name "Net-(U$10-O3)") (class "Default")
      (node (ref "U$10") (pin "16") (pinfunction "O3_16") (pintype "open_collector"))
      (node (ref "X3") (pin "21") (pinfunction "S_21") (pintype "passive"))
    )
    (net (code "422") (name "Net-(U$10-O4)") (class "Default")
      (node (ref "U$10") (pin "15") (pinfunction "O4_15") (pintype "open_collector"))
      (node (ref "X3") (pin "23") (pinfunction "S_23") (pintype "passive"))
    )
    (net (code "423") (name "Net-(U$10-O5)") (class "Default")
      (node (ref "U$10") (pin "14") (pinfunction "O5_14") (pintype "open_collector"))
      (node (ref "X3") (pin "25") (pinfunction "S_25") (pintype "passive"))
    )
    (net (code "424") (name "Net-(U$10-O6)") (class "Default")
      (node (ref "U$10") (pin "13") (pinfunction "O6_13") (pintype "open_collector"))
      (node (ref "X3") (pin "27") (pinfunction "S_27") (pintype "passive"))
    )
    (net (code "425") (name "Net-(U$10-O7)") (class "Default")
      (node (ref "U$10") (pin "12") (pinfunction "O7_12") (pintype "open_collector"))
      (node (ref "X3") (pin "29") (pinfunction "S_29") (pintype "passive"))
    )
    (net (code "426") (name "Net-(U$10-O8)") (class "Default")
      (node (ref "U$10") (pin "11") (pinfunction "O8_11") (pintype "open_collector"))
      (node (ref "X3") (pin "31") (pinfunction "S_31") (pintype "passive"))
    )
    (net (code "427") (name "Net-(U$11-O1)") (class "Default")
      (node (ref "U$11") (pin "18") (pinfunction "O1_18") (pintype "open_collector"))
      (node (ref "X3") (pin "2") (pinfunction "S_2") (pintype "passive"))
    )
    (net (code "428") (name "Net-(U$11-O2)") (class "Default")
      (node (ref "U$11") (pin "17") (pinfunction "O2_17") (pintype "open_collector"))
      (node (ref "X3") (pin "4") (pinfunction "S_4") (pintype "passive"))
    )
    (net (code "429") (name "Net-(U$11-O3)") (class "Default")
      (node (ref "U$11") (pin "16") (pinfunction "O3_16") (pintype "open_collector"))
      (node (ref "X3") (pin "6") (pinfunction "S_6") (pintype "passive"))
    )
    (net (code "430") (name "Net-(U$11-O4)") (class "Default")
      (node (ref "U$11") (pin "15") (pinfunction "O4_15") (pintype "open_collector"))
      (node (ref "X3") (pin "8") (pinfunction "S_8") (pintype "passive"))
    )
    (net (code "431") (name "Net-(U$11-O5)") (class "Default")
      (node (ref "U$11") (pin "14") (pinfunction "O5_14") (pintype "open_collector"))
      (node (ref "X3") (pin "10") (pinfunction "S_10") (pintype "passive"))
    )
    (net (code "432") (name "Net-(U$11-O6)") (class "Default")
      (node (ref "U$11") (pin "13") (pinfunction "O6_13") (pintype "open_collector"))
      (node (ref "X3") (pin "12") (pinfunction "S_12") (pintype "passive"))
    )
    (net (code "433") (name "Net-(U$11-O7)") (class "Default")
      (node (ref "U$11") (pin "12") (pinfunction "O7_12") (pintype "open_collector"))
      (node (ref "X3") (pin "14") (pinfunction "S_14") (pintype "passive"))
    )
    (net (code "434") (name "Net-(U$11-O8)") (class "Default")
      (node (ref "U$11") (pin "11") (pinfunction "O8_11") (pintype "open_collector"))
      (node (ref "X3") (pin "16") (pinfunction "S_16") (pintype "passive"))
    )
    (net (code "435") (name "Net-(U$12-O1)") (class "Default")
      (node (ref "U$12") (pin "18") (pinfunction "O1_18") (pintype "open_collector"))
      (node (ref "X3") (pin "18") (pinfunction "S_18") (pintype "passive"))
    )
    (net (code "436") (name "Net-(U$12-O2)") (class "Default")
      (node (ref "U$12") (pin "17") (pinfunction "O2_17") (pintype "open_collector"))
      (node (ref "X3") (pin "20") (pinfunction "S_20") (pintype "passive"))
    )
    (net (code "437") (name "Net-(U$12-O3)") (class "Default")
      (node (ref "U$12") (pin "16") (pinfunction "O3_16") (pintype "open_collector"))
      (node (ref "X3") (pin "22") (pinfunction "S_22") (pintype "passive"))
    )
    (net (code "438") (name "Net-(U$12-O4)") (class "Default")
      (node (ref "U$12") (pin "15") (pinfunction "O4_15") (pintype "open_collector"))
      (node (ref "X3") (pin "24") (pinfunction "S_24") (pintype "passive"))
    )
    (net (code "439") (name "Net-(U$12-O5)") (class "Default")
      (node (ref "U$12") (pin "14") (pinfunction "O5_14") (pintype "open_collector"))
      (node (ref "X3") (pin "26") (pinfunction "S_26") (pintype "passive"))
    )
    (net (code "440") (name "Net-(U$12-O6)") (class "Default")
      (node (ref "U$12") (pin "13") (pinfunction "O6_13") (pintype "open_collector"))
      (node (ref "X3") (pin "28") (pinfunction "S_28") (pintype "passive"))
    )
    (net (code "441") (name "Net-(U$12-O7)") (class "Default")
      (node (ref "U$12") (pin "12") (pinfunction "O7_12") (pintype "open_collector"))
      (node (ref "X3") (pin "30") (pinfunction "S_30") (pintype "passive"))
    )
    (net (code "442") (name "Net-(U$12-O8)") (class "Default")
      (node (ref "U$12") (pin "11") (pinfunction "O8_11") (pintype "open_collector"))
      (node (ref "X3") (pin "32") (pinfunction "S_32") (pintype "passive"))
    )
    (net (code "443") (name "Net-(U$17-O1)") (class "Default")
      (node (ref "U$17") (pin "18") (pinfunction "O1_18") (pintype "open_collector"))
      (node (ref "X5") (pin "1") (pinfunction "S_1") (pintype "passive"))
    )
    (net (code "444") (name "Net-(U$17-O2)") (class "Default")
      (node (ref "U$17") (pin "17") (pinfunction "O2_17") (pintype "open_collector"))
      (node (ref "X5") (pin "3") (pinfunction "S_3") (pintype "passive"))
    )
    (net (code "445") (name "Net-(U$17-O3)") (class "Default")
      (node (ref "U$17") (pin "16") (pinfunction "O3_16") (pintype "open_collector"))
      (node (ref "X5") (pin "5") (pinfunction "S_5") (pintype "passive"))
    )
    (net (code "446") (name "Net-(U$17-O4)") (class "Default")
      (node (ref "U$17") (pin "15") (pinfunction "O4_15") (pintype "open_collector"))
      (node (ref "X5") (pin "7") (pinfunction "S_7") (pintype "passive"))
    )
    (net (code "447") (name "Net-(U$17-O5)") (class "Default")
      (node (ref "U$17") (pin "14") (pinfunction "O5_14") (pintype "open_collector"))
      (node (ref "X5") (pin "9") (pinfunction "S_9") (pintype "passive"))
    )
    (net (code "448") (name "Net-(U$17-O6)") (class "Default")
      (node (ref "U$17") (pin "13") (pinfunction "O6_13") (pintype "open_collector"))
      (node (ref "X5") (pin "11") (pinfunction "S_11") (pintype "passive"))
    )
    (net (code "449") (name "Net-(U$17-O7)") (class "Default")
      (node (ref "U$17") (pin "12") (pinfunction "O7_12") (pintype "open_collector"))
      (node (ref "X5") (pin "13") (pinfunction "S_13") (pintype "passive"))
    )
    (net (code "450") (name "Net-(U$17-O8)") (class "Default")
      (node (ref "U$17") (pin "11") (pinfunction "O8_11") (pintype "open_collector"))
      (node (ref "X5") (pin "15") (pinfunction "S_15") (pintype "passive"))
    )
    (net (code "451") (name "Net-(U$18-O1)") (class "Default")
      (node (ref "U$18") (pin "18") (pinfunction "O1_18") (pintype "open_collector"))
      (node (ref "X5") (pin "17") (pinfunction "S_17") (pintype "passive"))
    )
    (net (code "452") (name "Net-(U$18-O2)") (class "Default")
      (node (ref "U$18") (pin "17") (pinfunction "O2_17") (pintype "open_collector"))
      (node (ref "X5") (pin "19") (pinfunction "S_19") (pintype "passive"))
    )
    (net (code "453") (name "Net-(U$18-O3)") (class "Default")
      (node (ref "U$18") (pin "16") (pinfunction "O3_16") (pintype "open_collector"))
      (node (ref "X5") (pin "21") (pinfunction "S_21") (pintype "passive"))
    )
    (net (code "454") (name "Net-(U$18-O4)") (class "Default")
      (node (ref "U$18") (pin "15") (pinfunction "O4_15") (pintype "open_collector"))
      (node (ref "X5") (pin "23") (pinfunction "S_23") (pintype "passive"))
    )
    (net (code "455") (name "Net-(U$18-O5)") (class "Default")
      (node (ref "U$18") (pin "14") (pinfunction "O5_14") (pintype "open_collector"))
      (node (ref "X5") (pin "25") (pinfunction "S_25") (pintype "passive"))
    )
    (net (code "456") (name "Net-(U$18-O6)") (class "Default")
      (node (ref "U$18") (pin "13") (pinfunction "O6_13") (pintype "open_collector"))
      (node (ref "X5") (pin "27") (pinfunction "S_27") (pintype "passive"))
    )
    (net (code "457") (name "Net-(U$18-O7)") (class "Default")
      (node (ref "U$18") (pin "12") (pinfunction "O7_12") (pintype "open_collector"))
      (node (ref "X5") (pin "29") (pinfunction "S_29") (pintype "passive"))
    )
    (net (code "458") (name "Net-(U$18-O8)") (class "Default")
      (node (ref "U$18") (pin "11") (pinfunction "O8_11") (pintype "open_collector"))
      (node (ref "X5") (pin "31") (pinfunction "S_31") (pintype "passive"))
    )
    (net (code "459") (name "Net-(U$19-O1)") (class "Default")
      (node (ref "U$19") (pin "18") (pinfunction "O1_18") (pintype "open_collector"))
      (node (ref "X5") (pin "2") (pinfunction "S_2") (pintype "passive"))
    )
    (net (code "460") (name "Net-(U$19-O2)") (class "Default")
      (node (ref "U$19") (pin "17") (pinfunction "O2_17") (pintype "open_collector"))
      (node (ref "X5") (pin "4") (pinfunction "S_4") (pintype "passive"))
    )
    (net (code "461") (name "Net-(U$19-O3)") (class "Default")
      (node (ref "U$19") (pin "16") (pinfunction "O3_16") (pintype "open_collector"))
      (node (ref "X5") (pin "6") (pinfunction "S_6") (pintype "passive"))
    )
    (net (code "462") (name "Net-(U$19-O4)") (class "Default")
      (node (ref "U$19") (pin "15") (pinfunction "O4_15") (pintype "open_collector"))
      (node (ref "X5") (pin "8") (pinfunction "S_8") (pintype "passive"))
    )
    (net (code "463") (name "Net-(U$19-O5)") (class "Default")
      (node (ref "U$19") (pin "14") (pinfunction "O5_14") (pintype "open_collector"))
      (node (ref "X5") (pin "10") (pinfunction "S_10") (pintype "passive"))
    )
    (net (code "464") (name "Net-(U$19-O6)") (class "Default")
      (node (ref "U$19") (pin "13") (pinfunction "O6_13") (pintype "open_collector"))
      (node (ref "X5") (pin "12") (pinfunction "S_12") (pintype "passive"))
    )
    (net (code "465") (name "Net-(U$19-O7)") (class "Default")
      (node (ref "U$19") (pin "12") (pinfunction "O7_12") (pintype "open_collector"))
      (node (ref "X5") (pin "14") (pinfunction "S_14") (pintype "passive"))
    )
    (net (code "466") (name "Net-(U$19-O8)") (class "Default")
      (node (ref "U$19") (pin "11") (pinfunction "O8_11") (pintype "open_collector"))
      (node (ref "X5") (pin "16") (pinfunction "S_16") (pintype "passive"))
    )
    (net (code "467") (name "Net-(U$20-O1)") (class "Default")
      (node (ref "U$20") (pin "18") (pinfunction "O1_18") (pintype "open_collector"))
      (node (ref "X5") (pin "18") (pinfunction "S_18") (pintype "passive"))
    )
    (net (code "468") (name "Net-(U$20-O2)") (class "Default")
      (node (ref "U$20") (pin "17") (pinfunction "O2_17") (pintype "open_collector"))
      (node (ref "X5") (pin "20") (pinfunction "S_20") (pintype "passive"))
    )
    (net (code "469") (name "Net-(U$20-O3)") (class "Default")
      (node (ref "U$20") (pin "16") (pinfunction "O3_16") (pintype "open_collector"))
      (node (ref "X5") (pin "22") (pinfunction "S_22") (pintype "passive"))
    )
    (net (code "470") (name "Net-(U$20-O4)") (class "Default")
      (node (ref "U$20") (pin "15") (pinfunction "O4_15") (pintype "open_collector"))
      (node (ref "X5") (pin "24") (pinfunction "S_24") (pintype "passive"))
    )
    (net (code "471") (name "Net-(U$20-O5)") (class "Default")
      (node (ref "U$20") (pin "14") (pinfunction "O5_14") (pintype "open_collector"))
      (node (ref "X5") (pin "26") (pinfunction "S_26") (pintype "passive"))
    )
    (net (code "472") (name "Net-(U$20-O6)") (class "Default")
      (node (ref "U$20") (pin "13") (pinfunction "O6_13") (pintype "open_collector"))
      (node (ref "X5") (pin "28") (pinfunction "S_28") (pintype "passive"))
    )
    (net (code "473") (name "Net-(U$20-O7)") (class "Default")
      (node (ref "U$20") (pin "12") (pinfunction "O7_12") (pintype "open_collector"))
      (node (ref "X5") (pin "30") (pinfunction "S_30") (pintype "passive"))
    )
    (net (code "474") (name "Net-(U$20-O8)") (class "Default")
      (node (ref "U$20") (pin "11") (pinfunction "O8_11") (pintype "open_collector"))
      (node (ref "X5") (pin "32") (pinfunction "S_32") (pintype "passive"))
    )
    (net (code "475") (name "Net-(U$21-O1)") (class "Default")
      (node (ref "U$21") (pin "18") (pinfunction "O1_18") (pintype "open_collector"))
      (node (ref "X6") (pin "1") (pinfunction "S_1") (pintype "passive"))
    )
    (net (code "476") (name "Net-(U$21-O2)") (class "Default")
      (node (ref "U$21") (pin "17") (pinfunction "O2_17") (pintype "open_collector"))
      (node (ref "X6") (pin "3") (pinfunction "S_3") (pintype "passive"))
    )
    (net (code "477") (name "Net-(U$21-O3)") (class "Default")
      (node (ref "U$21") (pin "16") (pinfunction "O3_16") (pintype "open_collector"))
      (node (ref "X6") (pin "5") (pinfunction "S_5") (pintype "passive"))
    )
    (net (code "478") (name "Net-(U$21-O4)") (class "Default")
      (node (ref "U$21") (pin "15") (pinfunction "O4_15") (pintype "open_collector"))
      (node (ref "X6") (pin "7") (pinfunction "S_7") (pintype "passive"))
    )
    (net (code "479") (name "Net-(U$21-O5)") (class "Default")
      (node (ref "U$21") (pin "14") (pinfunction "O5_14") (pintype "open_collector"))
      (node (ref "X6") (pin "9") (pinfunction "S_9") (pintype "passive"))
    )
    (net (code "480") (name "Net-(U$21-O6)") (class "Default")
      (node (ref "U$21") (pin "13") (pinfunction "O6_13") (pintype "open_collector"))
      (node (ref "X6") (pin "11") (pinfunction "S_11") (pintype "passive"))
    )
    (net (code "481") (name "Net-(U$21-O7)") (class "Default")
      (node (ref "U$21") (pin "12") (pinfunction "O7_12") (pintype "open_collector"))
      (node (ref "X6") (pin "13") (pinfunction "S_13") (pintype "passive"))
    )
    (net (code "482") (name "Net-(U$21-O8)") (class "Default")
      (node (ref "U$21") (pin "11") (pinfunction "O8_11") (pintype "open_collector"))
      (node (ref "X6") (pin "15") (pinfunction "S_15") (pintype "passive"))
    )
    (net (code "483") (name "Net-(U$22-O1)") (class "Default")
      (node (ref "U$22") (pin "18") (pinfunction "O1_18") (pintype "open_collector"))
      (node (ref "X6") (pin "17") (pinfunction "S_17") (pintype "passive"))
    )
    (net (code "484") (name "Net-(U$22-O2)") (class "Default")
      (node (ref "U$22") (pin "17") (pinfunction "O2_17") (pintype "open_collector"))
      (node (ref "X6") (pin "19") (pinfunction "S_19") (pintype "passive"))
    )
    (net (code "485") (name "Net-(U$22-O3)") (class "Default")
      (node (ref "U$22") (pin "16") (pinfunction "O3_16") (pintype "open_collector"))
      (node (ref "X6") (pin "21") (pinfunction "S_21") (pintype "passive"))
    )
    (net (code "486") (name "Net-(U$22-O4)") (class "Default")
      (node (ref "U$22") (pin "15") (pinfunction "O4_15") (pintype "open_collector"))
      (node (ref "X6") (pin "23") (pinfunction "S_23") (pintype "passive"))
    )
    (net (code "487") (name "Net-(U$22-O5)") (class "Default")
      (node (ref "U$22") (pin "14") (pinfunction "O5_14") (pintype "open_collector"))
      (node (ref "X6") (pin "25") (pinfunction "S_25") (pintype "passive"))
    )
    (net (code "488") (name "Net-(U$22-O6)") (class "Default")
      (node (ref "U$22") (pin "13") (pinfunction "O6_13") (pintype "open_collector"))
      (node (ref "X6") (pin "27") (pinfunction "S_27") (pintype "passive"))
    )
    (net (code "489") (name "Net-(U$22-O7)") (class "Default")
      (node (ref "U$22") (pin "12") (pinfunction "O7_12") (pintype "open_collector"))
      (node (ref "X6") (pin "29") (pinfunction "S_29") (pintype "passive"))
    )
    (net (code "490") (name "Net-(U$22-O8)") (class "Default")
      (node (ref "U$22") (pin "11") (pinfunction "O8_11") (pintype "open_collector"))
      (node (ref "X6") (pin "31") (pinfunction "S_31") (pintype "passive"))
    )
    (net (code "491") (name "Net-(U$23-O1)") (class "Default")
      (node (ref "U$23") (pin "18") (pinfunction "O1_18") (pintype "open_collector"))
      (node (ref "X6") (pin "2") (pinfunction "S_2") (pintype "passive"))
    )
    (net (code "492") (name "Net-(U$23-O2)") (class "Default")
      (node (ref "U$23") (pin "17") (pinfunction "O2_17") (pintype "open_collector"))
      (node (ref "X6") (pin "4") (pinfunction "S_4") (pintype "passive"))
    )
    (net (code "493") (name "Net-(U$23-O3)") (class "Default")
      (node (ref "U$23") (pin "16") (pinfunction "O3_16") (pintype "open_collector"))
      (node (ref "X6") (pin "6") (pinfunction "S_6") (pintype "passive"))
    )
    (net (code "494") (name "Net-(U$23-O4)") (class "Default")
      (node (ref "U$23") (pin "15") (pinfunction "O4_15") (pintype "open_collector"))
      (node (ref "X6") (pin "8") (pinfunction "S_8") (pintype "passive"))
    )
    (net (code "495") (name "Net-(U$23-O5)") (class "Default")
      (node (ref "U$23") (pin "14") (pinfunction "O5_14") (pintype "open_collector"))
      (node (ref "X6") (pin "10") (pinfunction "S_10") (pintype "passive"))
    )
    (net (code "496") (name "Net-(U$23-O6)") (class "Default")
      (node (ref "U$23") (pin "13") (pinfunction "O6_13") (pintype "open_collector"))
      (node (ref "X6") (pin "12") (pinfunction "S_12") (pintype "passive"))
    )
    (net (code "497") (name "Net-(U$23-O7)") (class "Default")
      (node (ref "U$23") (pin "12") (pinfunction "O7_12") (pintype "open_collector"))
      (node (ref "X6") (pin "14") (pinfunction "S_14") (pintype "passive"))
    )
    (net (code "498") (name "Net-(U$23-O8)") (class "Default")
      (node (ref "U$23") (pin "11") (pinfunction "O8_11") (pintype "open_collector"))
      (node (ref "X6") (pin "16") (pinfunction "S_16") (pintype "passive"))
    )
    (net (code "499") (name "Net-(U$24-O1)") (class "Default")
      (node (ref "U$24") (pin "18") (pinfunction "O1_18") (pintype "open_collector"))
      (node (ref "X6") (pin "18") (pinfunction "S_18") (pintype "passive"))
    )
    (net (code "500") (name "Net-(U$24-O2)") (class "Default")
      (node (ref "U$24") (pin "17") (pinfunction "O2_17") (pintype "open_collector"))
      (node (ref "X6") (pin "20") (pinfunction "S_20") (pintype "passive"))
    )
    (net (code "501") (name "Net-(U$24-O3)") (class "Default")
      (node (ref "U$24") (pin "16") (pinfunction "O3_16") (pintype "open_collector"))
      (node (ref "X6") (pin "22") (pinfunction "S_22") (pintype "passive"))
    )
    (net (code "502") (name "Net-(U$24-O4)") (class "Default")
      (node (ref "U$24") (pin "15") (pinfunction "O4_15") (pintype "open_collector"))
      (node (ref "X6") (pin "24") (pinfunction "S_24") (pintype "passive"))
    )
    (net (code "503") (name "Net-(U$24-O5)") (class "Default")
      (node (ref "U$24") (pin "14") (pinfunction "O5_14") (pintype "open_collector"))
      (node (ref "X6") (pin "26") (pinfunction "S_26") (pintype "passive"))
    )
    (net (code "504") (name "Net-(U$24-O6)") (class "Default")
      (node (ref "U$24") (pin "13") (pinfunction "O6_13") (pintype "open_collector"))
      (node (ref "X6") (pin "28") (pinfunction "S_28") (pintype "passive"))
    )
    (net (code "505") (name "Net-(U$24-O7)") (class "Default")
      (node (ref "U$24") (pin "12") (pinfunction "O7_12") (pintype "open_collector"))
      (node (ref "X6") (pin "30") (pinfunction "S_30") (pintype "passive"))
    )
    (net (code "506") (name "Net-(U$24-O8)") (class "Default")
      (node (ref "U$24") (pin "11") (pinfunction "O8_11") (pintype "open_collector"))
      (node (ref "X6") (pin "32") (pinfunction "S_32") (pintype "passive"))
    )
    (net (code "507") (name "VCC") (class "Default")
      (node (ref "X11") (pin "8") (pinfunction "S_8") (pintype "passive"))
    )
    (net (code "508") (name "unconnected-(IC102A-1D6-Pad40)") (class "Default")
      (node (ref "IC102") (pin "40") (pinfunction "1D6_40") (pintype "input"))
    )
    (net (code "509") (name "unconnected-(IC102A-1D7-Pad38)") (class "Default")
      (node (ref "IC102") (pin "38") (pinfunction "1D7_38") (pintype "input"))
    )
    (net (code "510") (name "unconnected-(IC102A-1D8-Pad37)") (class "Default")
      (node (ref "IC102") (pin "37") (pinfunction "1D8_37") (pintype "input"))
    )
    (net (code "511") (name "unconnected-(IC102A-1Q5-Pad8)") (class "Default")
      (node (ref "IC102") (pin "8") (pinfunction "1Q5_8") (pintype "tri_state"))
    )
    (net (code "512") (name "unconnected-(IC102A-1Q6-Pad9)") (class "Default")
      (node (ref "IC102") (pin "9") (pinfunction "1Q6_9") (pintype "tri_state"))
    )
    (net (code "513") (name "unconnected-(IC102A-1Q7-Pad11)") (class "Default")
      (node (ref "IC102") (pin "11") (pinfunction "1Q7_11") (pintype "tri_state"))
    )
    (net (code "514") (name "unconnected-(IC102A-1Q8-Pad12)") (class "Default")
      (node (ref "IC102") (pin "12") (pinfunction "1Q8_12") (pintype "tri_state"))
    )
    (net (code "515") (name "unconnected-(IC102A-2D1-Pad36)") (class "Default")
      (node (ref "IC102") (pin "36") (pinfunction "2D1_36") (pintype "input"))
    )
    (net (code "516") (name "unconnected-(IC102A-2D2-Pad35)") (class "Default")
      (node (ref "IC102") (pin "35") (pinfunction "2D2_35") (pintype "input"))
    )
    (net (code "517") (name "unconnected-(IC102A-2D3-Pad33)") (class "Default")
      (node (ref "IC102") (pin "33") (pinfunction "2D3_33") (pintype "input"))
    )
    (net (code "518") (name "unconnected-(IC102A-2D4-Pad32)") (class "Default")
      (node (ref "IC102") (pin "32") (pinfunction "2D4_32") (pintype "input"))
    )
    (net (code "519") (name "unconnected-(IC102A-2D5-Pad30)") (class "Default")
      (node (ref "IC102") (pin "30") (pinfunction "2D5_30") (pintype "input"))
    )
    (net (code "520") (name "unconnected-(IC102A-2D6-Pad29)") (class "Default")
      (node (ref "IC102") (pin "29") (pinfunction "2D6_29") (pintype "input"))
    )
    (net (code "521") (name "unconnected-(IC102A-2D7-Pad27)") (class "Default")
      (node (ref "IC102") (pin "27") (pinfunction "2D7_27") (pintype "input"))
    )
    (net (code "522") (name "unconnected-(IC102A-2D8-Pad26)") (class "Default")
      (node (ref "IC102") (pin "26") (pinfunction "2D8_26") (pintype "input"))
    )
    (net (code "523") (name "unconnected-(IC102A-2Q1-Pad13)") (class "Default")
      (node (ref "IC102") (pin "13") (pinfunction "2Q1_13") (pintype "tri_state"))
    )
    (net (code "524") (name "unconnected-(IC102A-2Q2-Pad14)") (class "Default")
      (node (ref "IC102") (pin "14") (pinfunction "2Q2_14") (pintype "tri_state"))
    )
    (net (code "525") (name "unconnected-(IC102A-2Q3-Pad16)") (class "Default")
      (node (ref "IC102") (pin "16") (pinfunction "2Q3_16") (pintype "tri_state"))
    )
    (net (code "526") (name "unconnected-(IC102A-2Q4-Pad17)") (class "Default")
      (node (ref "IC102") (pin "17") (pinfunction "2Q4_17") (pintype "tri_state"))
    )
    (net (code "527") (name "unconnected-(IC102A-2Q5-Pad19)") (class "Default")
      (node (ref "IC102") (pin "19") (pinfunction "2Q5_19") (pintype "tri_state"))
    )
    (net (code "528") (name "unconnected-(IC102A-2Q6-Pad20)") (class "Default")
      (node (ref "IC102") (pin "20") (pinfunction "2Q6_20") (pintype "tri_state"))
    )
    (net (code "529") (name "unconnected-(IC102A-2Q7-Pad22)") (class "Default")
      (node (ref "IC102") (pin "22") (pinfunction "2Q7_22") (pintype "tri_state"))
    )
    (net (code "530") (name "unconnected-(IC102A-2Q8-Pad23)") (class "Default")
      (node (ref "IC102") (pin "23") (pinfunction "2Q8_23") (pintype "tri_state"))
    )
    (net (code "531") (name "unconnected-(X11B-S-Pad10)") (class "Default")
      (node (ref "X11") (pin "10") (pinfunction "S_10") (pintype "passive"))
    )
    (net (code "532") (name "unconnected-(X11C-S-Pad11)") (class "Default")
      (node (ref "X11") (pin "11") (pinfunction "S_11") (pintype "passive"))
    )
    (net (code "533") (name "unconnected-(X11D-S-Pad12)") (class "Default")
      (node (ref "X11") (pin "12") (pinfunction "S_12") (pintype "passive"))
    )
    (net (code "534") (name "unconnected-(X11E-S-Pad13)") (class "Default")
      (node (ref "X11") (pin "13") (pinfunction "S_13") (pintype "passive"))
    )
    (net (code "535") (name "unconnected-(X11F-S-Pad14)") (class "Default")
      (node (ref "X11") (pin "14") (pinfunction "S_14") (pintype "passive"))
    )
  )
)
